# PowCapMobile.net
KiCad netlist of a schematic drawn in Altium Designer
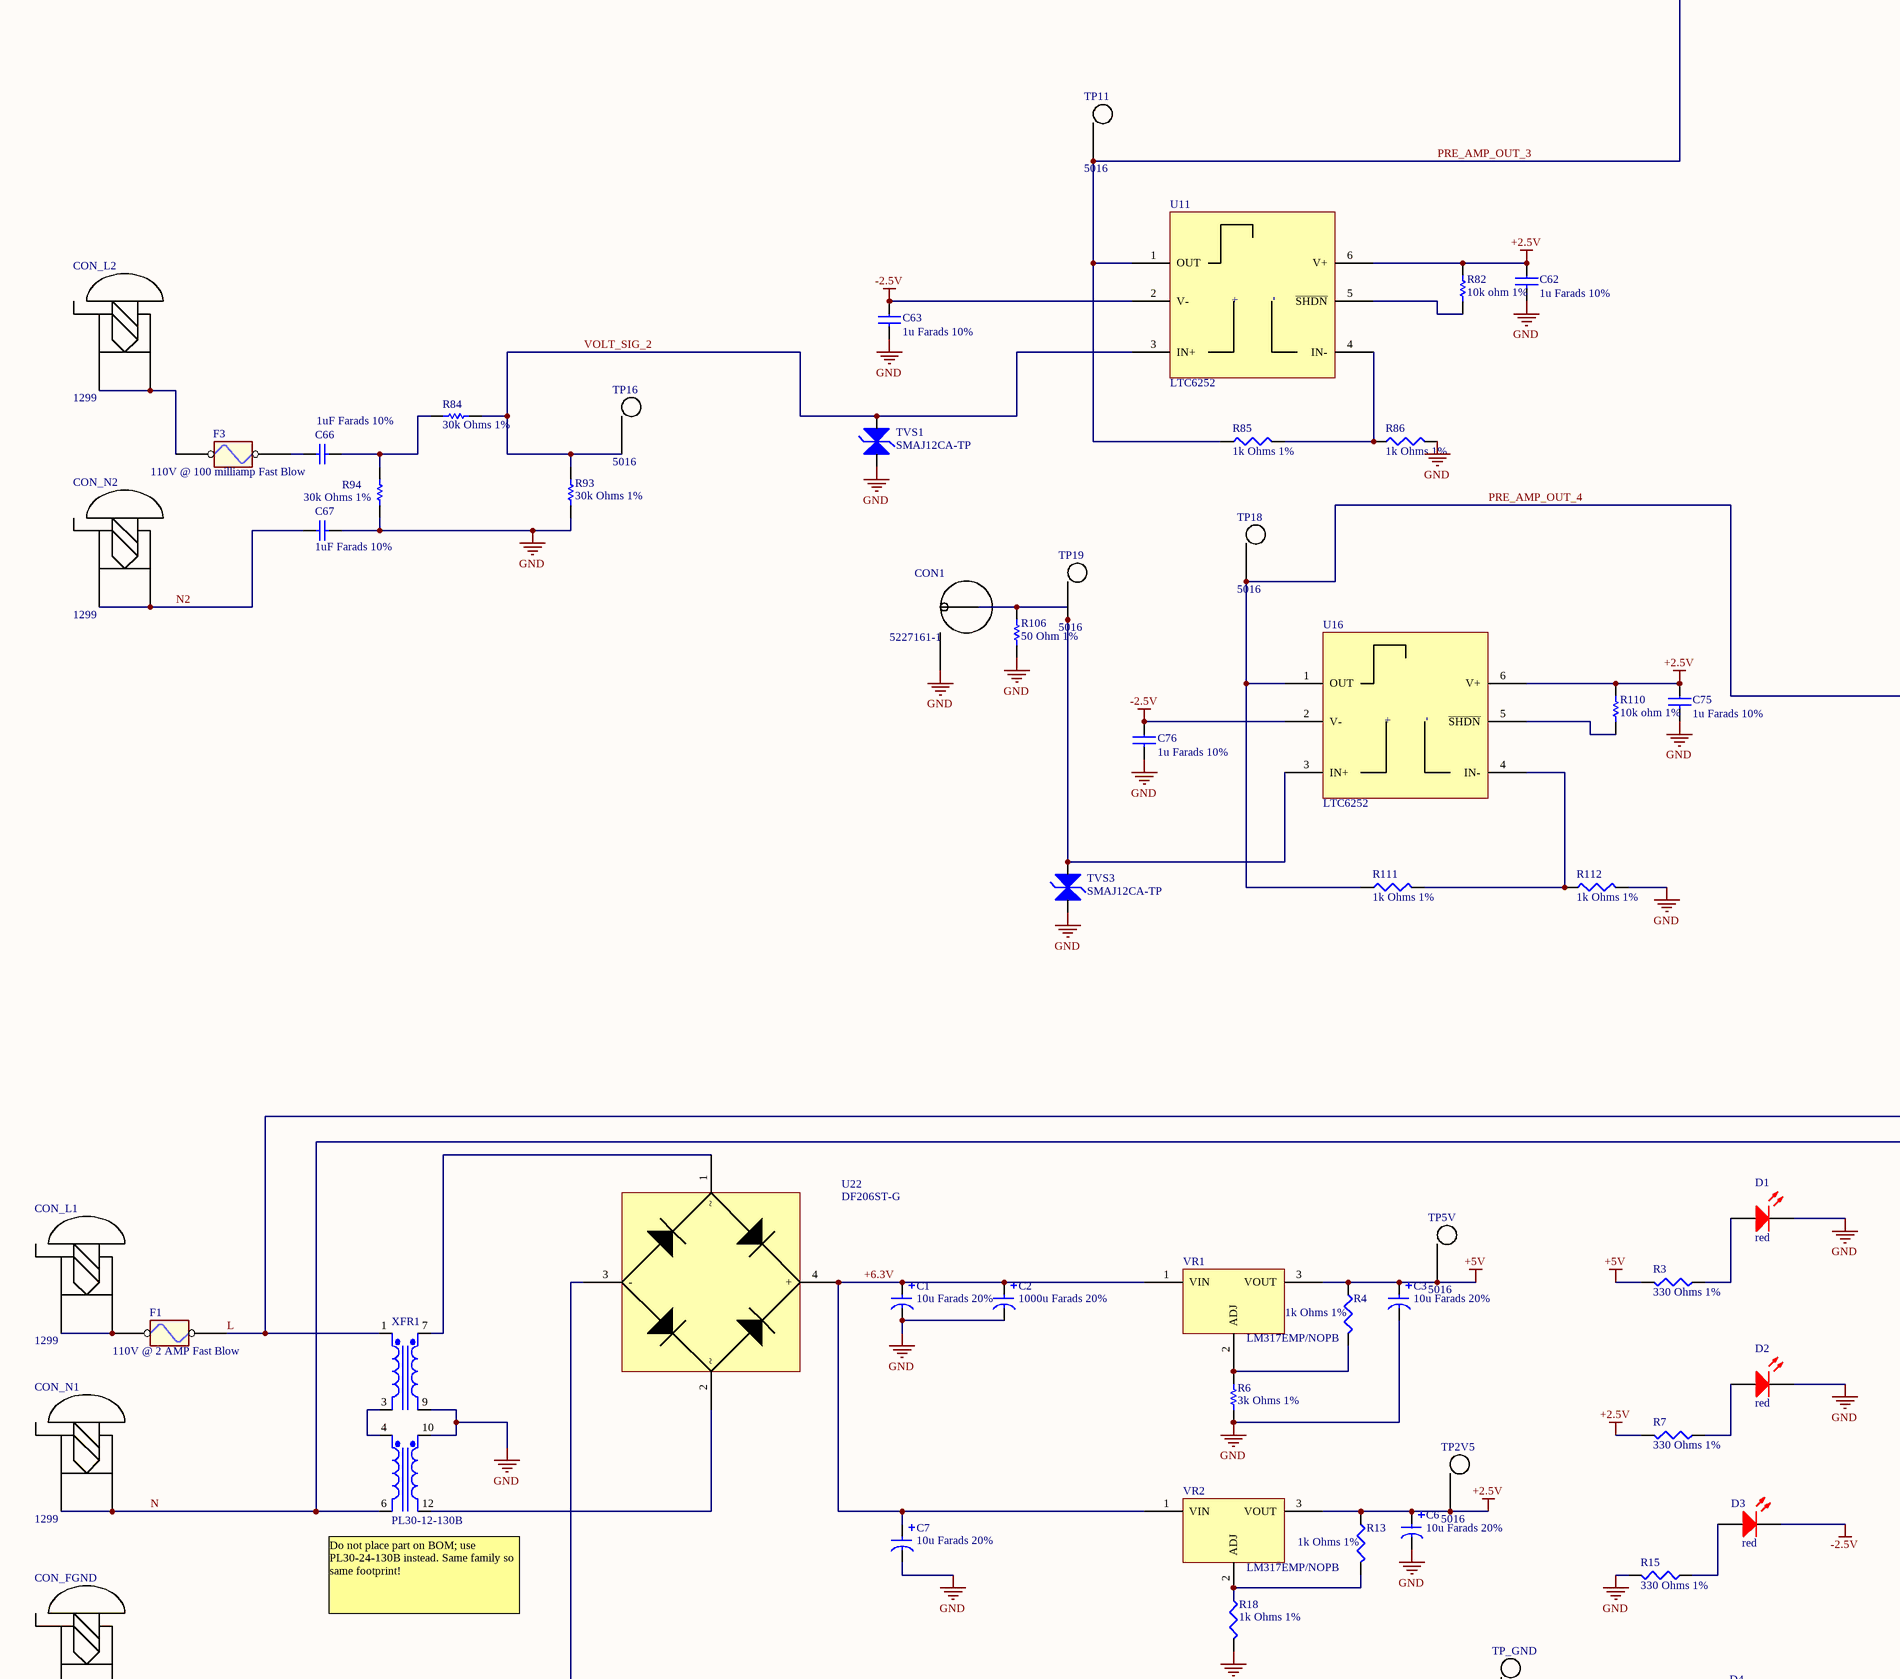
[diagram p0: PowCapMobile.SchDoc, top left]
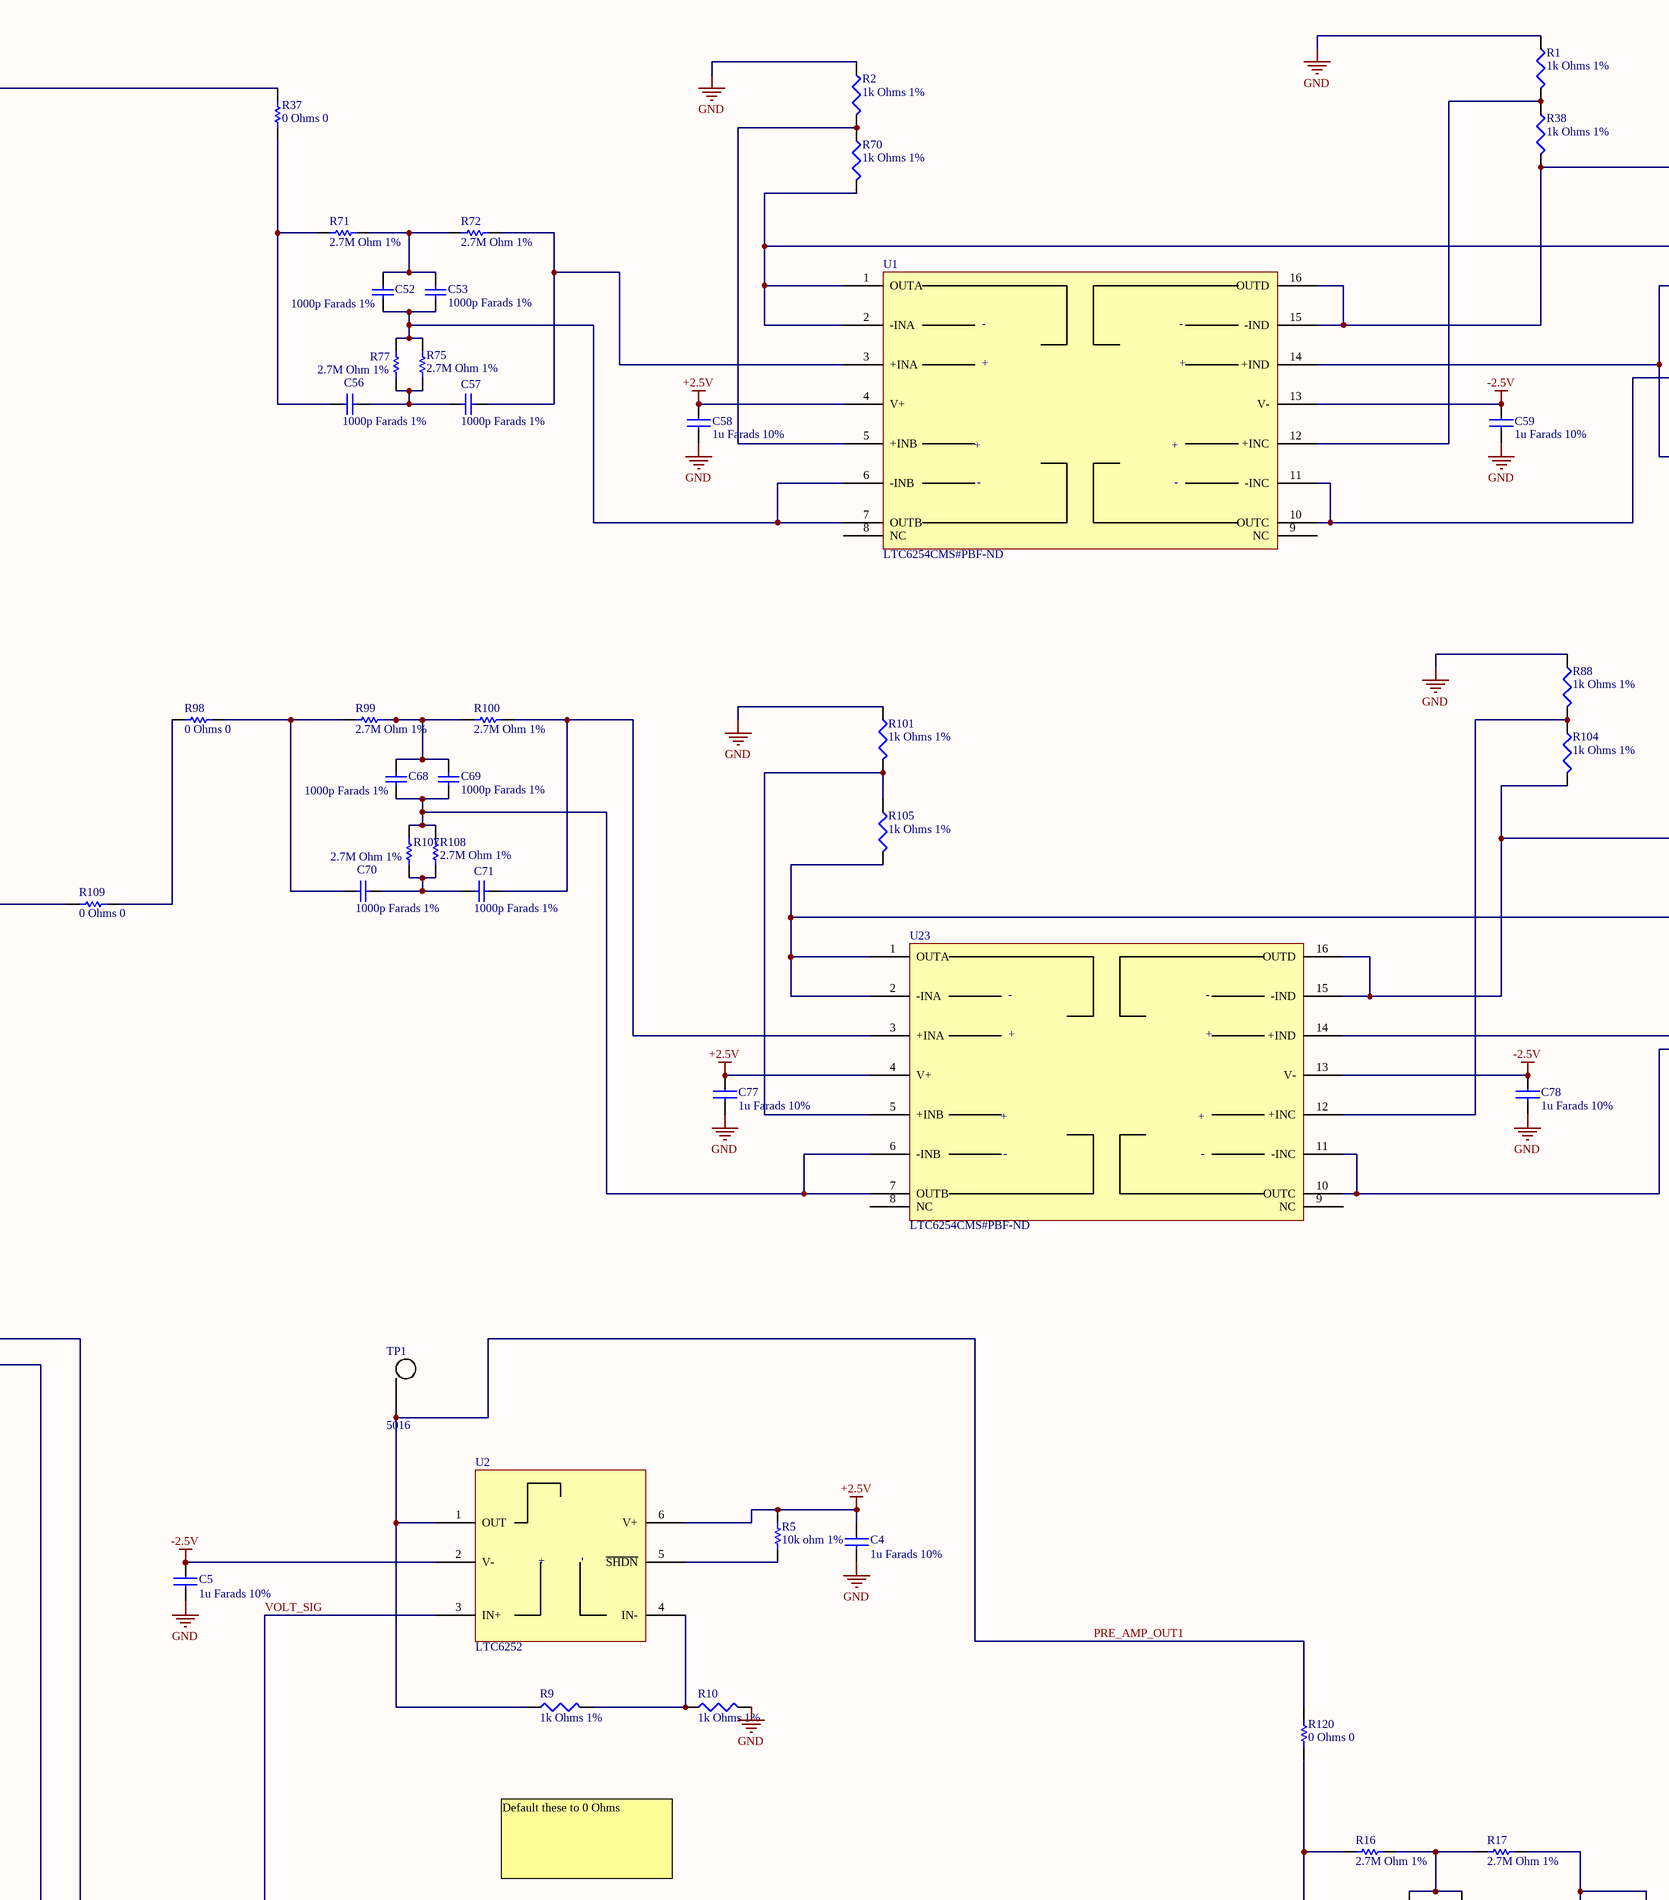
[diagram p1: PowCapMobile.SchDoc, top middle]
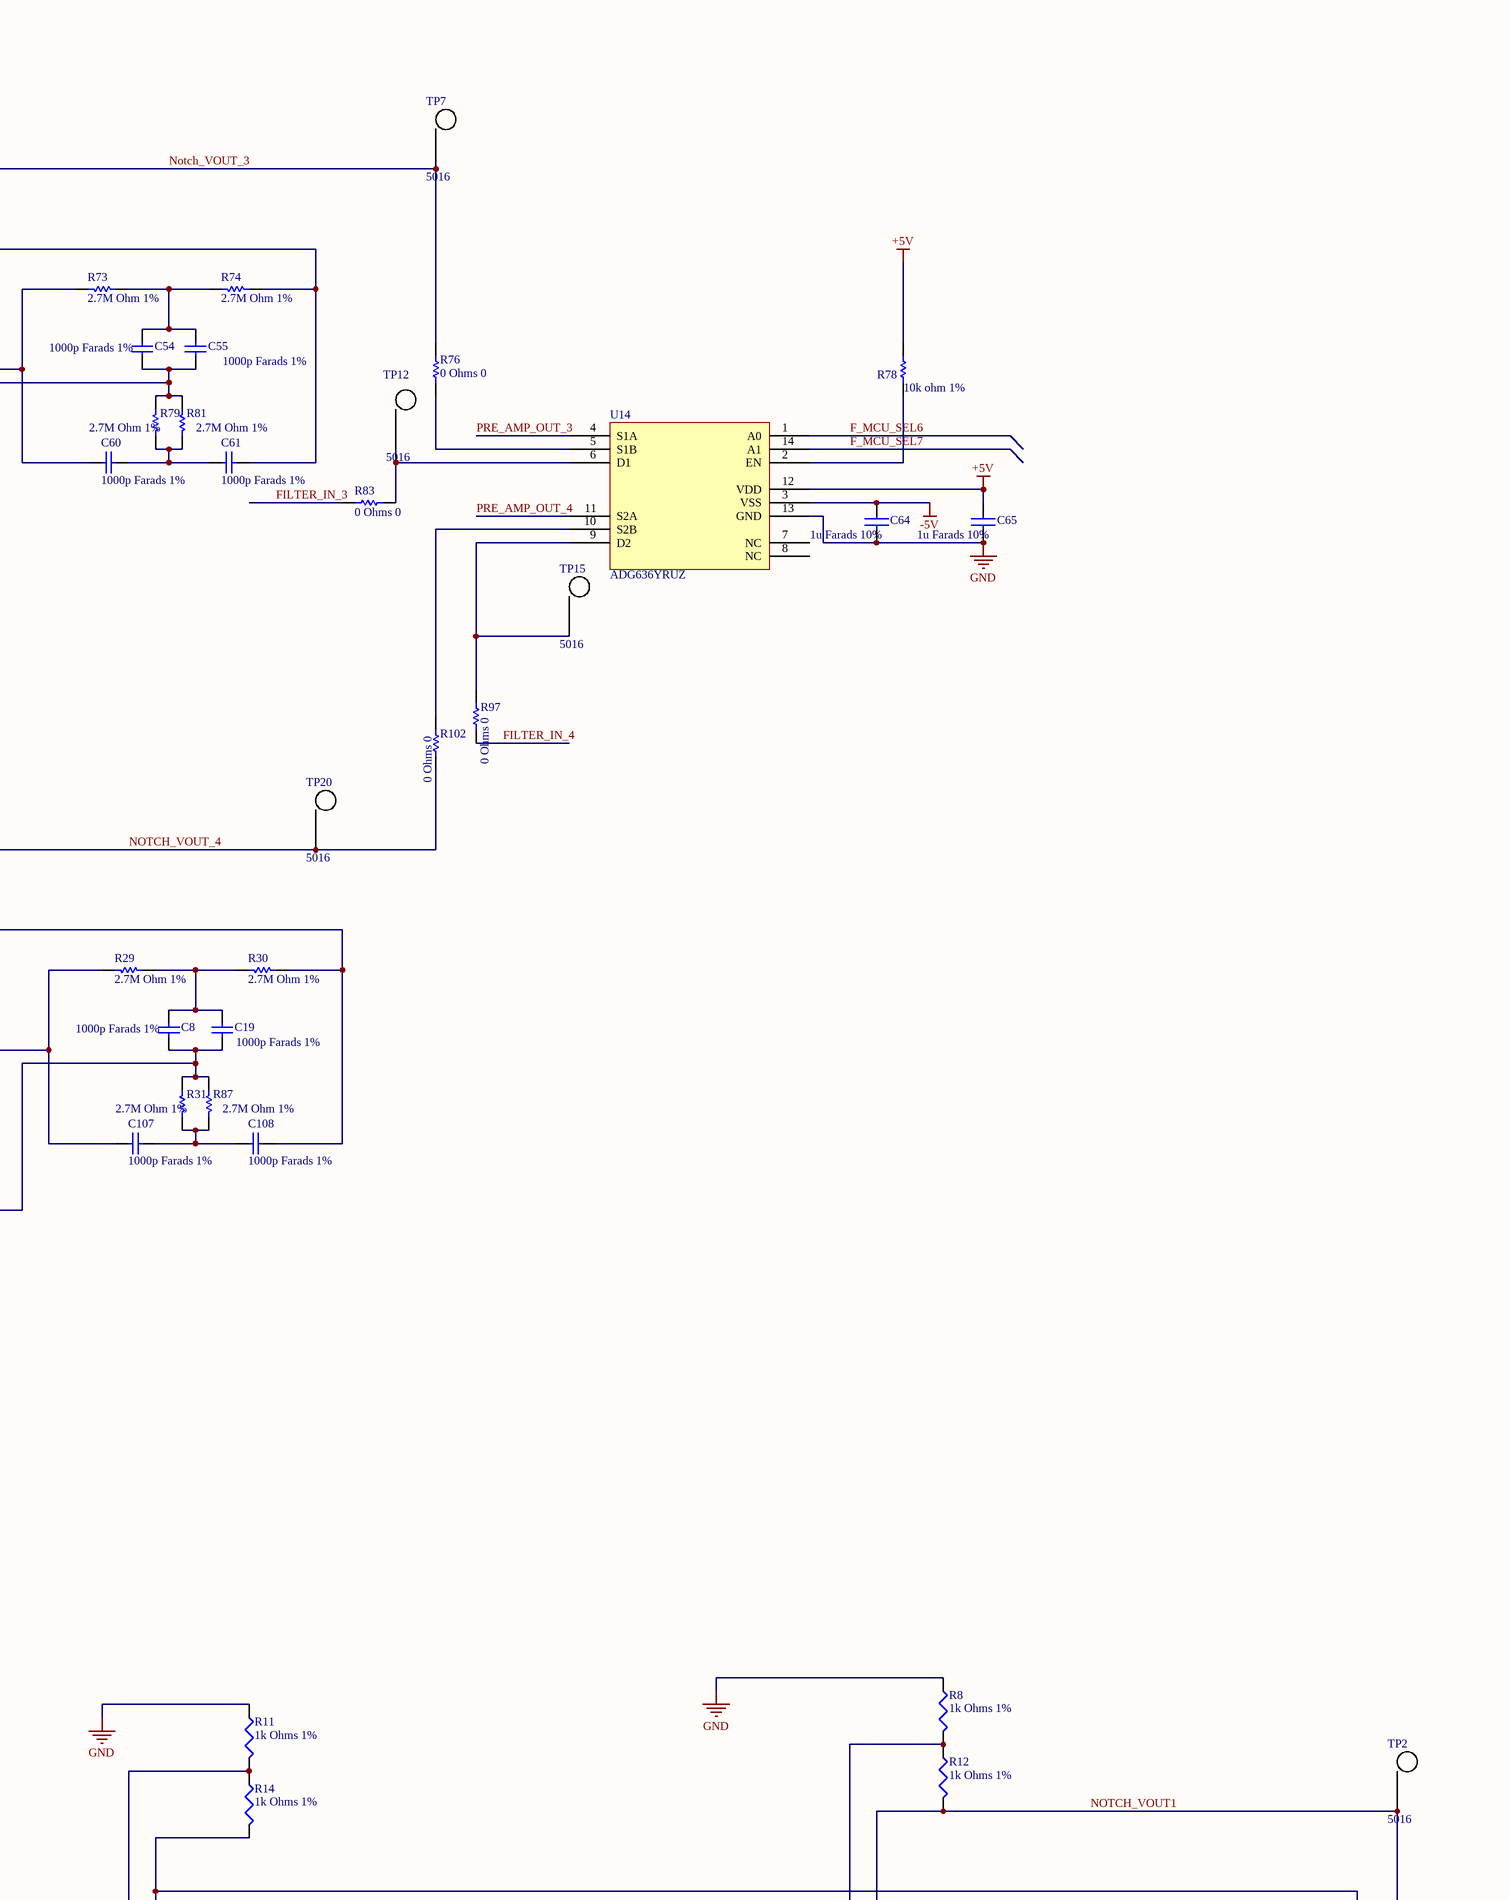
[diagram p2: PowCapMobile.SchDoc, top right]
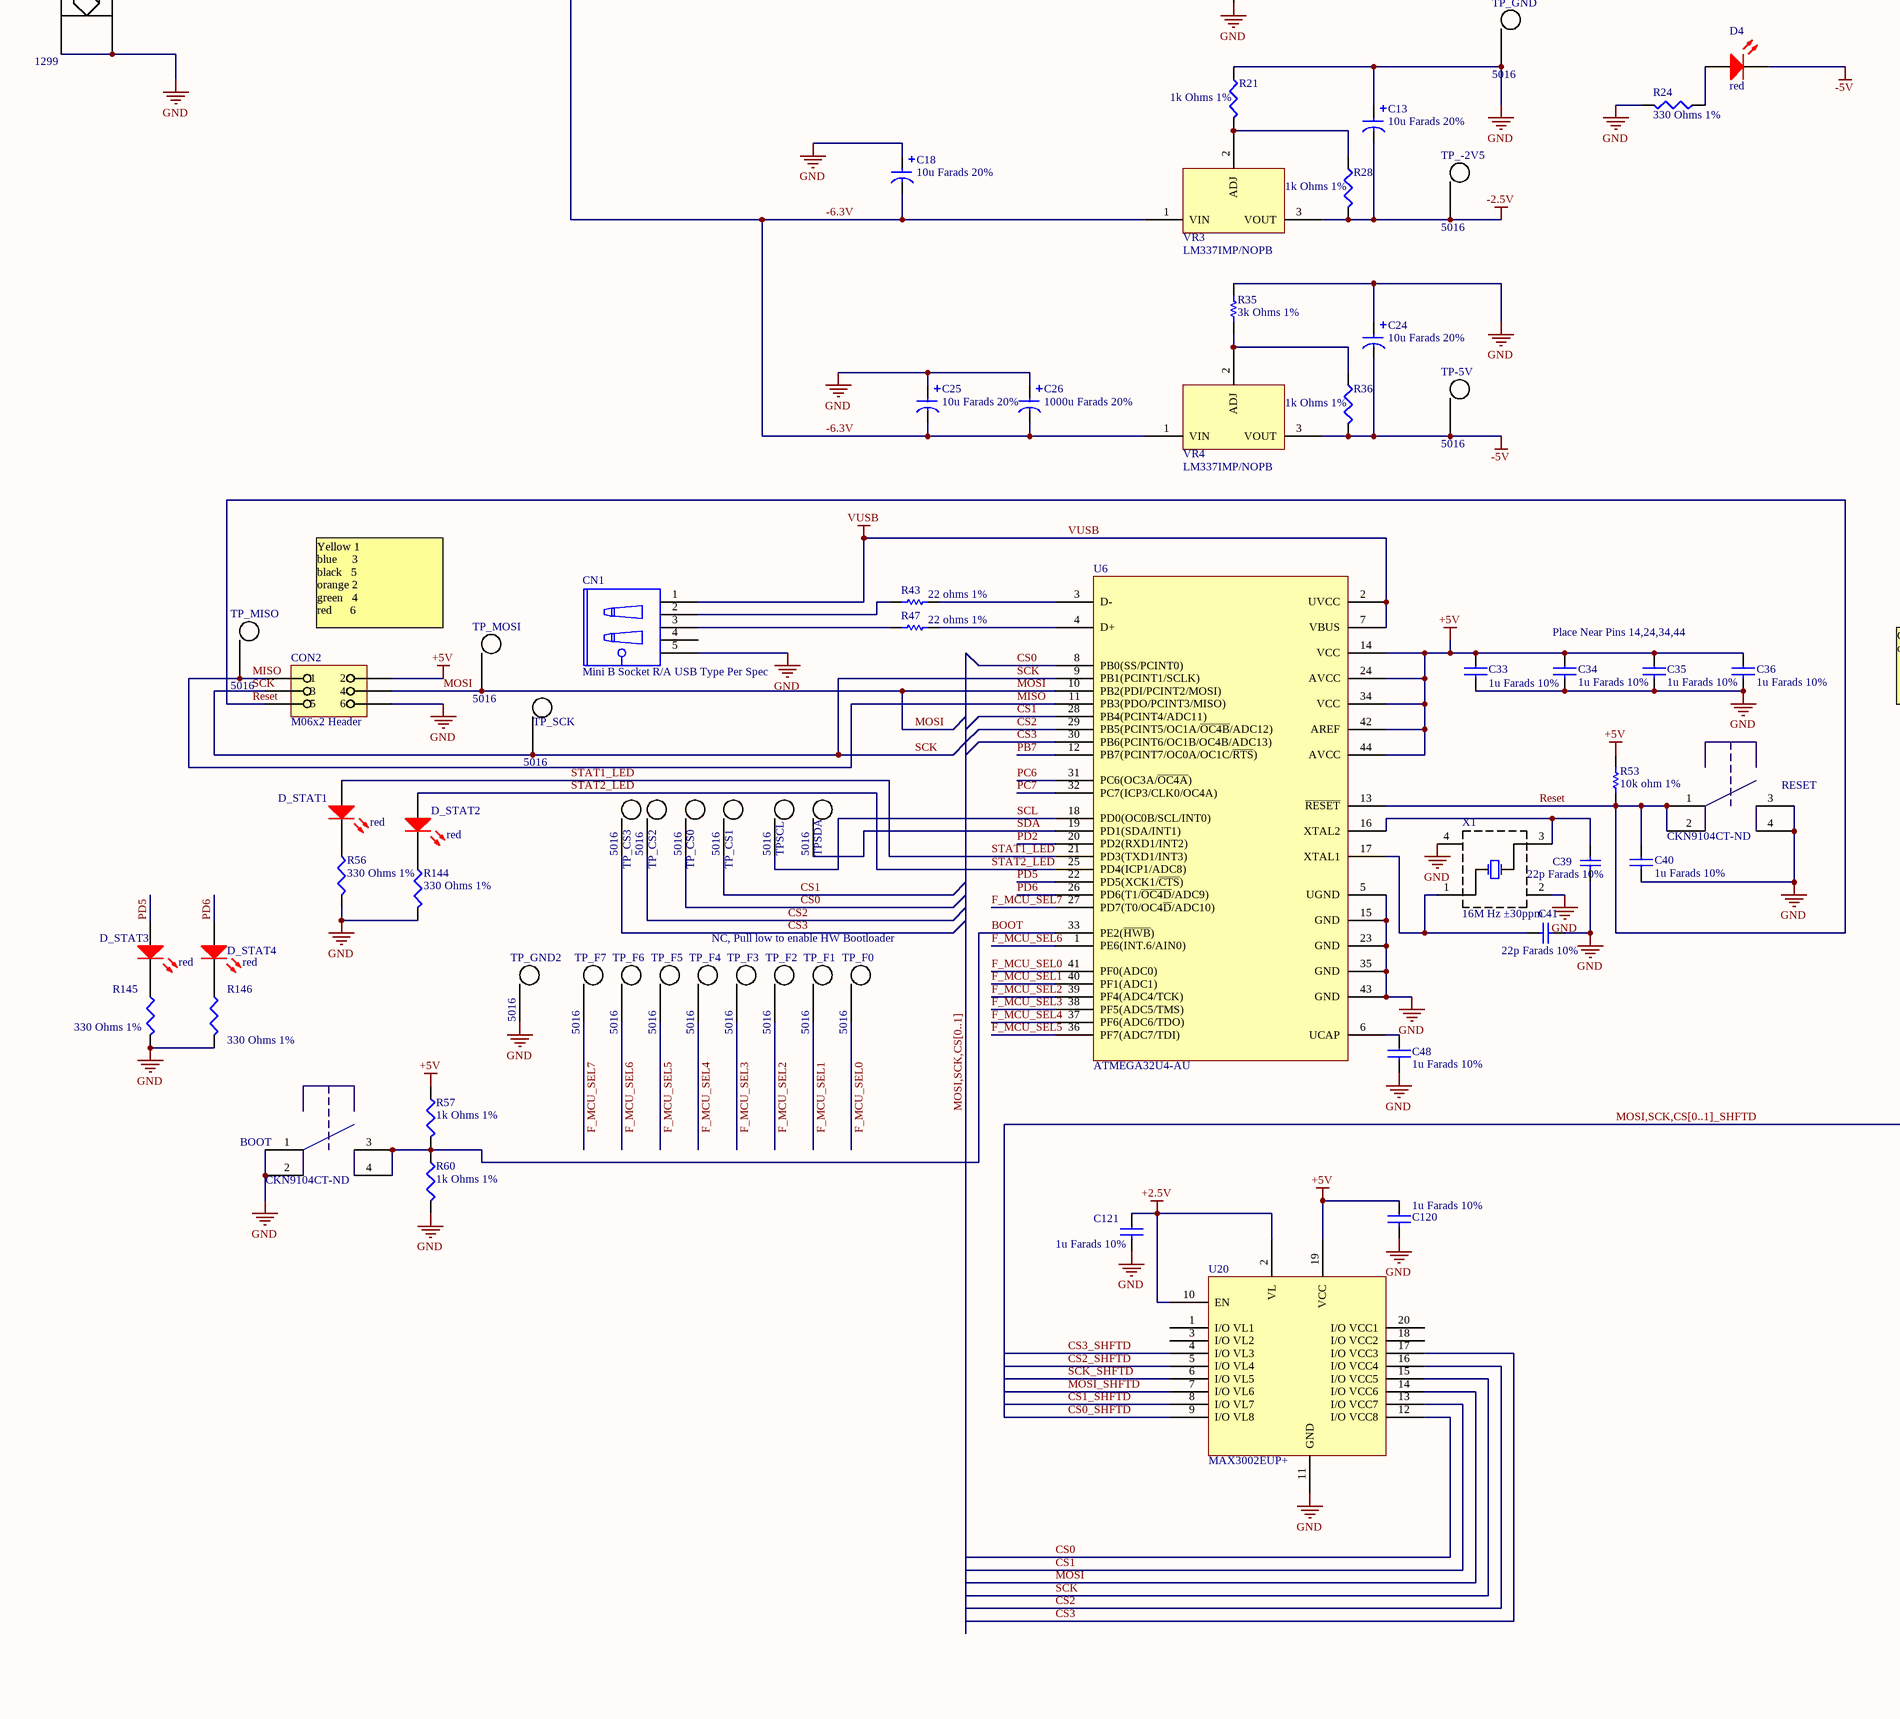
[diagram p3: PowCapMobile.SchDoc, centre left]
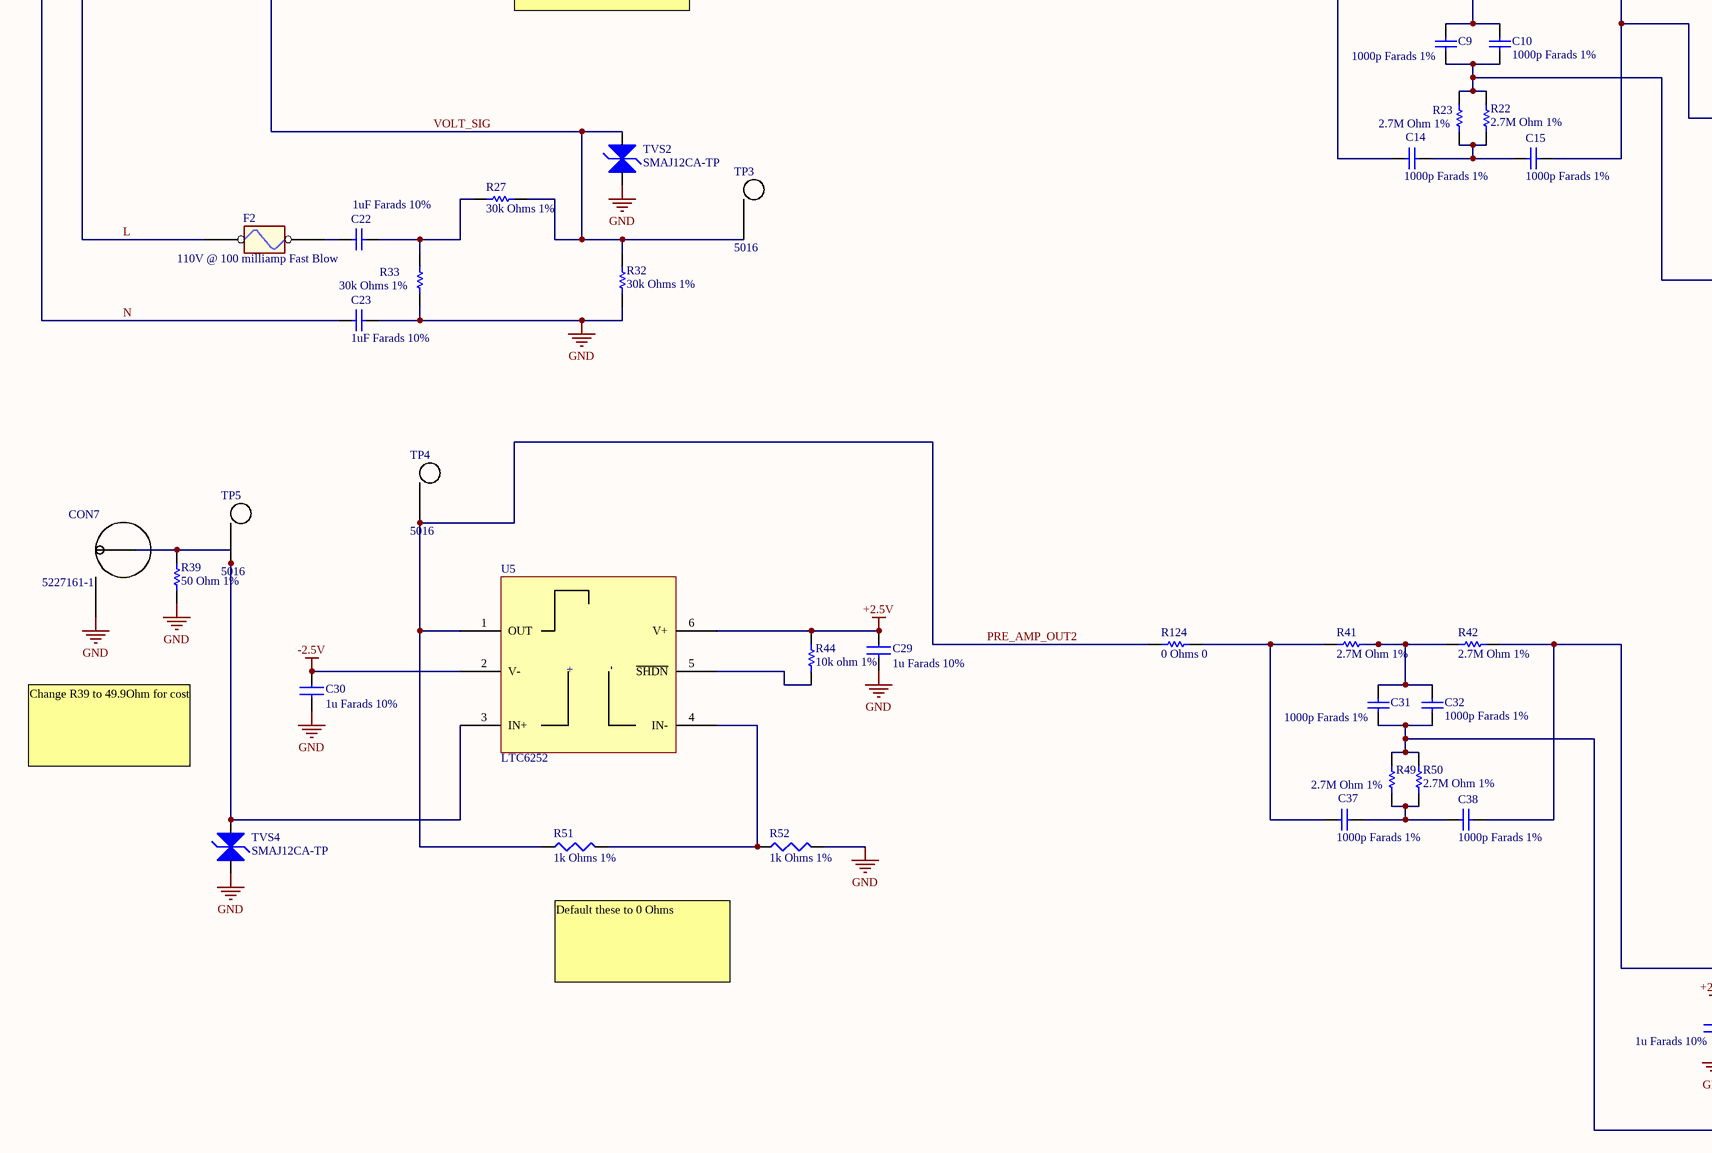
[diagram p4: PowCapMobile.SchDoc, centre middle]
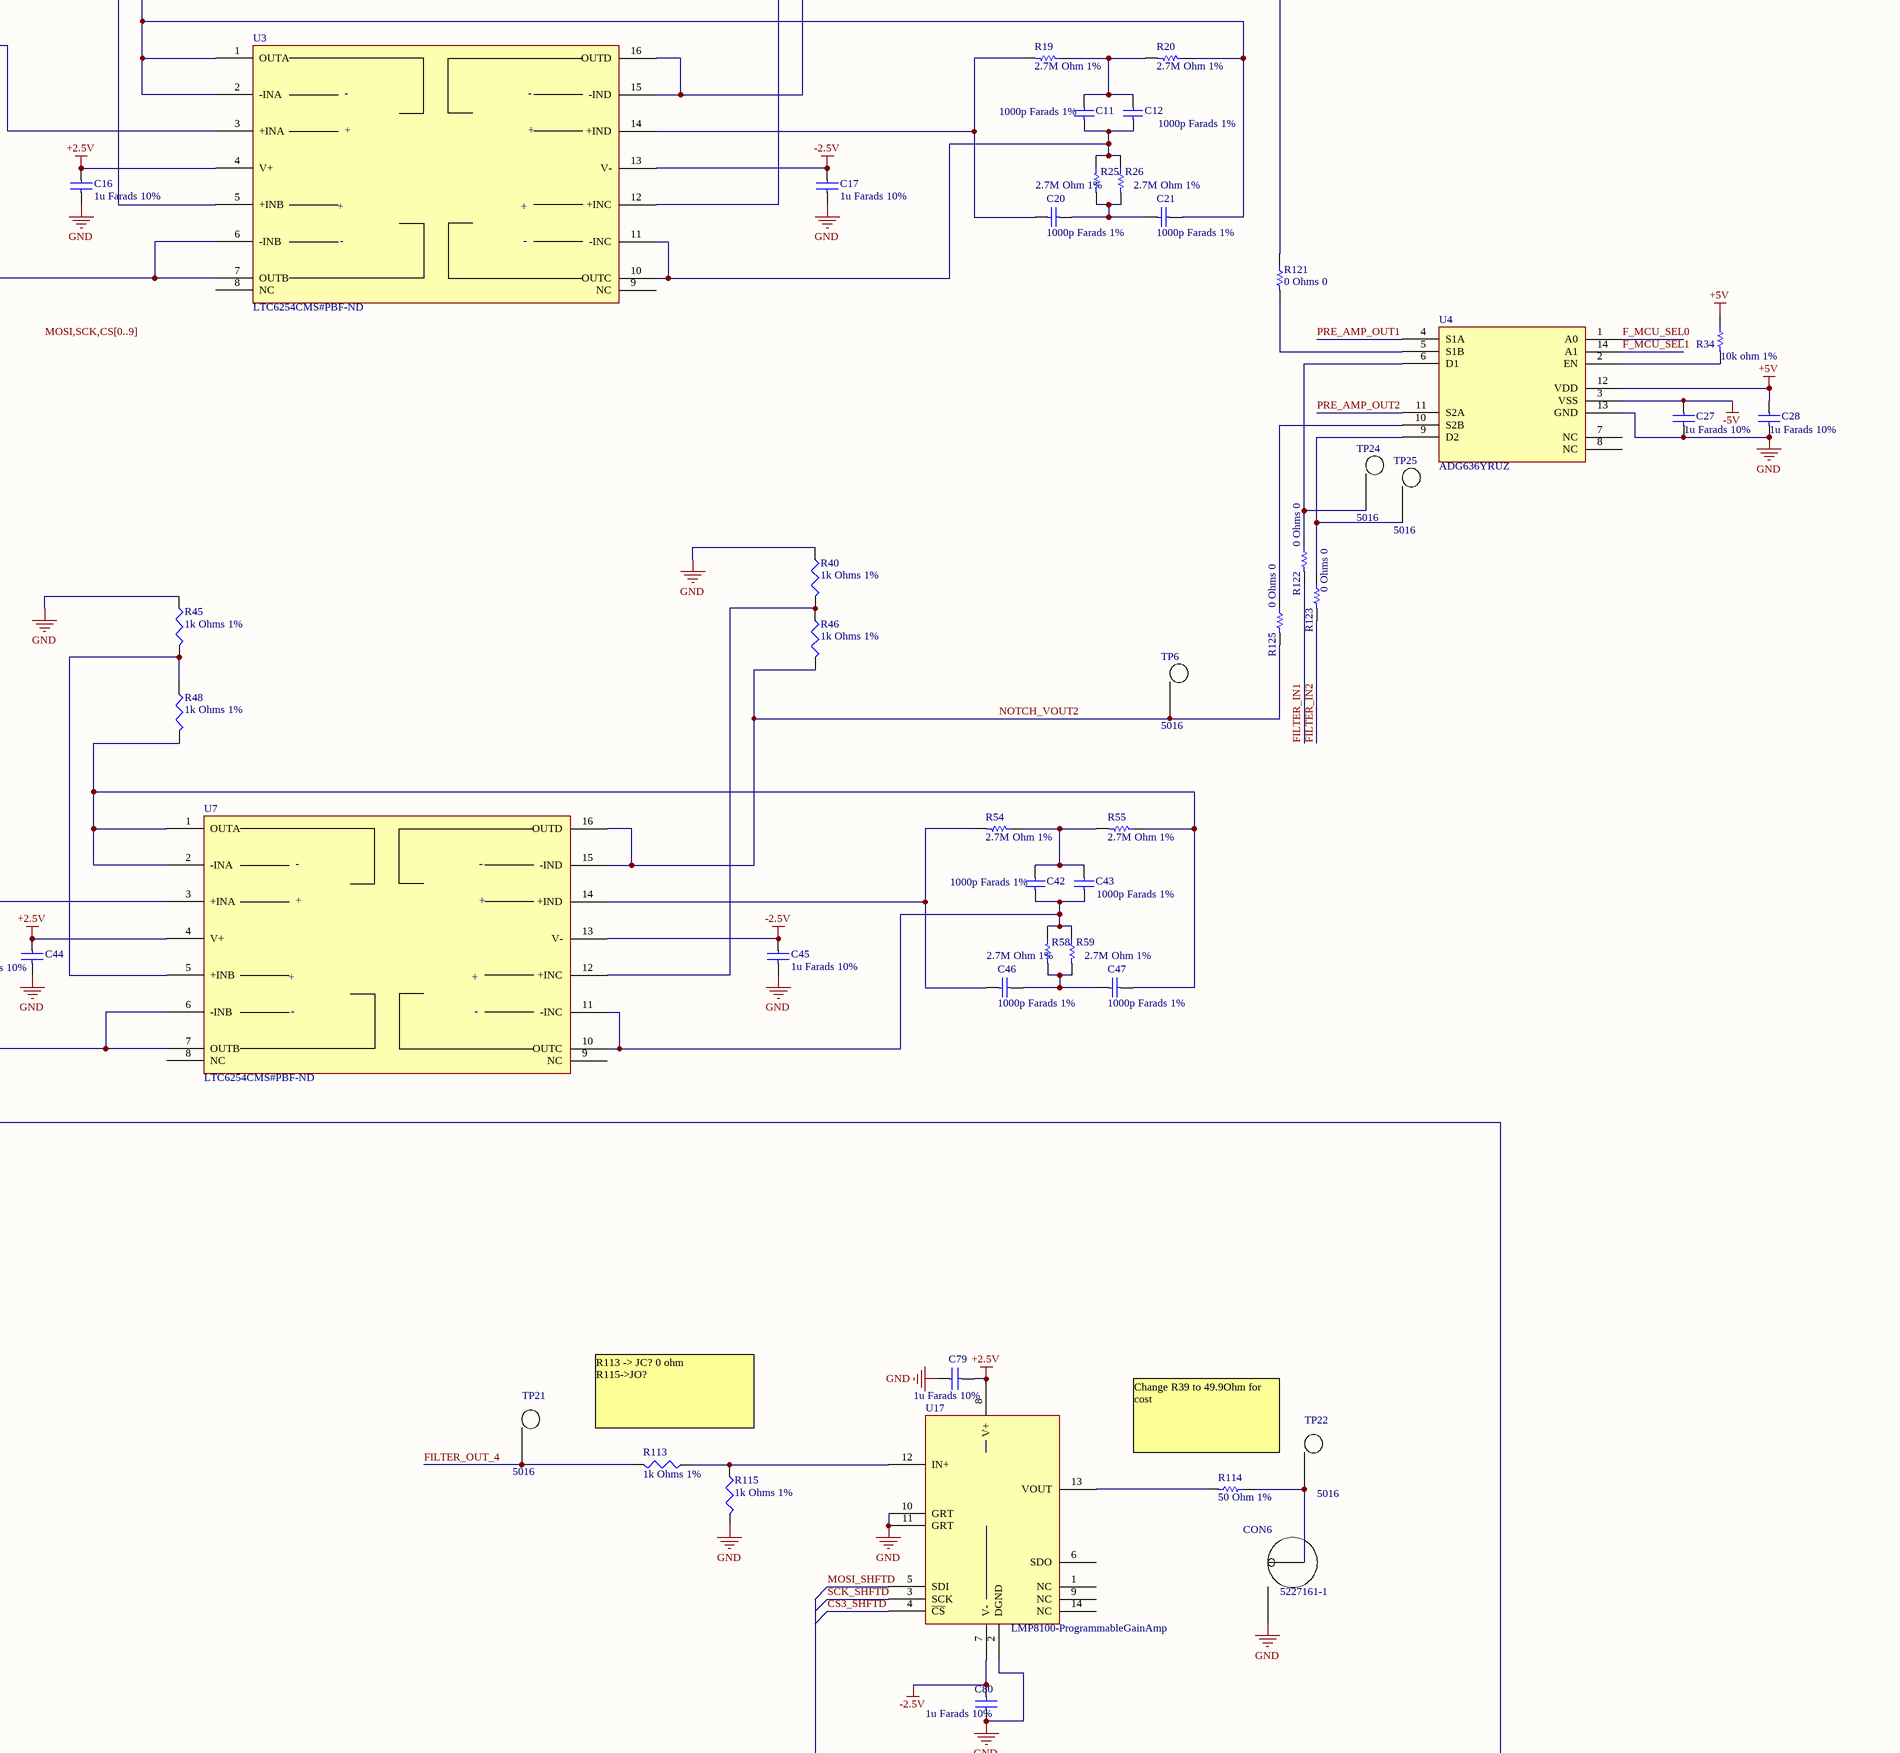
[diagram p5: PowCapMobile.SchDoc, centre right]
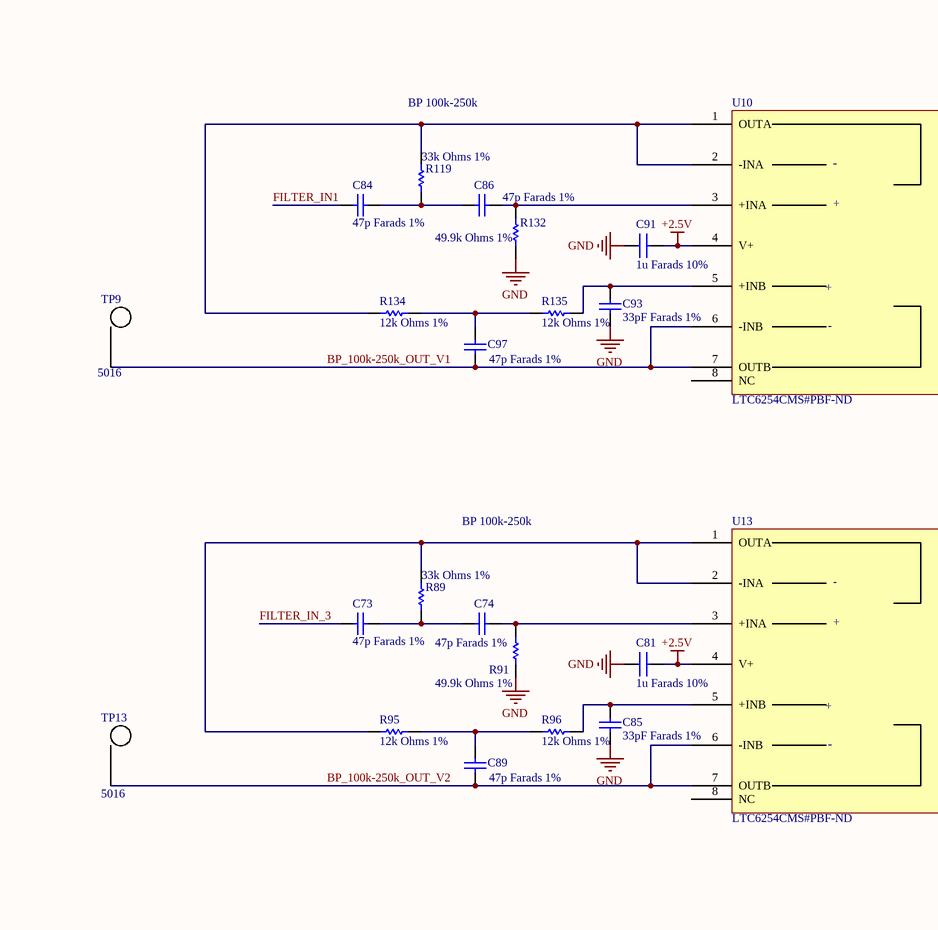
[diagram p6: PowCapMobile.SchDoc, bottom left]
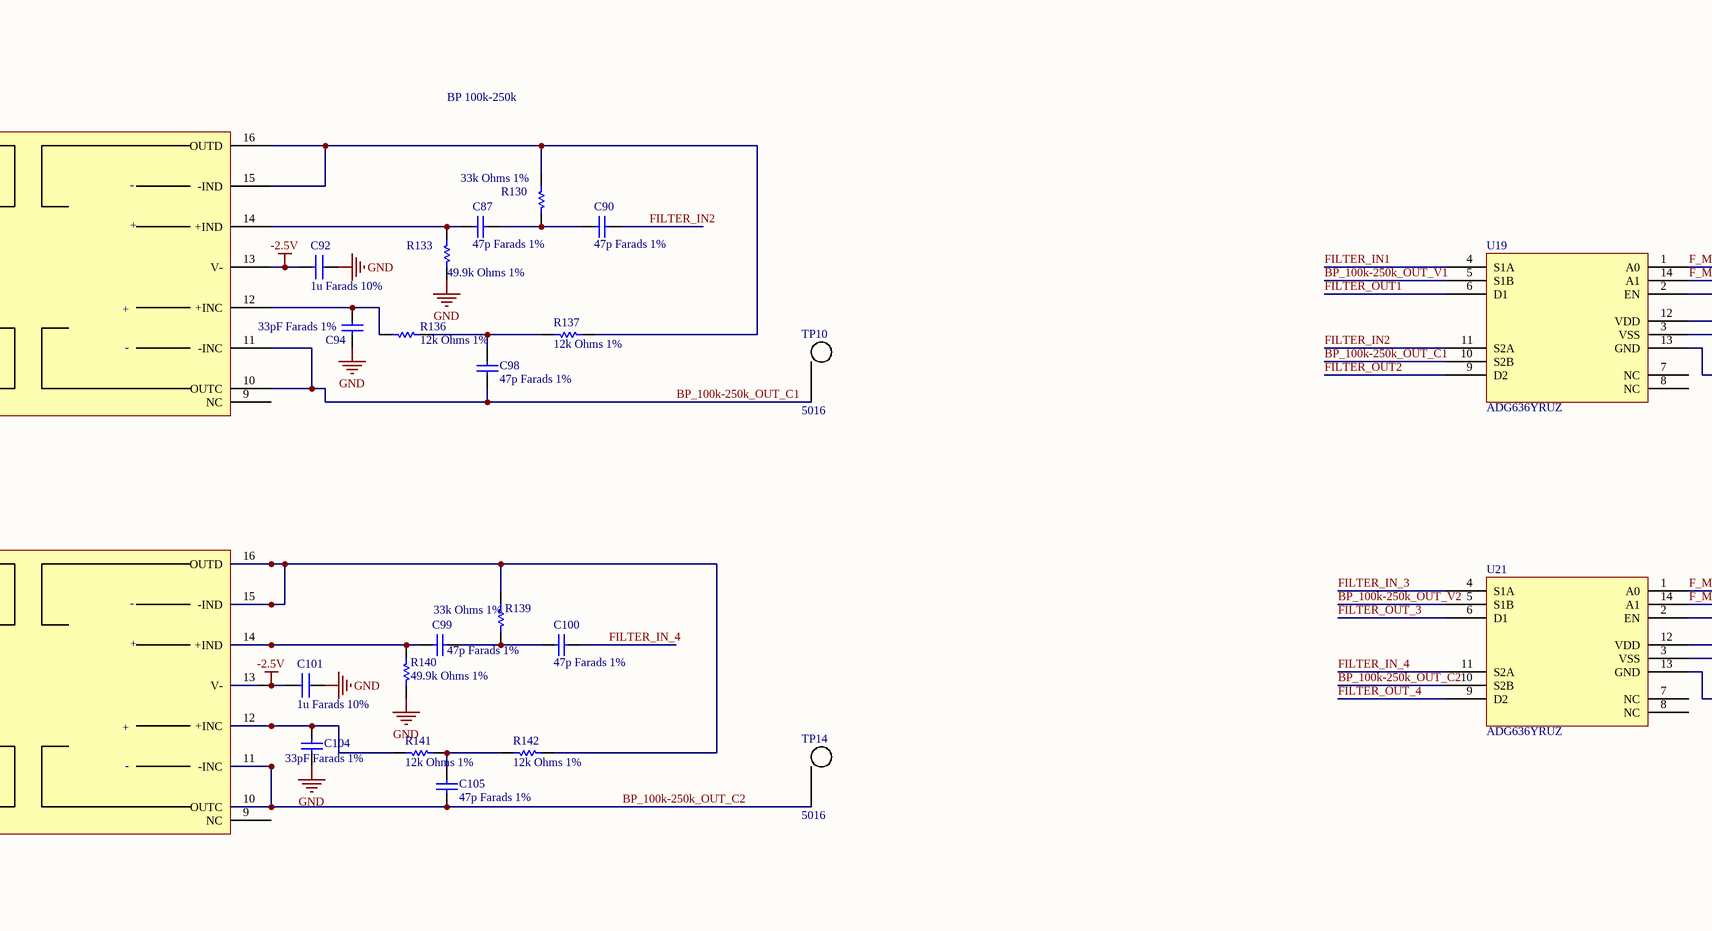
[diagram p7: PowCapMobile.SchDoc, bottom middle]
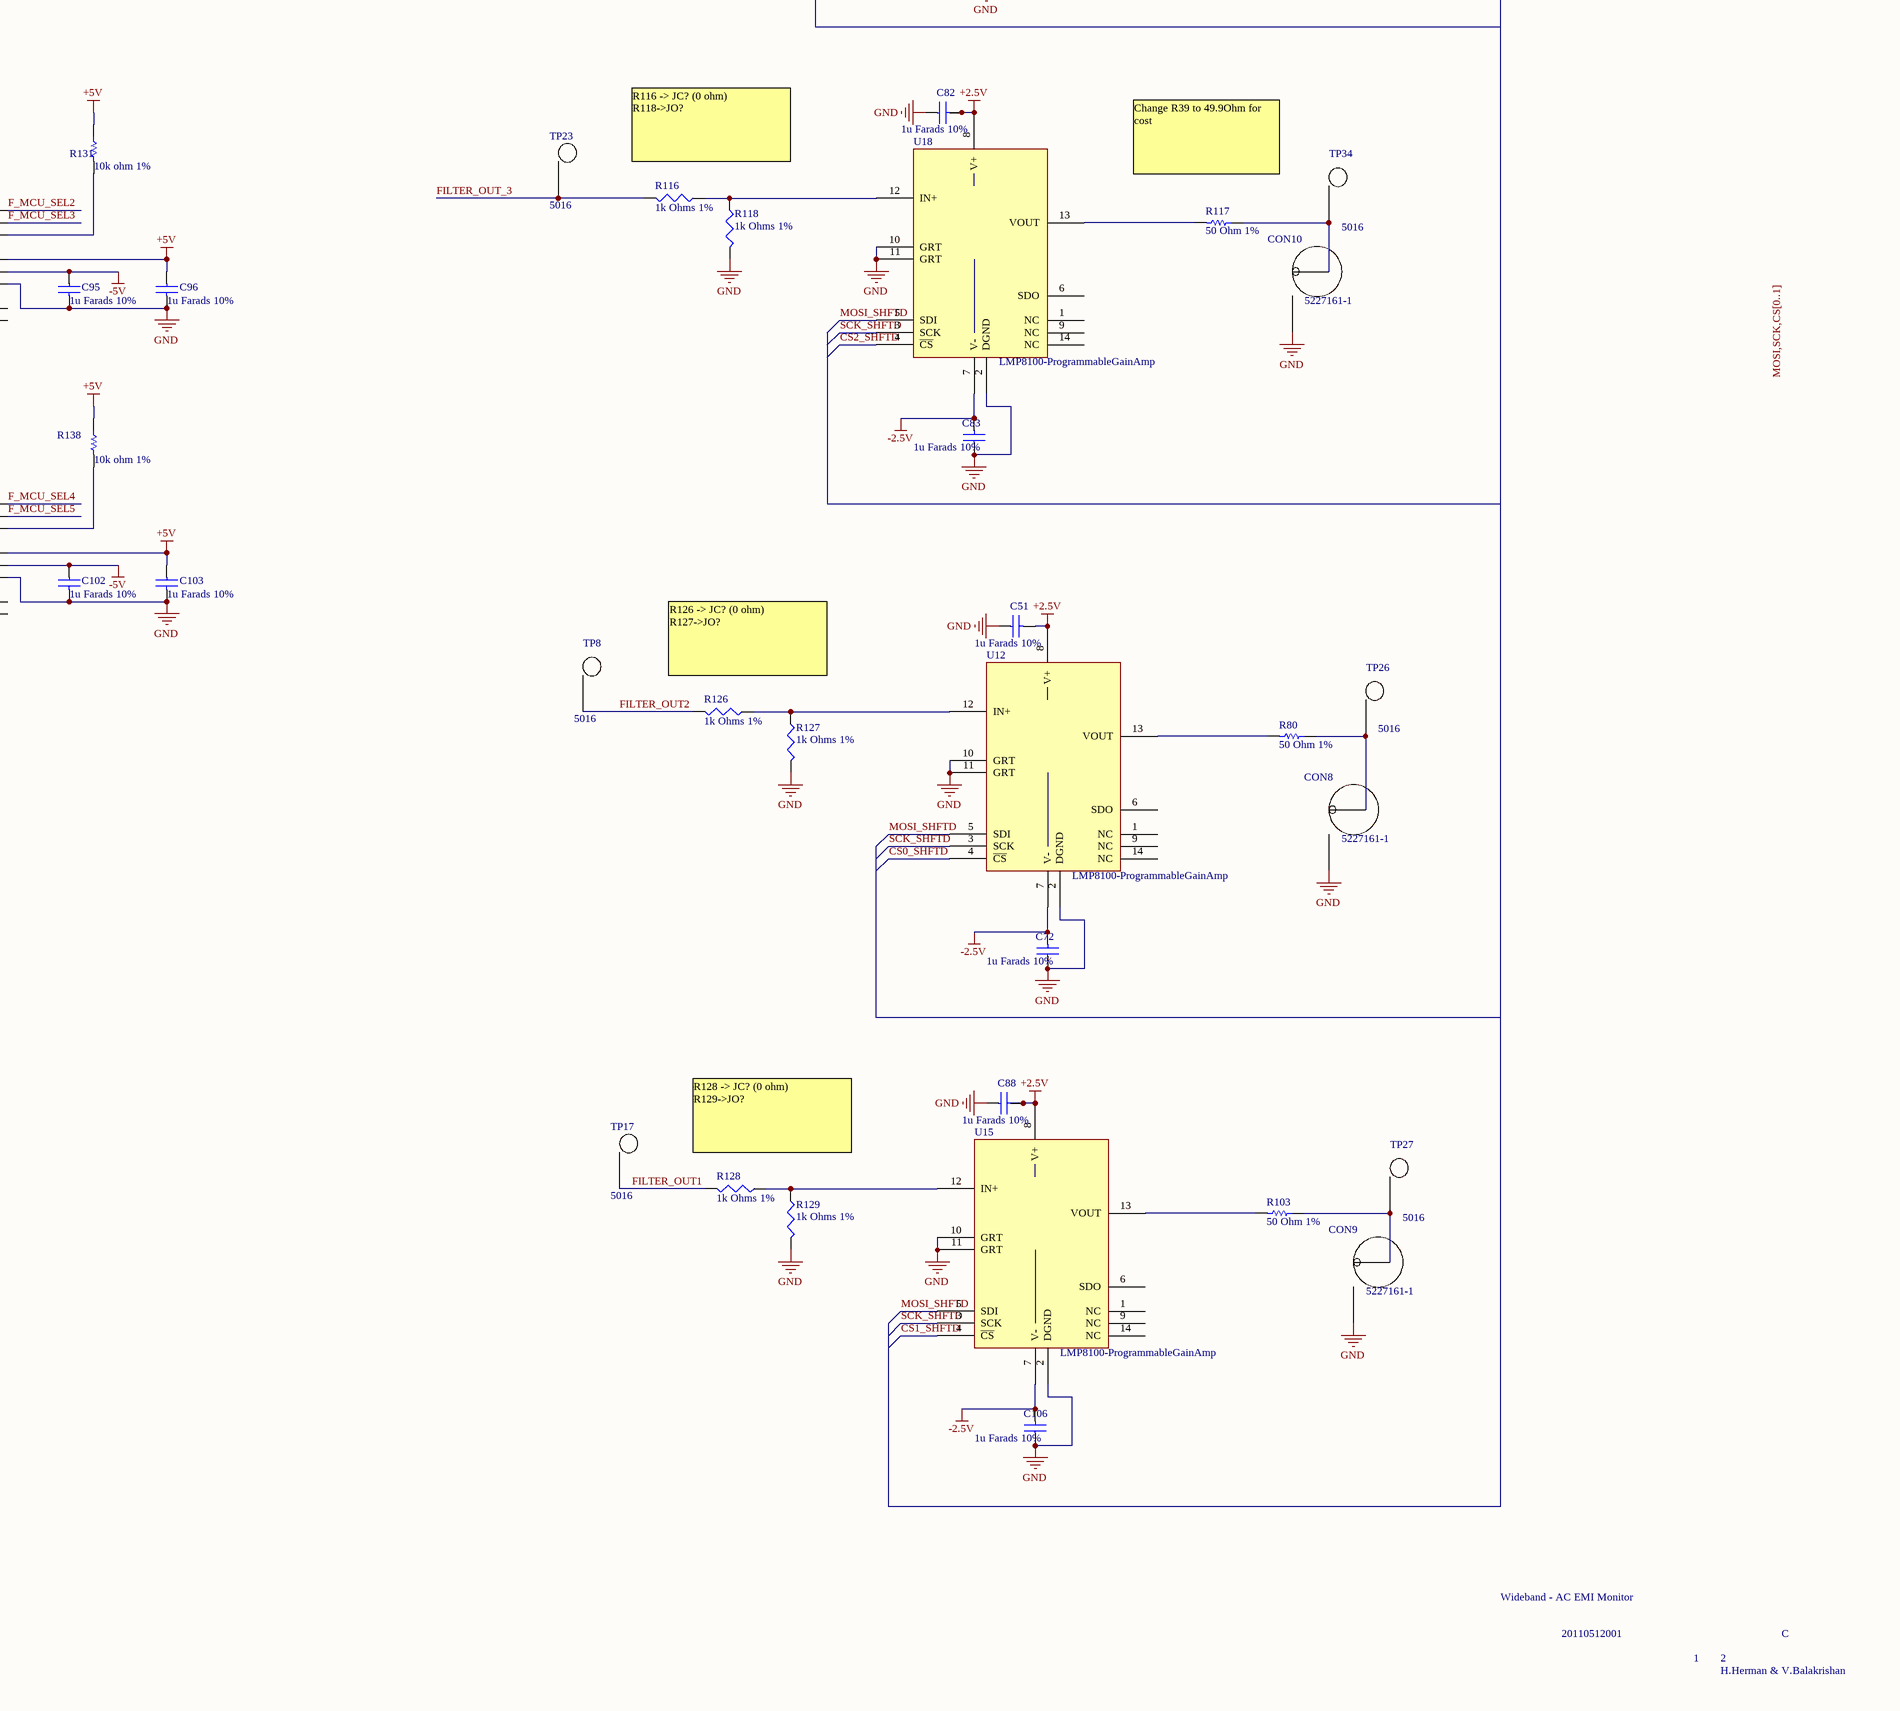
[diagram p8: PowCapMobile.SchDoc, bottom right]

(export (version "E")
  (design (tool "Eeschema 10.0.6"))
  (components
    (comp (ref "BOOT")
      (value "CKN9104CT-ND")
      (footprint "MOM-SW")
      (description "SW - SPST-NO - SM")
      (libsource (lib "FriedParts") (part "MOM-BUT"))
    )
    (comp (ref "C1")
      (value "10u Farads 20%")
      (footprint "CAP-SMD-POL-5mmDia")
      (description "capacitor, case c, 10uf, 25v; application:general purpose;")
      (fields (field (name "MFRPARTNUM") "EEE1EA100SR"))
      (libsource (lib "FriedParts") (part "CAP_POL"))
    )
    (comp (ref "C2")
      (value "1000u Farads 20%")
      (footprint "CAP-CAN-SMD-POL-12.5mmDia")
      (description "cap aluminum 1000uf 25vdc 20% 12.5 x 13.5mm smd 1100ma 5000")
      (fields (field (name "MFRPARTNUM") "EEV-FK1E102Q"))
      (libsource (lib "FriedParts") (part "CAP_POL"))
    )
    (comp (ref "C3")
      (value "10u Farads 20%")
      (footprint "CAP-SMD-POL-5mmDia")
      (description "capacitor, case c, 10uf, 25v; application:general purpose;")
      (fields (field (name "MFRPARTNUM") "EEE1EA100SR"))
      (libsource (lib "FriedParts") (part "CAP_POL"))
    )
    (comp (ref "C4")
      (value "1u Farads 10%")
      (footprint "SM/C_0603")
      (description "CAP CER 1.0UF 10V 10% X5R 0603")
      (fields (field (name "MFRPARTNUM") "GRM188R61A105KA61D"))
      (libsource (lib "FriedParts") (part "CAP NP"))
    )
    (comp (ref "C5")
      (value "1u Farads 10%")
      (footprint "SM/C_0603")
      (description "CAP CER 1.0UF 10V 10% X5R 0603")
      (fields (field (name "MFRPARTNUM") "GRM188R61A105KA61D"))
      (libsource (lib "FriedParts") (part "CAP NP"))
    )
    (comp (ref "C6")
      (value "10u Farads 20%")
      (footprint "CAP-SMD-POL-5mmDia")
      (description "capacitor, case c, 10uf, 25v; application:general purpose;")
      (fields (field (name "MFRPARTNUM") "EEE1EA100SR"))
      (libsource (lib "FriedParts") (part "CAP_POL"))
    )
    (comp (ref "C7")
      (value "10u Farads 20%")
      (footprint "CAP-SMD-POL-5mmDia")
      (description "capacitor, case c, 10uf, 25v; application:general purpose;")
      (fields (field (name "MFRPARTNUM") "EEE1EA100SR"))
      (libsource (lib "FriedParts") (part "CAP_POL"))
    )
    (comp (ref "C8")
      (value "1000p Farads 1%")
      (footprint "SM/C_0603")
      (description "capacitor ceramic 1000pf, 50v, c0g, 0603; dielectric")
      (fields (field (name "MFRPARTNUM") "06035A102FAT2A"))
      (libsource (lib "FriedParts") (part "CAP"))
    )
    (comp (ref "C9")
      (value "1000p Farads 1%")
      (footprint "SM/C_0603")
      (description "capacitor ceramic 1000pf, 50v, c0g, 0603; dielectric")
      (fields (field (name "MFRPARTNUM") "06035A102FAT2A"))
      (libsource (lib "FriedParts") (part "CAP"))
    )
    (comp (ref "C10")
      (value "1000p Farads 1%")
      (footprint "SM/C_0603")
      (description "capacitor ceramic 1000pf, 50v, c0g, 0603; dielectric")
      (fields (field (name "MFRPARTNUM") "06035A102FAT2A"))
      (libsource (lib "FriedParts") (part "CAP"))
    )
    (comp (ref "C11")
      (value "1000p Farads 1%")
      (footprint "SM/C_0603")
      (description "capacitor ceramic 1000pf, 50v, c0g, 0603; dielectric")
      (fields (field (name "MFRPARTNUM") "06035A102FAT2A"))
      (libsource (lib "FriedParts") (part "CAP"))
    )
    (comp (ref "C12")
      (value "1000p Farads 1%")
      (footprint "SM/C_0603")
      (description "capacitor ceramic 1000pf, 50v, c0g, 0603; dielectric")
      (fields (field (name "MFRPARTNUM") "06035A102FAT2A"))
      (libsource (lib "FriedParts") (part "CAP"))
    )
    (comp (ref "C13")
      (value "10u Farads 20%")
      (footprint "CAP-SMD-POL-5mmDia")
      (description "capacitor, case c, 10uf, 25v; application:general purpose;")
      (fields (field (name "MFRPARTNUM") "EEE1EA100SR"))
      (libsource (lib "FriedParts") (part "CAP_POL"))
    )
    (comp (ref "C14")
      (value "1000p Farads 1%")
      (footprint "SM/C_0603")
      (description "capacitor ceramic 1000pf, 50v, c0g, 0603; dielectric")
      (fields (field (name "MFRPARTNUM") "06035A102FAT2A"))
      (libsource (lib "FriedParts") (part "CAP"))
    )
    (comp (ref "C15")
      (value "1000p Farads 1%")
      (footprint "SM/C_0603")
      (description "capacitor ceramic 1000pf, 50v, c0g, 0603; dielectric")
      (fields (field (name "MFRPARTNUM") "06035A102FAT2A"))
      (libsource (lib "FriedParts") (part "CAP"))
    )
    (comp (ref "C16")
      (value "1u Farads 10%")
      (footprint "SM/C_0603")
      (description "CAP CER 1.0UF 10V 10% X5R 0603")
      (fields (field (name "MFRPARTNUM") "GRM188R61A105KA61D"))
      (libsource (lib "FriedParts") (part "CAP NP"))
    )
    (comp (ref "C17")
      (value "1u Farads 10%")
      (footprint "SM/C_0603")
      (description "CAP CER 1.0UF 10V 10% X5R 0603")
      (fields (field (name "MFRPARTNUM") "GRM188R61A105KA61D"))
      (libsource (lib "FriedParts") (part "CAP NP"))
    )
    (comp (ref "C18")
      (value "10u Farads 20%")
      (footprint "CAP-SMD-POL-5mmDia")
      (description "capacitor, case c, 10uf, 25v; application:general purpose;")
      (fields (field (name "MFRPARTNUM") "EEE1EA100SR"))
      (libsource (lib "FriedParts") (part "CAP_POL"))
    )
    (comp (ref "C19")
      (value "1000p Farads 1%")
      (footprint "SM/C_0603")
      (description "capacitor ceramic 1000pf, 50v, c0g, 0603; dielectric")
      (fields (field (name "MFRPARTNUM") "06035A102FAT2A"))
      (libsource (lib "FriedParts") (part "CAP"))
    )
    (comp (ref "C20")
      (value "1000p Farads 1%")
      (footprint "SM/C_0603")
      (description "capacitor ceramic 1000pf, 50v, c0g, 0603; dielectric")
      (fields (field (name "MFRPARTNUM") "06035A102FAT2A"))
      (libsource (lib "FriedParts") (part "CAP"))
    )
    (comp (ref "C21")
      (value "1000p Farads 1%")
      (footprint "SM/C_0603")
      (description "capacitor ceramic 1000pf, 50v, c0g, 0603; dielectric")
      (fields (field (name "MFRPARTNUM") "06035A102FAT2A"))
      (libsource (lib "FriedParts") (part "CAP"))
    )
    (comp (ref "C22")
      (value "1uF Farads 10%")
      (footprint "Y2-Caps-Epocs-1uF-10%")
      (description "Y2 Caps 1uF Epocs")
      (fields (field (name "MFRPARTNUM") "B32026B3105K"))
      (libsource (lib "FriedParts") (part "CAP"))
    )
    (comp (ref "C23")
      (value "1uF Farads 10%")
      (footprint "Y2-Caps-Epocs-1uF-10%")
      (description "Y2 Caps 1uF Epocs")
      (fields (field (name "MFRPARTNUM") "B32026B3105K"))
      (libsource (lib "FriedParts") (part "CAP"))
    )
    (comp (ref "C24")
      (value "10u Farads 20%")
      (footprint "CAP-SMD-POL-5mmDia")
      (description "capacitor, case c, 10uf, 25v; application:general purpose;")
      (fields (field (name "MFRPARTNUM") "EEE1EA100SR"))
      (libsource (lib "FriedParts") (part "CAP_POL"))
    )
    (comp (ref "C25")
      (value "10u Farads 20%")
      (footprint "CAP-SMD-POL-5mmDia")
      (description "capacitor, case c, 10uf, 25v; application:general purpose;")
      (fields (field (name "MFRPARTNUM") "EEE1EA100SR"))
      (libsource (lib "FriedParts") (part "CAP_POL"))
    )
    (comp (ref "C26")
      (value "1000u Farads 20%")
      (footprint "CAP-CAN-SMD-POL-12.5mmDia")
      (description "cap aluminum 1000uf 25vdc 20% 12.5 x 13.5mm smd 1100ma 5000")
      (fields (field (name "MFRPARTNUM") "EEV-FK1E102Q"))
      (libsource (lib "FriedParts") (part "CAP_POL"))
    )
    (comp (ref "C27")
      (value "1u Farads 10%")
      (footprint "SM/C_0603")
      (description "CAP CER 1.0UF 10V 10% X5R 0603")
      (fields (field (name "MFRPARTNUM") "GRM188R61A105KA61D"))
      (libsource (lib "FriedParts") (part "CAP NP"))
    )
    (comp (ref "C28")
      (value "1u Farads 10%")
      (footprint "SM/C_0603")
      (description "CAP CER 1.0UF 10V 10% X5R 0603")
      (fields (field (name "MFRPARTNUM") "GRM188R61A105KA61D"))
      (libsource (lib "FriedParts") (part "CAP NP"))
    )
    (comp (ref "C29")
      (value "1u Farads 10%")
      (footprint "SM/C_0603")
      (description "CAP CER 1.0UF 10V 10% X5R 0603")
      (fields (field (name "MFRPARTNUM") "GRM188R61A105KA61D"))
      (libsource (lib "FriedParts") (part "CAP NP"))
    )
    (comp (ref "C30")
      (value "1u Farads 10%")
      (footprint "SM/C_0603")
      (description "CAP CER 1.0UF 10V 10% X5R 0603")
      (fields (field (name "MFRPARTNUM") "GRM188R61A105KA61D"))
      (libsource (lib "FriedParts") (part "CAP NP"))
    )
    (comp (ref "C31")
      (value "1000p Farads 1%")
      (footprint "SM/C_0603")
      (description "capacitor ceramic 1000pf, 50v, c0g, 0603; dielectric")
      (fields (field (name "MFRPARTNUM") "06035A102FAT2A"))
      (libsource (lib "FriedParts") (part "CAP"))
    )
    (comp (ref "C32")
      (value "1000p Farads 1%")
      (footprint "SM/C_0603")
      (description "capacitor ceramic 1000pf, 50v, c0g, 0603; dielectric")
      (fields (field (name "MFRPARTNUM") "06035A102FAT2A"))
      (libsource (lib "FriedParts") (part "CAP"))
    )
    (comp (ref "C33")
      (value "1u Farads 10%")
      (footprint "SM/C_0603")
      (description "CAP CER 1.0UF 10V 10% X5R 0603")
      (fields (field (name "MFRPARTNUM") "GRM188R61A105KA61D"))
      (libsource (lib "FriedParts") (part "CAP NP"))
    )
    (comp (ref "C34")
      (value "1u Farads 10%")
      (footprint "SM/C_0603")
      (description "CAP CER 1.0UF 10V 10% X5R 0603")
      (fields (field (name "MFRPARTNUM") "GRM188R61A105KA61D"))
      (libsource (lib "FriedParts") (part "CAP NP"))
    )
    (comp (ref "C35")
      (value "1u Farads 10%")
      (footprint "SM/C_0603")
      (description "CAP CER 1.0UF 10V 10% X5R 0603")
      (fields (field (name "MFRPARTNUM") "GRM188R61A105KA61D"))
      (libsource (lib "FriedParts") (part "CAP NP"))
    )
    (comp (ref "C36")
      (value "1u Farads 10%")
      (footprint "SM/C_0603")
      (description "CAP CER 1.0UF 10V 10% X5R 0603")
      (fields (field (name "MFRPARTNUM") "GRM188R61A105KA61D"))
      (libsource (lib "FriedParts") (part "CAP NP"))
    )
    (comp (ref "C37")
      (value "1000p Farads 1%")
      (footprint "SM/C_0603")
      (description "capacitor ceramic 1000pf, 50v, c0g, 0603; dielectric")
      (fields (field (name "MFRPARTNUM") "06035A102FAT2A"))
      (libsource (lib "FriedParts") (part "CAP"))
    )
    (comp (ref "C38")
      (value "1000p Farads 1%")
      (footprint "SM/C_0603")
      (description "capacitor ceramic 1000pf, 50v, c0g, 0603; dielectric")
      (fields (field (name "MFRPARTNUM") "06035A102FAT2A"))
      (libsource (lib "FriedParts") (part "CAP"))
    )
    (comp (ref "C39")
      (value "22p Farads 10%")
      (footprint "SM/C_0603")
      (description "ceramic multilayer capacitor; capacitor type:general")
      (fields (field (name "MFRPARTNUM") "06031A220KAT2A"))
      (libsource (lib "FriedParts") (part "CAP"))
    )
    (comp (ref "C40")
      (value "1u Farads 10%")
      (footprint "SM/C_0603")
      (description "CAP CER 1.0UF 10V 10% X5R 0603")
      (fields (field (name "MFRPARTNUM") "GRM188R61A105KA61D"))
      (libsource (lib "FriedParts") (part "CAP NP"))
    )
    (comp (ref "C41")
      (value "22p Farads 10%")
      (footprint "SM/C_0603")
      (description "ceramic multilayer capacitor; capacitor type:general")
      (fields (field (name "MFRPARTNUM") "06031A220KAT2A"))
      (libsource (lib "FriedParts") (part "CAP"))
    )
    (comp (ref "C42")
      (value "1000p Farads 1%")
      (footprint "SM/C_0603")
      (description "capacitor ceramic 1000pf, 50v, c0g, 0603; dielectric")
      (fields (field (name "MFRPARTNUM") "06035A102FAT2A"))
      (libsource (lib "FriedParts") (part "CAP"))
    )
    (comp (ref "C43")
      (value "1000p Farads 1%")
      (footprint "SM/C_0603")
      (description "capacitor ceramic 1000pf, 50v, c0g, 0603; dielectric")
      (fields (field (name "MFRPARTNUM") "06035A102FAT2A"))
      (libsource (lib "FriedParts") (part "CAP"))
    )
    (comp (ref "C44")
      (value "1u Farads 10%")
      (footprint "SM/C_0603")
      (description "CAP CER 1.0UF 10V 10% X5R 0603")
      (fields (field (name "MFRPARTNUM") "GRM188R61A105KA61D"))
      (libsource (lib "FriedParts") (part "CAP NP"))
    )
    (comp (ref "C45")
      (value "1u Farads 10%")
      (footprint "SM/C_0603")
      (description "CAP CER 1.0UF 10V 10% X5R 0603")
      (fields (field (name "MFRPARTNUM") "GRM188R61A105KA61D"))
      (libsource (lib "FriedParts") (part "CAP NP"))
    )
    (comp (ref "C46")
      (value "1000p Farads 1%")
      (footprint "SM/C_0603")
      (description "capacitor ceramic 1000pf, 50v, c0g, 0603; dielectric")
      (fields (field (name "MFRPARTNUM") "06035A102FAT2A"))
      (libsource (lib "FriedParts") (part "CAP"))
    )
    (comp (ref "C47")
      (value "1000p Farads 1%")
      (footprint "SM/C_0603")
      (description "capacitor ceramic 1000pf, 50v, c0g, 0603; dielectric")
      (fields (field (name "MFRPARTNUM") "06035A102FAT2A"))
      (libsource (lib "FriedParts") (part "CAP"))
    )
    (comp (ref "C48")
      (value "1u Farads 10%")
      (footprint "SM/C_0603")
      (description "CAP CER 1.0UF 10V 10% X5R 0603")
      (fields (field (name "MFRPARTNUM") "GRM188R61A105KA61D"))
      (libsource (lib "FriedParts") (part "CAP NP"))
    )
    (comp (ref "C51")
      (value "1u Farads 10%")
      (footprint "SM/C_0603")
      (description "CAP CER 1.0UF 10V 10% X5R 0603")
      (fields (field (name "MFRPARTNUM") "GRM188R61A105KA61D"))
      (libsource (lib "FriedParts") (part "CAP NP"))
    )
    (comp (ref "C52")
      (value "1000p Farads 1%")
      (footprint "SM/C_0603")
      (description "capacitor ceramic 1000pf, 50v, c0g, 0603; dielectric")
      (fields (field (name "MFRPARTNUM") "06035A102FAT2A"))
      (libsource (lib "FriedParts") (part "CAP"))
    )
    (comp (ref "C53")
      (value "1000p Farads 1%")
      (footprint "SM/C_0603")
      (description "capacitor ceramic 1000pf, 50v, c0g, 0603; dielectric")
      (fields (field (name "MFRPARTNUM") "06035A102FAT2A"))
      (libsource (lib "FriedParts") (part "CAP"))
    )
    (comp (ref "C54")
      (value "1000p Farads 1%")
      (footprint "SM/C_0603")
      (description "capacitor ceramic 1000pf, 50v, c0g, 0603; dielectric")
      (fields (field (name "MFRPARTNUM") "06035A102FAT2A"))
      (libsource (lib "FriedParts") (part "CAP"))
    )
    (comp (ref "C55")
      (value "1000p Farads 1%")
      (footprint "SM/C_0603")
      (description "capacitor ceramic 1000pf, 50v, c0g, 0603; dielectric")
      (fields (field (name "MFRPARTNUM") "06035A102FAT2A"))
      (libsource (lib "FriedParts") (part "CAP"))
    )
    (comp (ref "C56")
      (value "1000p Farads 1%")
      (footprint "SM/C_0603")
      (description "capacitor ceramic 1000pf, 50v, c0g, 0603; dielectric")
      (fields (field (name "MFRPARTNUM") "06035A102FAT2A"))
      (libsource (lib "FriedParts") (part "CAP"))
    )
    (comp (ref "C57")
      (value "1000p Farads 1%")
      (footprint "SM/C_0603")
      (description "capacitor ceramic 1000pf, 50v, c0g, 0603; dielectric")
      (fields (field (name "MFRPARTNUM") "06035A102FAT2A"))
      (libsource (lib "FriedParts") (part "CAP"))
    )
    (comp (ref "C58")
      (value "1u Farads 10%")
      (footprint "SM/C_0603")
      (description "CAP CER 1.0UF 10V 10% X5R 0603")
      (fields (field (name "MFRPARTNUM") "GRM188R61A105KA61D"))
      (libsource (lib "FriedParts") (part "CAP NP"))
    )
    (comp (ref "C59")
      (value "1u Farads 10%")
      (footprint "SM/C_0603")
      (description "CAP CER 1.0UF 10V 10% X5R 0603")
      (fields (field (name "MFRPARTNUM") "GRM188R61A105KA61D"))
      (libsource (lib "FriedParts") (part "CAP NP"))
    )
    (comp (ref "C60")
      (value "1000p Farads 1%")
      (footprint "SM/C_0603")
      (description "capacitor ceramic 1000pf, 50v, c0g, 0603; dielectric")
      (fields (field (name "MFRPARTNUM") "06035A102FAT2A"))
      (libsource (lib "FriedParts") (part "CAP"))
    )
    (comp (ref "C61")
      (value "1000p Farads 1%")
      (footprint "SM/C_0603")
      (description "capacitor ceramic 1000pf, 50v, c0g, 0603; dielectric")
      (fields (field (name "MFRPARTNUM") "06035A102FAT2A"))
      (libsource (lib "FriedParts") (part "CAP"))
    )
    (comp (ref "C62")
      (value "1u Farads 10%")
      (footprint "SM/C_0603")
      (description "CAP CER 1.0UF 10V 10% X5R 0603")
      (fields (field (name "MFRPARTNUM") "GRM188R61A105KA61D"))
      (libsource (lib "FriedParts") (part "CAP NP"))
    )
    (comp (ref "C63")
      (value "1u Farads 10%")
      (footprint "SM/C_0603")
      (description "CAP CER 1.0UF 10V 10% X5R 0603")
      (fields (field (name "MFRPARTNUM") "GRM188R61A105KA61D"))
      (libsource (lib "FriedParts") (part "CAP NP"))
    )
    (comp (ref "C64")
      (value "1u Farads 10%")
      (footprint "SM/C_0603")
      (description "CAP CER 1.0UF 10V 10% X5R 0603")
      (fields (field (name "MFRPARTNUM") "GRM188R61A105KA61D"))
      (libsource (lib "FriedParts") (part "CAP NP"))
    )
    (comp (ref "C65")
      (value "1u Farads 10%")
      (footprint "SM/C_0603")
      (description "CAP CER 1.0UF 10V 10% X5R 0603")
      (fields (field (name "MFRPARTNUM") "GRM188R61A105KA61D"))
      (libsource (lib "FriedParts") (part "CAP NP"))
    )
    (comp (ref "C66")
      (value "1uF Farads 10%")
      (footprint "Y2-Caps-Epocs-1uF-10%")
      (description "Y2 Caps 1uF Epocs")
      (fields (field (name "MFRPARTNUM") "B32026B3105K"))
      (libsource (lib "FriedParts") (part "CAP"))
    )
    (comp (ref "C67")
      (value "1uF Farads 10%")
      (footprint "Y2-Caps-Epocs-1uF-10%")
      (description "Y2 Caps 1uF Epocs")
      (fields (field (name "MFRPARTNUM") "B32026B3105K"))
      (libsource (lib "FriedParts") (part "CAP"))
    )
    (comp (ref "C68")
      (value "1000p Farads 1%")
      (footprint "SM/C_0603")
      (description "capacitor ceramic 1000pf, 50v, c0g, 0603; dielectric")
      (fields (field (name "MFRPARTNUM") "06035A102FAT2A"))
      (libsource (lib "FriedParts") (part "CAP"))
    )
    (comp (ref "C69")
      (value "1000p Farads 1%")
      (footprint "SM/C_0603")
      (description "capacitor ceramic 1000pf, 50v, c0g, 0603; dielectric")
      (fields (field (name "MFRPARTNUM") "06035A102FAT2A"))
      (libsource (lib "FriedParts") (part "CAP"))
    )
    (comp (ref "C70")
      (value "1000p Farads 1%")
      (footprint "SM/C_0603")
      (description "capacitor ceramic 1000pf, 50v, c0g, 0603; dielectric")
      (fields (field (name "MFRPARTNUM") "06035A102FAT2A"))
      (libsource (lib "FriedParts") (part "CAP"))
    )
    (comp (ref "C71")
      (value "1000p Farads 1%")
      (footprint "SM/C_0603")
      (description "capacitor ceramic 1000pf, 50v, c0g, 0603; dielectric")
      (fields (field (name "MFRPARTNUM") "06035A102FAT2A"))
      (libsource (lib "FriedParts") (part "CAP"))
    )
    (comp (ref "C72")
      (value "1u Farads 10%")
      (footprint "SM/C_0603")
      (description "CAP CER 1.0UF 10V 10% X5R 0603")
      (fields (field (name "MFRPARTNUM") "GRM188R61A105KA61D"))
      (libsource (lib "") (part "CAP NP_1"))
    )
    (comp (ref "C73")
      (value "47p Farads 1%")
      (footprint "SM/C_0603")
      (description "ceramic multilayer capacitor; capacitor type:general")
      (fields (field (name "MFRPARTNUM") "06031A470FAT2A"))
      (libsource (lib "FriedParts") (part "CAP"))
    )
    (comp (ref "C74")
      (value "47p Farads 1%")
      (footprint "SM/C_0603")
      (description "ceramic multilayer capacitor; capacitor type:general")
      (fields (field (name "MFRPARTNUM") "06031A470FAT2A"))
      (libsource (lib "FriedParts") (part "CAP"))
    )
    (comp (ref "C75")
      (value "1u Farads 10%")
      (footprint "SM/C_0603")
      (description "CAP CER 1.0UF 10V 10% X5R 0603")
      (fields (field (name "MFRPARTNUM") "GRM188R61A105KA61D"))
      (libsource (lib "FriedParts") (part "CAP NP"))
    )
    (comp (ref "C76")
      (value "1u Farads 10%")
      (footprint "SM/C_0603")
      (description "CAP CER 1.0UF 10V 10% X5R 0603")
      (fields (field (name "MFRPARTNUM") "GRM188R61A105KA61D"))
      (libsource (lib "FriedParts") (part "CAP NP"))
    )
    (comp (ref "C77")
      (value "1u Farads 10%")
      (footprint "SM/C_0603")
      (description "CAP CER 1.0UF 10V 10% X5R 0603")
      (fields (field (name "MFRPARTNUM") "GRM188R61A105KA61D"))
      (libsource (lib "FriedParts") (part "CAP NP"))
    )
    (comp (ref "C78")
      (value "1u Farads 10%")
      (footprint "SM/C_0603")
      (description "CAP CER 1.0UF 10V 10% X5R 0603")
      (fields (field (name "MFRPARTNUM") "GRM188R61A105KA61D"))
      (libsource (lib "FriedParts") (part "CAP NP"))
    )
    (comp (ref "C79")
      (value "1u Farads 10%")
      (footprint "SM/C_0603")
      (description "CAP CER 1.0UF 10V 10% X5R 0603")
      (fields (field (name "MFRPARTNUM") "GRM188R61A105KA61D"))
      (libsource (lib "FriedParts") (part "CAP NP"))
    )
    (comp (ref "C80")
      (value "1u Farads 10%")
      (footprint "SM/C_0603")
      (description "CAP CER 1.0UF 10V 10% X5R 0603")
      (fields (field (name "MFRPARTNUM") "GRM188R61A105KA61D"))
      (libsource (lib "") (part "CAP NP_1"))
    )
    (comp (ref "C81")
      (value "1u Farads 10%")
      (footprint "SM/C_0603")
      (description "CAP CER 1.0UF 10V 10% X5R 0603")
      (fields (field (name "MFRPARTNUM") "GRM188R61A105KA61D"))
      (libsource (lib "FriedParts") (part "CAP NP"))
    )
    (comp (ref "C82")
      (value "1u Farads 10%")
      (footprint "SM/C_0603")
      (description "CAP CER 1.0UF 10V 10% X5R 0603")
      (fields (field (name "MFRPARTNUM") "GRM188R61A105KA61D"))
      (libsource (lib "FriedParts") (part "CAP NP"))
    )
    (comp (ref "C83")
      (value "1u Farads 10%")
      (footprint "SM/C_0603")
      (description "CAP CER 1.0UF 10V 10% X5R 0603")
      (fields (field (name "MFRPARTNUM") "GRM188R61A105KA61D"))
      (libsource (lib "") (part "CAP NP_1"))
    )
    (comp (ref "C84")
      (value "47p Farads 1%")
      (footprint "SM/C_0603")
      (description "ceramic multilayer capacitor; capacitor type:general")
      (fields (field (name "MFRPARTNUM") "06031A470FAT2A"))
      (libsource (lib "FriedParts") (part "CAP"))
    )
    (comp (ref "C85")
      (value "33pF Farads 1%")
      (footprint "SM/C_0603")
      (description "ceramic multilayer capacitor; capacitor type:general")
      (fields (field (name "MFRPARTNUM") "06031A330FAT2A"))
      (libsource (lib "FriedParts") (part "CAP"))
    )
    (comp (ref "C86")
      (value "47p Farads 1%")
      (footprint "SM/C_0603")
      (description "ceramic multilayer capacitor; capacitor type:general")
      (fields (field (name "MFRPARTNUM") "06031A470FAT2A"))
      (libsource (lib "FriedParts") (part "CAP"))
    )
    (comp (ref "C87")
      (value "47p Farads 1%")
      (footprint "SM/C_0603")
      (description "ceramic multilayer capacitor; capacitor type:general")
      (fields (field (name "MFRPARTNUM") "06031A470FAT2A"))
      (libsource (lib "FriedParts") (part "CAP"))
    )
    (comp (ref "C88")
      (value "1u Farads 10%")
      (footprint "SM/C_0603")
      (description "CAP CER 1.0UF 10V 10% X5R 0603")
      (fields (field (name "MFRPARTNUM") "GRM188R61A105KA61D"))
      (libsource (lib "FriedParts") (part "CAP NP"))
    )
    (comp (ref "C89")
      (value "47p Farads 1%")
      (footprint "SM/C_0603")
      (description "ceramic multilayer capacitor; capacitor type:general")
      (fields (field (name "MFRPARTNUM") "06031A470FAT2A"))
      (libsource (lib "FriedParts") (part "CAP"))
    )
    (comp (ref "C90")
      (value "47p Farads 1%")
      (footprint "SM/C_0603")
      (description "ceramic multilayer capacitor; capacitor type:general")
      (fields (field (name "MFRPARTNUM") "06031A470FAT2A"))
      (libsource (lib "FriedParts") (part "CAP"))
    )
    (comp (ref "C91")
      (value "1u Farads 10%")
      (footprint "SM/C_0603")
      (description "CAP CER 1.0UF 10V 10% X5R 0603")
      (fields (field (name "MFRPARTNUM") "GRM188R61A105KA61D"))
      (libsource (lib "FriedParts") (part "CAP NP"))
    )
    (comp (ref "C92")
      (value "1u Farads 10%")
      (footprint "SM/C_0603")
      (description "CAP CER 1.0UF 10V 10% X5R 0603")
      (fields (field (name "MFRPARTNUM") "GRM188R61A105KA61D"))
      (libsource (lib "FriedParts") (part "CAP NP"))
    )
    (comp (ref "C93")
      (value "33pF Farads 1%")
      (footprint "SM/C_0603")
      (description "ceramic multilayer capacitor; capacitor type:general")
      (fields (field (name "MFRPARTNUM") "06031A330FAT2A"))
      (libsource (lib "FriedParts") (part "CAP"))
    )
    (comp (ref "C94")
      (value "33pF Farads 1%")
      (footprint "SM/C_0603")
      (description "ceramic multilayer capacitor; capacitor type:general")
      (fields (field (name "MFRPARTNUM") "06031A330FAT2A"))
      (libsource (lib "FriedParts") (part "CAP"))
    )
    (comp (ref "C95")
      (value "1u Farads 10%")
      (footprint "SM/C_0603")
      (description "CAP CER 1.0UF 10V 10% X5R 0603")
      (fields (field (name "MFRPARTNUM") "GRM188R61A105KA61D"))
      (libsource (lib "FriedParts") (part "CAP NP"))
    )
    (comp (ref "C96")
      (value "1u Farads 10%")
      (footprint "SM/C_0603")
      (description "CAP CER 1.0UF 10V 10% X5R 0603")
      (fields (field (name "MFRPARTNUM") "GRM188R61A105KA61D"))
      (libsource (lib "FriedParts") (part "CAP NP"))
    )
    (comp (ref "C97")
      (value "47p Farads 1%")
      (footprint "SM/C_0603")
      (description "ceramic multilayer capacitor; capacitor type:general")
      (fields (field (name "MFRPARTNUM") "06031A470FAT2A"))
      (libsource (lib "FriedParts") (part "CAP"))
    )
    (comp (ref "C98")
      (value "47p Farads 1%")
      (footprint "SM/C_0603")
      (description "ceramic multilayer capacitor; capacitor type:general")
      (fields (field (name "MFRPARTNUM") "06031A470FAT2A"))
      (libsource (lib "FriedParts") (part "CAP"))
    )
    (comp (ref "C99")
      (value "47p Farads 1%")
      (footprint "SM/C_0603")
      (description "ceramic multilayer capacitor; capacitor type:general")
      (fields (field (name "MFRPARTNUM") "06031A470FAT2A"))
      (libsource (lib "FriedParts") (part "CAP"))
    )
    (comp (ref "C100")
      (value "47p Farads 1%")
      (footprint "SM/C_0603")
      (description "ceramic multilayer capacitor; capacitor type:general")
      (fields (field (name "MFRPARTNUM") "06031A470FAT2A"))
      (libsource (lib "FriedParts") (part "CAP"))
    )
    (comp (ref "C101")
      (value "1u Farads 10%")
      (footprint "SM/C_0603")
      (description "CAP CER 1.0UF 10V 10% X5R 0603")
      (fields (field (name "MFRPARTNUM") "GRM188R61A105KA61D"))
      (libsource (lib "FriedParts") (part "CAP NP"))
    )
    (comp (ref "C102")
      (value "1u Farads 10%")
      (footprint "SM/C_0603")
      (description "CAP CER 1.0UF 10V 10% X5R 0603")
      (fields (field (name "MFRPARTNUM") "GRM188R61A105KA61D"))
      (libsource (lib "FriedParts") (part "CAP NP"))
    )
    (comp (ref "C103")
      (value "1u Farads 10%")
      (footprint "SM/C_0603")
      (description "CAP CER 1.0UF 10V 10% X5R 0603")
      (fields (field (name "MFRPARTNUM") "GRM188R61A105KA61D"))
      (libsource (lib "FriedParts") (part "CAP NP"))
    )
    (comp (ref "C104")
      (value "33pF Farads 1%")
      (footprint "SM/C_0603")
      (description "ceramic multilayer capacitor; capacitor type:general")
      (fields (field (name "MFRPARTNUM") "06031A330FAT2A"))
      (libsource (lib "FriedParts") (part "CAP"))
    )
    (comp (ref "C105")
      (value "47p Farads 1%")
      (footprint "SM/C_0603")
      (description "ceramic multilayer capacitor; capacitor type:general")
      (fields (field (name "MFRPARTNUM") "06031A470FAT2A"))
      (libsource (lib "FriedParts") (part "CAP"))
    )
    (comp (ref "C106")
      (value "1u Farads 10%")
      (footprint "SM/C_0603")
      (description "CAP CER 1.0UF 10V 10% X5R 0603")
      (fields (field (name "MFRPARTNUM") "GRM188R61A105KA61D"))
      (libsource (lib "") (part "CAP NP_1"))
    )
    (comp (ref "C107")
      (value "1000p Farads 1%")
      (footprint "SM/C_0603")
      (description "capacitor ceramic 1000pf, 50v, c0g, 0603; dielectric")
      (fields (field (name "MFRPARTNUM") "06035A102FAT2A"))
      (libsource (lib "FriedParts") (part "CAP"))
    )
    (comp (ref "C108")
      (value "1000p Farads 1%")
      (footprint "SM/C_0603")
      (description "capacitor ceramic 1000pf, 50v, c0g, 0603; dielectric")
      (fields (field (name "MFRPARTNUM") "06035A102FAT2A"))
      (libsource (lib "FriedParts") (part "CAP"))
    )
    (comp (ref "C120")
      (value "1u Farads 10%")
      (footprint "SM/C_0603")
      (description "CAP CER 1.0UF 10V 10% X5R 0603")
      (fields (field (name "MFRPARTNUM") "GRM188R61A105KA61D"))
      (libsource (lib "FriedParts") (part "CAP NP"))
    )
    (comp (ref "C121")
      (value "1u Farads 10%")
      (footprint "SM/C_0603")
      (description "CAP CER 1.0UF 10V 10% X5R 0603")
      (fields (field (name "MFRPARTNUM") "GRM188R61A105KA61D"))
      (libsource (lib "FriedParts") (part "CAP NP"))
    )
    (comp (ref "CN1")
      (value "Mini B Socket R/A USB Type Per Spec")
      (footprint "MOLEX/54819-0579")
      (description "CONN RECEPT USB MINI-B R/A 5POS SMD")
      (fields (field (name "MFRPARTNUM") "54819-0572"))
      (libsource (lib "FriedParts") (part "USB_MINI_B/5"))
    )
    (comp (ref "CON1")
      (value "5227161-1")
      (footprint "BNC-RightAngle-PCB-50Ohm-Termination")
      (description "jack bnc, right angle, pcb; connector type:bnc, coaxial;")
      (libsource (lib "FriedParts") (part "BNC"))
    )
    (comp (ref "CON2")
      (value "M06x2 Header")
      (footprint "2010_Thomas:6-pin 2mm")
      (libsource (lib "FriedParts") (part "M06x2 Header"))
    )
    (comp (ref "CON6")
      (value "5227161-1")
      (footprint "BNC-RightAngle-PCB-50Ohm-Termination")
      (description "jack bnc, right angle, pcb; connector type:bnc, coaxial;")
      (libsource (lib "FriedParts") (part "BNC"))
    )
    (comp (ref "CON7")
      (value "5227161-1")
      (footprint "BNC-RightAngle-PCB-50Ohm-Termination")
      (description "jack bnc, right angle, pcb; connector type:bnc, coaxial;")
      (libsource (lib "FriedParts") (part "BNC"))
    )
    (comp (ref "CON8")
      (value "5227161-1")
      (footprint "BNC-RightAngle-PCB-50Ohm-Termination")
      (description "jack bnc, right angle, pcb; connector type:bnc, coaxial;")
      (libsource (lib "FriedParts") (part "BNC"))
    )
    (comp (ref "CON9")
      (value "5227161-1")
      (footprint "BNC-RightAngle-PCB-50Ohm-Termination")
      (description "jack bnc, right angle, pcb; connector type:bnc, coaxial;")
      (libsource (lib "FriedParts") (part "BNC"))
    )
    (comp (ref "CON10")
      (value "5227161-1")
      (footprint "BNC-RightAngle-PCB-50Ohm-Termination")
      (description "jack bnc, right angle, pcb; connector type:bnc, coaxial;")
      (libsource (lib "FriedParts") (part "BNC"))
    )
    (comp (ref "CON_FGND")
      (value "1299")
      (footprint "LOW-PROFILE-SCREWTERMINAL")
      (description "brass tin plate low profile 10 - 32 thread with anti")
      (libsource (lib "FriedParts") (part "ScrewTerminal-PCB-ThruHole"))
    )
    (comp (ref "CON_L1")
      (value "1299")
      (footprint "LOW-PROFILE-SCREWTERMINAL")
      (description "brass tin plate low profile 10 - 32 thread with anti")
      (libsource (lib "FriedParts") (part "ScrewTerminal-PCB-ThruHole"))
    )
    (comp (ref "CON_L2")
      (value "1299")
      (footprint "LOW-PROFILE-SCREWTERMINAL")
      (description "brass tin plate low profile 10 - 32 thread with anti")
      (libsource (lib "FriedParts") (part "ScrewTerminal-PCB-ThruHole"))
    )
    (comp (ref "CON_N1")
      (value "1299")
      (footprint "LOW-PROFILE-SCREWTERMINAL")
      (description "brass tin plate low profile 10 - 32 thread with anti")
      (libsource (lib "FriedParts") (part "ScrewTerminal-PCB-ThruHole"))
    )
    (comp (ref "CON_N2")
      (value "1299")
      (footprint "LOW-PROFILE-SCREWTERMINAL")
      (description "brass tin plate low profile 10 - 32 thread with anti")
      (libsource (lib "FriedParts") (part "ScrewTerminal-PCB-ThruHole"))
    )
    (comp (ref "D1")
      (value "red")
      (footprint "LITEON/LED/0603")
      (description "LED SUPER RED CLEAR 0603 SMD")
      (fields (field (name "MFRPARTNUM") "LTST-C190KRKT") (field (name "PUBLISHER") "Altium Limited"))
      (libsource (lib "FriedParts") (part "LITEON/LED RED"))
    )
    (comp (ref "D2")
      (value "red")
      (footprint "LITEON/LED/0603")
      (description "LED SUPER RED CLEAR 0603 SMD")
      (fields (field (name "MFRPARTNUM") "LTST-C190KRKT") (field (name "PUBLISHER") "Altium Limited"))
      (libsource (lib "FriedParts") (part "LITEON/LED RED"))
    )
    (comp (ref "D3")
      (value "red")
      (footprint "LITEON/LED/0603")
      (description "LED SUPER RED CLEAR 0603 SMD")
      (fields (field (name "MFRPARTNUM") "LTST-C190KRKT") (field (name "PUBLISHER") "Altium Limited"))
      (libsource (lib "FriedParts") (part "LITEON/LED RED"))
    )
    (comp (ref "D4")
      (value "red")
      (footprint "LITEON/LED/0603")
      (description "LED SUPER RED CLEAR 0603 SMD")
      (fields (field (name "MFRPARTNUM") "LTST-C190KRKT") (field (name "PUBLISHER") "Altium Limited"))
      (libsource (lib "FriedParts") (part "LITEON/LED RED"))
    )
    (comp (ref "D_STAT1")
      (value "red")
      (footprint "LITEON/LED/0603")
      (description "LED SUPER RED CLEAR 0603 SMD")
      (fields (field (name "MFRPARTNUM") "LTST-C190KRKT") (field (name "PUBLISHER") "Altium Limited"))
      (libsource (lib "FriedParts") (part "LITEON/LED RED"))
    )
    (comp (ref "D_STAT2")
      (value "red")
      (footprint "LITEON/LED/0603")
      (description "LED SUPER RED CLEAR 0603 SMD")
      (fields (field (name "MFRPARTNUM") "LTST-C190KRKT") (field (name "PUBLISHER") "Altium Limited"))
      (libsource (lib "FriedParts") (part "LITEON/LED RED"))
    )
    (comp (ref "D_STAT3")
      (value "red")
      (footprint "LITEON/LED/0603")
      (description "LED SUPER RED CLEAR 0603 SMD")
      (fields (field (name "MFRPARTNUM") "LTST-C190KRKT") (field (name "PUBLISHER") "Altium Limited"))
      (libsource (lib "FriedParts") (part "LITEON/LED RED"))
    )
    (comp (ref "D_STAT4")
      (value "red")
      (footprint "LITEON/LED/0603")
      (description "LED SUPER RED CLEAR 0603 SMD")
      (fields (field (name "MFRPARTNUM") "LTST-C190KRKT") (field (name "PUBLISHER") "Altium Limited"))
      (libsource (lib "FriedParts") (part "LITEON/LED RED"))
    )
    (comp (ref "F1")
      (value "110V @ 2 AMP Fast Blow")
      (footprint "WICKMANN/WK0011-ND")
      (description "FUSEHOLDER OPEN 5X20MM PC MNT")
      (fields (field (name "MFRPARTNUM") "6490000100"))
      (libsource (lib "FriedParts") (part "FUSEHOLDER"))
    )
    (comp (ref "F2")
      (value "110V @ 100 milliamp Fast Blow")
      (footprint "WICKMANN/WK0011-ND")
      (description "FUSEHOLDER OPEN 5X20MM PC MNT")
      (fields (field (name "MFRPARTNUM") "6490000100"))
      (libsource (lib "FriedParts") (part "FUSEHOLDER"))
    )
    (comp (ref "F3")
      (value "110V @ 100 milliamp Fast Blow")
      (footprint "WICKMANN/WK0011-ND")
      (description "FUSEHOLDER OPEN 5X20MM PC MNT")
      (fields (field (name "MFRPARTNUM") "6490000100"))
      (libsource (lib "FriedParts") (part "FUSEHOLDER"))
    )
    (comp (ref "R1")
      (value "1k Ohms 1%")
      (footprint "SM/C_0603")
      (description "RES 1.00K OHM 1/10W 1% 0603 SMD")
      (fields (field (name "MFRPARTNUM") "ERJ-3EKF1001V"))
      (libsource (lib "FriedParts") (part "R"))
    )
    (comp (ref "R2")
      (value "1k Ohms 1%")
      (footprint "SM/C_0603")
      (description "RES 1.00K OHM 1/10W 1% 0603 SMD")
      (fields (field (name "MFRPARTNUM") "ERJ-3EKF1001V"))
      (libsource (lib "FriedParts") (part "R"))
    )
    (comp (ref "R3")
      (value "330 Ohms 1%")
      (footprint "SM/C_0603")
      (description "RES 330 OHM 1/10W 1% 0603 SMD")
      (fields (field (name "MFRPARTNUM") "ERJ-3EKF3300V"))
      (libsource (lib "FriedParts") (part "R"))
    )
    (comp (ref "R4")
      (value "1k Ohms 1%")
      (footprint "SM/C_0603")
      (description "RES 1.00K OHM 1/10W 1% 0603 SMD")
      (fields (field (name "MFRPARTNUM") "ERJ-3EKF1001V"))
      (libsource (lib "FriedParts") (part "R"))
    )
    (comp (ref "R5")
      (value "10k ohm 1%")
      (footprint "SM/C_0603")
      (description "resistor, 0603, 0.1w, 1%, 10k; resistance:10kohm; resistance")
      (fields (field (name "MFRPARTNUM") "ERJ-3EKF1002V") (field (name "PUBLISHER") "Altium Limited"))
      (libsource (lib "FriedParts") (part "Res1"))
    )
    (comp (ref "R6")
      (value "3k Ohms 1%")
      (footprint "SM/C_0603")
      (description "resistor, thick film, 30kohm, 100mw, 1%; resistance:30kohm;")
      (fields (field (name "MFRPARTNUM") "RC0603FR-0730KL") (field (name "PUBLISHER") "Altium Limited"))
      (libsource (lib "FriedParts") (part "Res1"))
    )
    (comp (ref "R7")
      (value "330 Ohms 1%")
      (footprint "SM/C_0603")
      (description "RES 330 OHM 1/10W 1% 0603 SMD")
      (fields (field (name "MFRPARTNUM") "ERJ-3EKF3300V"))
      (libsource (lib "FriedParts") (part "R"))
    )
    (comp (ref "R8")
      (value "1k Ohms 1%")
      (footprint "SM/C_0603")
      (description "RES 1.00K OHM 1/10W 1% 0603 SMD")
      (fields (field (name "MFRPARTNUM") "ERJ-3EKF1001V"))
      (libsource (lib "FriedParts") (part "R"))
    )
    (comp (ref "R9")
      (value "1k Ohms 1%")
      (footprint "SM/C_0603")
      (description "RES 1.00K OHM 1/10W 1% 0603 SMD")
      (fields (field (name "MFRPARTNUM") "ERJ-3EKF1001V"))
      (libsource (lib "FriedParts") (part "R"))
    )
    (comp (ref "R10")
      (value "1k Ohms 1%")
      (footprint "SM/C_0603")
      (description "RES 1.00K OHM 1/10W 1% 0603 SMD")
      (fields (field (name "MFRPARTNUM") "ERJ-3EKF1001V"))
      (libsource (lib "FriedParts") (part "R"))
    )
    (comp (ref "R11")
      (value "1k Ohms 1%")
      (footprint "SM/C_0603")
      (description "RES 1.00K OHM 1/10W 1% 0603 SMD")
      (fields (field (name "MFRPARTNUM") "ERJ-3EKF1001V"))
      (libsource (lib "FriedParts") (part "R"))
    )
    (comp (ref "R12")
      (value "1k Ohms 1%")
      (footprint "SM/C_0603")
      (description "RES 1.00K OHM 1/10W 1% 0603 SMD")
      (fields (field (name "MFRPARTNUM") "ERJ-3EKF1001V"))
      (libsource (lib "FriedParts") (part "R"))
    )
    (comp (ref "R13")
      (value "1k Ohms 1%")
      (footprint "SM/C_0603")
      (description "RES 1.00K OHM 1/10W 1% 0603 SMD")
      (fields (field (name "MFRPARTNUM") "ERJ-3EKF1001V"))
      (libsource (lib "FriedParts") (part "R"))
    )
    (comp (ref "R14")
      (value "1k Ohms 1%")
      (footprint "SM/C_0603")
      (description "RES 1.00K OHM 1/10W 1% 0603 SMD")
      (fields (field (name "MFRPARTNUM") "ERJ-3EKF1001V"))
      (libsource (lib "FriedParts") (part "R"))
    )
    (comp (ref "R15")
      (value "330 Ohms 1%")
      (footprint "SM/C_0603")
      (description "RES 330 OHM 1/10W 1% 0603 SMD")
      (fields (field (name "MFRPARTNUM") "ERJ-3EKF3300V"))
      (libsource (lib "FriedParts") (part "R"))
    )
    (comp (ref "R16")
      (value "2.7M Ohm 1%")
      (footprint "SM/R_0603")
      (description "res, thick film, 2.7mohm, 100mw, 1%; resistance:2.7mohm;")
      (fields (field (name "MFRPARTNUM") "CRCW06032M70FKEA") (field (name "PUBLISHER") "Altium Limited"))
      (libsource (lib "FriedParts") (part "Res1"))
    )
    (comp (ref "R17")
      (value "2.7M Ohm 1%")
      (footprint "SM/R_0603")
      (description "res, thick film, 2.7mohm, 100mw, 1%; resistance:2.7mohm;")
      (fields (field (name "MFRPARTNUM") "CRCW06032M70FKEA") (field (name "PUBLISHER") "Altium Limited"))
      (libsource (lib "FriedParts") (part "Res1"))
    )
    (comp (ref "R18")
      (value "1k Ohms 1%")
      (footprint "SM/C_0603")
      (description "RES 1.00K OHM 1/10W 1% 0603 SMD")
      (fields (field (name "MFRPARTNUM") "ERJ-3EKF1001V"))
      (libsource (lib "FriedParts") (part "R"))
    )
    (comp (ref "R19")
      (value "2.7M Ohm 1%")
      (footprint "SM/R_0603")
      (description "res, thick film, 2.7mohm, 100mw, 1%; resistance:2.7mohm;")
      (fields (field (name "MFRPARTNUM") "CRCW06032M70FKEA") (field (name "PUBLISHER") "Altium Limited"))
      (libsource (lib "FriedParts") (part "Res1"))
    )
    (comp (ref "R20")
      (value "2.7M Ohm 1%")
      (footprint "SM/R_0603")
      (description "res, thick film, 2.7mohm, 100mw, 1%; resistance:2.7mohm;")
      (fields (field (name "MFRPARTNUM") "CRCW06032M70FKEA") (field (name "PUBLISHER") "Altium Limited"))
      (libsource (lib "FriedParts") (part "Res1"))
    )
    (comp (ref "R21")
      (value "1k Ohms 1%")
      (footprint "SM/C_0603")
      (description "RES 1.00K OHM 1/10W 1% 0603 SMD")
      (fields (field (name "MFRPARTNUM") "ERJ-3EKF1001V"))
      (libsource (lib "FriedParts") (part "R"))
    )
    (comp (ref "R22")
      (value "2.7M Ohm 1%")
      (footprint "SM/R_0603")
      (description "res, thick film, 2.7mohm, 100mw, 1%; resistance:2.7mohm;")
      (fields (field (name "MFRPARTNUM") "CRCW06032M70FKEA") (field (name "PUBLISHER") "Altium Limited"))
      (libsource (lib "FriedParts") (part "Res1"))
    )
    (comp (ref "R23")
      (value "2.7M Ohm 1%")
      (footprint "SM/R_0603")
      (description "res, thick film, 2.7mohm, 100mw, 1%; resistance:2.7mohm;")
      (fields (field (name "MFRPARTNUM") "CRCW06032M70FKEA") (field (name "PUBLISHER") "Altium Limited"))
      (libsource (lib "FriedParts") (part "Res1"))
    )
    (comp (ref "R24")
      (value "330 Ohms 1%")
      (footprint "SM/C_0603")
      (description "RES 330 OHM 1/10W 1% 0603 SMD")
      (fields (field (name "MFRPARTNUM") "ERJ-3EKF3300V"))
      (libsource (lib "FriedParts") (part "R"))
    )
    (comp (ref "R25")
      (value "2.7M Ohm 1%")
      (footprint "SM/R_0603")
      (description "res, thick film, 2.7mohm, 100mw, 1%; resistance:2.7mohm;")
      (fields (field (name "MFRPARTNUM") "CRCW06032M70FKEA") (field (name "PUBLISHER") "Altium Limited"))
      (libsource (lib "FriedParts") (part "Res1"))
    )
    (comp (ref "R26")
      (value "2.7M Ohm 1%")
      (footprint "SM/R_0603")
      (description "res, thick film, 2.7mohm, 100mw, 1%; resistance:2.7mohm;")
      (fields (field (name "MFRPARTNUM") "CRCW06032M70FKEA") (field (name "PUBLISHER") "Altium Limited"))
      (libsource (lib "FriedParts") (part "Res1"))
    )
    (comp (ref "R27")
      (value "30k Ohms 1%")
      (footprint "Resistor-3.2mm x 1.70mm")
      (description "Resistor")
      (fields (field (name "MFRPARTNUM") "ERO-S2PHF3002-2") (field (name "PUBLISHER") "Altium Limited"))
      (libsource (lib "FriedParts") (part "Res1"))
    )
    (comp (ref "R28")
      (value "1k Ohms 1%")
      (footprint "SM/C_0603")
      (description "RES 1.00K OHM 1/10W 1% 0603 SMD")
      (fields (field (name "MFRPARTNUM") "ERJ-3EKF1001V"))
      (libsource (lib "FriedParts") (part "R"))
    )
    (comp (ref "R29")
      (value "2.7M Ohm 1%")
      (footprint "SM/R_0603")
      (description "res, thick film, 2.7mohm, 100mw, 1%; resistance:2.7mohm;")
      (fields (field (name "MFRPARTNUM") "CRCW06032M70FKEA") (field (name "PUBLISHER") "Altium Limited"))
      (libsource (lib "FriedParts") (part "Res1"))
    )
    (comp (ref "R30")
      (value "2.7M Ohm 1%")
      (footprint "SM/R_0603")
      (description "res, thick film, 2.7mohm, 100mw, 1%; resistance:2.7mohm;")
      (fields (field (name "MFRPARTNUM") "CRCW06032M70FKEA") (field (name "PUBLISHER") "Altium Limited"))
      (libsource (lib "FriedParts") (part "Res1"))
    )
    (comp (ref "R31")
      (value "2.7M Ohm 1%")
      (footprint "SM/R_0603")
      (description "res, thick film, 2.7mohm, 100mw, 1%; resistance:2.7mohm;")
      (fields (field (name "MFRPARTNUM") "CRCW06032M70FKEA") (field (name "PUBLISHER") "Altium Limited"))
      (libsource (lib "FriedParts") (part "Res1"))
    )
    (comp (ref "R32")
      (value "30k Ohms 1%")
      (footprint "Resistor-3.2mm x 1.70mm")
      (description "Resistor")
      (fields (field (name "MFRPARTNUM") "ERO-S2PHF3002-2") (field (name "PUBLISHER") "Altium Limited"))
      (libsource (lib "FriedParts") (part "Res1"))
    )
    (comp (ref "R33")
      (value "30k Ohms 1%")
      (footprint "Resistor-3.2mm x 1.70mm")
      (description "Resistor")
      (fields (field (name "MFRPARTNUM") "ERO-S2PHF3002-2") (field (name "PUBLISHER") "Altium Limited"))
      (libsource (lib "FriedParts") (part "Res1"))
    )
    (comp (ref "R34")
      (value "10k ohm 1%")
      (footprint "SM/C_0603")
      (description "resistor, 0603, 0.1w, 1%, 10k; resistance:10kohm; resistance")
      (fields (field (name "MFRPARTNUM") "ERJ-3EKF1002V") (field (name "PUBLISHER") "Altium Limited"))
      (libsource (lib "FriedParts") (part "Res1"))
    )
    (comp (ref "R35")
      (value "3k Ohms 1%")
      (footprint "SM/C_0603")
      (description "resistor, thick film, 30kohm, 100mw, 1%; resistance:30kohm;")
      (fields (field (name "MFRPARTNUM") "RC0603FR-0730KL") (field (name "PUBLISHER") "Altium Limited"))
      (libsource (lib "FriedParts") (part "Res1"))
    )
    (comp (ref "R36")
      (value "1k Ohms 1%")
      (footprint "SM/C_0603")
      (description "RES 1.00K OHM 1/10W 1% 0603 SMD")
      (fields (field (name "MFRPARTNUM") "ERJ-3EKF1001V"))
      (libsource (lib "FriedParts") (part "R"))
    )
    (comp (ref "R37")
      (value "0 Ohms 0")
      (footprint "SM/R_0603")
      (description "res thick film 0603 0 ohm 1/10w molded smd punched carrier")
      (fields (field (name "MFRPARTNUM") "ERJ-3GEY0R00V") (field (name "PUBLISHER") "Altium Limited"))
      (libsource (lib "FriedParts") (part "Res1"))
    )
    (comp (ref "R38")
      (value "1k Ohms 1%")
      (footprint "SM/C_0603")
      (description "RES 1.00K OHM 1/10W 1% 0603 SMD")
      (fields (field (name "MFRPARTNUM") "ERJ-3EKF1001V"))
      (libsource (lib "FriedParts") (part "R"))
    )
    (comp (ref "R39")
      (value "50 Ohm 1%")
      (footprint "SM/R_0603")
      (description "; resistance:50ohm; resistance tolerance:± 0.1%; power")
      (fields (field (name "MFRPARTNUM") "FC0603E50R0BTBST1") (field (name "PUBLISHER") "Altium Limited"))
      (libsource (lib "FriedParts") (part "Res1"))
    )
    (comp (ref "R40")
      (value "1k Ohms 1%")
      (footprint "SM/C_0603")
      (description "RES 1.00K OHM 1/10W 1% 0603 SMD")
      (fields (field (name "MFRPARTNUM") "ERJ-3EKF1001V"))
      (libsource (lib "FriedParts") (part "R"))
    )
    (comp (ref "R41")
      (value "2.7M Ohm 1%")
      (footprint "SM/R_0603")
      (description "res, thick film, 2.7mohm, 100mw, 1%; resistance:2.7mohm;")
      (fields (field (name "MFRPARTNUM") "CRCW06032M70FKEA") (field (name "PUBLISHER") "Altium Limited"))
      (libsource (lib "FriedParts") (part "Res1"))
    )
    (comp (ref "R42")
      (value "2.7M Ohm 1%")
      (footprint "SM/R_0603")
      (description "res, thick film, 2.7mohm, 100mw, 1%; resistance:2.7mohm;")
      (fields (field (name "MFRPARTNUM") "CRCW06032M70FKEA") (field (name "PUBLISHER") "Altium Limited"))
      (libsource (lib "FriedParts") (part "Res1"))
    )
    (comp (ref "R43")
      (value "22 ohms 1%")
      (footprint "SM/C_0603")
      (description "rating:75v; temperature coefficient")
      (fields (field (name "MFRPARTNUM") "ERJ3EKF22R0V") (field (name "PUBLISHER") "Altium Limited"))
      (libsource (lib "FriedParts") (part "Res1"))
    )
    (comp (ref "R44")
      (value "10k ohm 1%")
      (footprint "SM/C_0603")
      (description "resistor, 0603, 0.1w, 1%, 10k; resistance:10kohm; resistance")
      (fields (field (name "MFRPARTNUM") "ERJ-3EKF1002V") (field (name "PUBLISHER") "Altium Limited"))
      (libsource (lib "FriedParts") (part "Res1"))
    )
    (comp (ref "R45")
      (value "1k Ohms 1%")
      (footprint "SM/C_0603")
      (description "RES 1.00K OHM 1/10W 1% 0603 SMD")
      (fields (field (name "MFRPARTNUM") "ERJ-3EKF1001V"))
      (libsource (lib "FriedParts") (part "R"))
    )
    (comp (ref "R46")
      (value "1k Ohms 1%")
      (footprint "SM/C_0603")
      (description "RES 1.00K OHM 1/10W 1% 0603 SMD")
      (fields (field (name "MFRPARTNUM") "ERJ-3EKF1001V"))
      (libsource (lib "FriedParts") (part "R"))
    )
    (comp (ref "R47")
      (value "22 ohms 1%")
      (footprint "SM/C_0603")
      (description "rating:75v; temperature coefficient")
      (fields (field (name "MFRPARTNUM") "ERJ3EKF22R0V") (field (name "PUBLISHER") "Altium Limited"))
      (libsource (lib "FriedParts") (part "Res1"))
    )
    (comp (ref "R48")
      (value "1k Ohms 1%")
      (footprint "SM/C_0603")
      (description "RES 1.00K OHM 1/10W 1% 0603 SMD")
      (fields (field (name "MFRPARTNUM") "ERJ-3EKF1001V"))
      (libsource (lib "FriedParts") (part "R"))
    )
    (comp (ref "R49")
      (value "2.7M Ohm 1%")
      (footprint "SM/R_0603")
      (description "res, thick film, 2.7mohm, 100mw, 1%; resistance:2.7mohm;")
      (fields (field (name "MFRPARTNUM") "CRCW06032M70FKEA") (field (name "PUBLISHER") "Altium Limited"))
      (libsource (lib "FriedParts") (part "Res1"))
    )
    (comp (ref "R50")
      (value "2.7M Ohm 1%")
      (footprint "SM/R_0603")
      (description "res, thick film, 2.7mohm, 100mw, 1%; resistance:2.7mohm;")
      (fields (field (name "MFRPARTNUM") "CRCW06032M70FKEA") (field (name "PUBLISHER") "Altium Limited"))
      (libsource (lib "FriedParts") (part "Res1"))
    )
    (comp (ref "R51")
      (value "1k Ohms 1%")
      (footprint "SM/C_0603")
      (description "RES 1.00K OHM 1/10W 1% 0603 SMD")
      (fields (field (name "MFRPARTNUM") "ERJ-3EKF1001V"))
      (libsource (lib "FriedParts") (part "R"))
    )
    (comp (ref "R52")
      (value "1k Ohms 1%")
      (footprint "SM/C_0603")
      (description "RES 1.00K OHM 1/10W 1% 0603 SMD")
      (fields (field (name "MFRPARTNUM") "ERJ-3EKF1001V"))
      (libsource (lib "FriedParts") (part "R"))
    )
    (comp (ref "R53")
      (value "10k ohm 1%")
      (footprint "SM/C_0603")
      (description "resistor, 0603, 0.1w, 1%, 10k; resistance:10kohm; resistance")
      (fields (field (name "MFRPARTNUM") "ERJ-3EKF1002V") (field (name "PUBLISHER") "Altium Limited"))
      (libsource (lib "FriedParts") (part "Res1"))
    )
    (comp (ref "R54")
      (value "2.7M Ohm 1%")
      (footprint "SM/R_0603")
      (description "res, thick film, 2.7mohm, 100mw, 1%; resistance:2.7mohm;")
      (fields (field (name "MFRPARTNUM") "CRCW06032M70FKEA") (field (name "PUBLISHER") "Altium Limited"))
      (libsource (lib "FriedParts") (part "Res1"))
    )
    (comp (ref "R55")
      (value "2.7M Ohm 1%")
      (footprint "SM/R_0603")
      (description "res, thick film, 2.7mohm, 100mw, 1%; resistance:2.7mohm;")
      (fields (field (name "MFRPARTNUM") "CRCW06032M70FKEA") (field (name "PUBLISHER") "Altium Limited"))
      (libsource (lib "FriedParts") (part "Res1"))
    )
    (comp (ref "R56")
      (value "330 Ohms 1%")
      (footprint "SM/C_0603")
      (description "RES 330 OHM 1/10W 1% 0603 SMD")
      (fields (field (name "MFRPARTNUM") "ERJ-3EKF3300V"))
      (libsource (lib "FriedParts") (part "R"))
    )
    (comp (ref "R57")
      (value "1k Ohms 1%")
      (footprint "SM/C_0603")
      (description "RES 1.00K OHM 1/10W 1% 0603 SMD")
      (fields (field (name "MFRPARTNUM") "ERJ-3EKF1001V"))
      (libsource (lib "FriedParts") (part "R"))
    )
    (comp (ref "R58")
      (value "2.7M Ohm 1%")
      (footprint "SM/R_0603")
      (description "res, thick film, 2.7mohm, 100mw, 1%; resistance:2.7mohm;")
      (fields (field (name "MFRPARTNUM") "CRCW06032M70FKEA") (field (name "PUBLISHER") "Altium Limited"))
      (libsource (lib "FriedParts") (part "Res1"))
    )
    (comp (ref "R59")
      (value "2.7M Ohm 1%")
      (footprint "SM/R_0603")
      (description "res, thick film, 2.7mohm, 100mw, 1%; resistance:2.7mohm;")
      (fields (field (name "MFRPARTNUM") "CRCW06032M70FKEA") (field (name "PUBLISHER") "Altium Limited"))
      (libsource (lib "FriedParts") (part "Res1"))
    )
    (comp (ref "R60")
      (value "1k Ohms 1%")
      (footprint "SM/C_0603")
      (description "RES 1.00K OHM 1/10W 1% 0603 SMD")
      (fields (field (name "MFRPARTNUM") "ERJ-3EKF1001V"))
      (libsource (lib "FriedParts") (part "R"))
    )
    (comp (ref "R70")
      (value "1k Ohms 1%")
      (footprint "SM/C_0603")
      (description "RES 1.00K OHM 1/10W 1% 0603 SMD")
      (fields (field (name "MFRPARTNUM") "ERJ-3EKF1001V"))
      (libsource (lib "FriedParts") (part "R"))
    )
    (comp (ref "R71")
      (value "2.7M Ohm 1%")
      (footprint "SM/R_0603")
      (description "res, thick film, 2.7mohm, 100mw, 1%; resistance:2.7mohm;")
      (fields (field (name "MFRPARTNUM") "CRCW06032M70FKEA") (field (name "PUBLISHER") "Altium Limited"))
      (libsource (lib "FriedParts") (part "Res1"))
    )
    (comp (ref "R72")
      (value "2.7M Ohm 1%")
      (footprint "SM/R_0603")
      (description "res, thick film, 2.7mohm, 100mw, 1%; resistance:2.7mohm;")
      (fields (field (name "MFRPARTNUM") "CRCW06032M70FKEA") (field (name "PUBLISHER") "Altium Limited"))
      (libsource (lib "FriedParts") (part "Res1"))
    )
    (comp (ref "R73")
      (value "2.7M Ohm 1%")
      (footprint "SM/R_0603")
      (description "res, thick film, 2.7mohm, 100mw, 1%; resistance:2.7mohm;")
      (fields (field (name "MFRPARTNUM") "CRCW06032M70FKEA") (field (name "PUBLISHER") "Altium Limited"))
      (libsource (lib "FriedParts") (part "Res1"))
    )
    (comp (ref "R74")
      (value "2.7M Ohm 1%")
      (footprint "SM/R_0603")
      (description "res, thick film, 2.7mohm, 100mw, 1%; resistance:2.7mohm;")
      (fields (field (name "MFRPARTNUM") "CRCW06032M70FKEA") (field (name "PUBLISHER") "Altium Limited"))
      (libsource (lib "FriedParts") (part "Res1"))
    )
    (comp (ref "R75")
      (value "2.7M Ohm 1%")
      (footprint "SM/R_0603")
      (description "res, thick film, 2.7mohm, 100mw, 1%; resistance:2.7mohm;")
      (fields (field (name "MFRPARTNUM") "CRCW06032M70FKEA") (field (name "PUBLISHER") "Altium Limited"))
      (libsource (lib "FriedParts") (part "Res1"))
    )
    (comp (ref "R76")
      (value "0 Ohms 0")
      (footprint "SM/R_0603")
      (description "res thick film 0603 0 ohm 1/10w molded smd punched carrier")
      (fields (field (name "MFRPARTNUM") "ERJ-3GEY0R00V") (field (name "PUBLISHER") "Altium Limited"))
      (libsource (lib "FriedParts") (part "Res1"))
    )
    (comp (ref "R77")
      (value "2.7M Ohm 1%")
      (footprint "SM/R_0603")
      (description "res, thick film, 2.7mohm, 100mw, 1%; resistance:2.7mohm;")
      (fields (field (name "MFRPARTNUM") "CRCW06032M70FKEA") (field (name "PUBLISHER") "Altium Limited"))
      (libsource (lib "FriedParts") (part "Res1"))
    )
    (comp (ref "R78")
      (value "10k ohm 1%")
      (footprint "SM/C_0603")
      (description "resistor, 0603, 0.1w, 1%, 10k; resistance:10kohm; resistance")
      (fields (field (name "MFRPARTNUM") "ERJ-3EKF1002V") (field (name "PUBLISHER") "Altium Limited"))
      (libsource (lib "FriedParts") (part "Res1"))
    )
    (comp (ref "R79")
      (value "2.7M Ohm 1%")
      (footprint "SM/R_0603")
      (description "res, thick film, 2.7mohm, 100mw, 1%; resistance:2.7mohm;")
      (fields (field (name "MFRPARTNUM") "CRCW06032M70FKEA") (field (name "PUBLISHER") "Altium Limited"))
      (libsource (lib "FriedParts") (part "Res1"))
    )
    (comp (ref "R80")
      (value "50 Ohm 1%")
      (footprint "SM/R_0603")
      (description "; resistance:50ohm; resistance tolerance:± 0.1%; power")
      (fields (field (name "MFRPARTNUM") "FC0603E50R0BTBST1") (field (name "PUBLISHER") "Altium Limited"))
      (libsource (lib "FriedParts") (part "Res1"))
    )
    (comp (ref "R81")
      (value "2.7M Ohm 1%")
      (footprint "SM/R_0603")
      (description "res, thick film, 2.7mohm, 100mw, 1%; resistance:2.7mohm;")
      (fields (field (name "MFRPARTNUM") "CRCW06032M70FKEA") (field (name "PUBLISHER") "Altium Limited"))
      (libsource (lib "FriedParts") (part "Res1"))
    )
    (comp (ref "R82")
      (value "10k ohm 1%")
      (footprint "SM/C_0603")
      (description "resistor, 0603, 0.1w, 1%, 10k; resistance:10kohm; resistance")
      (fields (field (name "MFRPARTNUM") "ERJ-3EKF1002V") (field (name "PUBLISHER") "Altium Limited"))
      (libsource (lib "FriedParts") (part "Res1"))
    )
    (comp (ref "R83")
      (value "0 Ohms 0")
      (footprint "SM/R_0603")
      (description "res thick film 0603 0 ohm 1/10w molded smd punched carrier")
      (fields (field (name "MFRPARTNUM") "ERJ-3GEY0R00V") (field (name "PUBLISHER") "Altium Limited"))
      (libsource (lib "FriedParts") (part "Res1"))
    )
    (comp (ref "R84")
      (value "30k Ohms 1%")
      (footprint "Resistor-3.2mm x 1.70mm")
      (description "Resistor")
      (fields (field (name "MFRPARTNUM") "ERO-S2PHF3002-2") (field (name "PUBLISHER") "Altium Limited"))
      (libsource (lib "FriedParts") (part "Res1"))
    )
    (comp (ref "R85")
      (value "1k Ohms 1%")
      (footprint "SM/C_0603")
      (description "RES 1.00K OHM 1/10W 1% 0603 SMD")
      (fields (field (name "MFRPARTNUM") "ERJ-3EKF1001V"))
      (libsource (lib "FriedParts") (part "R"))
    )
    (comp (ref "R86")
      (value "1k Ohms 1%")
      (footprint "SM/C_0603")
      (description "RES 1.00K OHM 1/10W 1% 0603 SMD")
      (fields (field (name "MFRPARTNUM") "ERJ-3EKF1001V"))
      (libsource (lib "FriedParts") (part "R"))
    )
    (comp (ref "R87")
      (value "2.7M Ohm 1%")
      (footprint "SM/R_0603")
      (description "res, thick film, 2.7mohm, 100mw, 1%; resistance:2.7mohm;")
      (fields (field (name "MFRPARTNUM") "CRCW06032M70FKEA") (field (name "PUBLISHER") "Altium Limited"))
      (libsource (lib "FriedParts") (part "Res1"))
    )
    (comp (ref "R88")
      (value "1k Ohms 1%")
      (footprint "SM/C_0603")
      (description "RES 1.00K OHM 1/10W 1% 0603 SMD")
      (fields (field (name "MFRPARTNUM") "ERJ-3EKF1001V"))
      (libsource (lib "FriedParts") (part "R"))
    )
    (comp (ref "R89")
      (value "33k Ohms 1%")
      (footprint "SM/R_0603")
      (description "resistor, rc22h 0603 33k; power rating:0.1w;")
      (fields (field (name "MFRPARTNUM") "RC0603FR-0733KL") (field (name "PUBLISHER") "Altium Limited"))
      (libsource (lib "FriedParts") (part "Res1"))
    )
    (comp (ref "R91")
      (value "49.9k Ohms 1%")
      (footprint "SM/R_0603")
      (description "res thick film 0603 49.9k ohm 1% 1/10w ±100ppm/°c molded smd")
      (fields (field (name "MFRPARTNUM") "ERJ-3EKF4992V") (field (name "PUBLISHER") "Altium Limited"))
      (libsource (lib "FriedParts") (part "Res1"))
    )
    (comp (ref "R93")
      (value "30k Ohms 1%")
      (footprint "Resistor-3.2mm x 1.70mm")
      (description "Resistor")
      (fields (field (name "MFRPARTNUM") "ERO-S2PHF3002-2") (field (name "PUBLISHER") "Altium Limited"))
      (libsource (lib "FriedParts") (part "Res1"))
    )
    (comp (ref "R94")
      (value "30k Ohms 1%")
      (footprint "Resistor-3.2mm x 1.70mm")
      (description "Resistor")
      (fields (field (name "MFRPARTNUM") "ERO-S2PHF3002-2") (field (name "PUBLISHER") "Altium Limited"))
      (libsource (lib "FriedParts") (part "Res1"))
    )
    (comp (ref "R95")
      (value "12k Ohms 1%")
      (footprint "SM/R_0603")
      (description "resistor, rc22h 0603 12k; resistance:12kohm; resistance")
      (fields (field (name "MFRPARTNUM") "RC0603FR-0712KL") (field (name "PUBLISHER") "Altium Limited"))
      (libsource (lib "FriedParts") (part "Res1"))
    )
    (comp (ref "R96")
      (value "12k Ohms 1%")
      (footprint "SM/R_0603")
      (description "resistor, rc22h 0603 12k; resistance:12kohm; resistance")
      (fields (field (name "MFRPARTNUM") "RC0603FR-0712KL") (field (name "PUBLISHER") "Altium Limited"))
      (libsource (lib "FriedParts") (part "Res1"))
    )
    (comp (ref "R97")
      (value "0 Ohms 0")
      (footprint "SM/R_0603")
      (description "res thick film 0603 0 ohm 1/10w molded smd punched carrier")
      (fields (field (name "MFRPARTNUM") "ERJ-3GEY0R00V") (field (name "PUBLISHER") "Altium Limited"))
      (libsource (lib "FriedParts") (part "Res1"))
    )
    (comp (ref "R98")
      (value "0 Ohms 0")
      (footprint "SM/R_0603")
      (description "res thick film 0603 0 ohm 1/10w molded smd punched carrier")
      (fields (field (name "MFRPARTNUM") "ERJ-3GEY0R00V") (field (name "PUBLISHER") "Altium Limited"))
      (libsource (lib "FriedParts") (part "Res1"))
    )
    (comp (ref "R99")
      (value "2.7M Ohm 1%")
      (footprint "SM/R_0603")
      (description "res, thick film, 2.7mohm, 100mw, 1%; resistance:2.7mohm;")
      (fields (field (name "MFRPARTNUM") "CRCW06032M70FKEA") (field (name "PUBLISHER") "Altium Limited"))
      (libsource (lib "FriedParts") (part "Res1"))
    )
    (comp (ref "R100")
      (value "2.7M Ohm 1%")
      (footprint "SM/R_0603")
      (description "res, thick film, 2.7mohm, 100mw, 1%; resistance:2.7mohm;")
      (fields (field (name "MFRPARTNUM") "CRCW06032M70FKEA") (field (name "PUBLISHER") "Altium Limited"))
      (libsource (lib "FriedParts") (part "Res1"))
    )
    (comp (ref "R101")
      (value "1k Ohms 1%")
      (footprint "SM/C_0603")
      (description "RES 1.00K OHM 1/10W 1% 0603 SMD")
      (fields (field (name "MFRPARTNUM") "ERJ-3EKF1001V"))
      (libsource (lib "FriedParts") (part "R"))
    )
    (comp (ref "R102")
      (value "0 Ohms 0")
      (footprint "SM/R_0603")
      (description "res thick film 0603 0 ohm 1/10w molded smd punched carrier")
      (fields (field (name "MFRPARTNUM") "ERJ-3GEY0R00V") (field (name "PUBLISHER") "Altium Limited"))
      (libsource (lib "FriedParts") (part "Res1"))
    )
    (comp (ref "R103")
      (value "50 Ohm 1%")
      (footprint "SM/R_0603")
      (description "; resistance:50ohm; resistance tolerance:± 0.1%; power")
      (fields (field (name "MFRPARTNUM") "FC0603E50R0BTBST1") (field (name "PUBLISHER") "Altium Limited"))
      (libsource (lib "FriedParts") (part "Res1"))
    )
    (comp (ref "R104")
      (value "1k Ohms 1%")
      (footprint "SM/C_0603")
      (description "RES 1.00K OHM 1/10W 1% 0603 SMD")
      (fields (field (name "MFRPARTNUM") "ERJ-3EKF1001V"))
      (libsource (lib "FriedParts") (part "R"))
    )
    (comp (ref "R105")
      (value "1k Ohms 1%")
      (footprint "SM/C_0603")
      (description "RES 1.00K OHM 1/10W 1% 0603 SMD")
      (fields (field (name "MFRPARTNUM") "ERJ-3EKF1001V"))
      (libsource (lib "FriedParts") (part "R"))
    )
    (comp (ref "R106")
      (value "50 Ohm 1%")
      (footprint "SM/R_0603")
      (description "; resistance:50ohm; resistance tolerance:± 0.1%; power")
      (fields (field (name "MFRPARTNUM") "FC0603E50R0BTBST1") (field (name "PUBLISHER") "Altium Limited"))
      (libsource (lib "FriedParts") (part "Res1"))
    )
    (comp (ref "R107")
      (value "2.7M Ohm 1%")
      (footprint "SM/R_0603")
      (description "res, thick film, 2.7mohm, 100mw, 1%; resistance:2.7mohm;")
      (fields (field (name "MFRPARTNUM") "CRCW06032M70FKEA") (field (name "PUBLISHER") "Altium Limited"))
      (libsource (lib "FriedParts") (part "Res1"))
    )
    (comp (ref "R108")
      (value "2.7M Ohm 1%")
      (footprint "SM/R_0603")
      (description "res, thick film, 2.7mohm, 100mw, 1%; resistance:2.7mohm;")
      (fields (field (name "MFRPARTNUM") "CRCW06032M70FKEA") (field (name "PUBLISHER") "Altium Limited"))
      (libsource (lib "FriedParts") (part "Res1"))
    )
    (comp (ref "R109")
      (value "0 Ohms 0")
      (footprint "SM/R_0603")
      (description "res thick film 0603 0 ohm 1/10w molded smd punched carrier")
      (fields (field (name "MFRPARTNUM") "ERJ-3GEY0R00V") (field (name "PUBLISHER") "Altium Limited"))
      (libsource (lib "FriedParts") (part "Res1"))
    )
    (comp (ref "R110")
      (value "10k ohm 1%")
      (footprint "SM/C_0603")
      (description "resistor, 0603, 0.1w, 1%, 10k; resistance:10kohm; resistance")
      (fields (field (name "MFRPARTNUM") "ERJ-3EKF1002V") (field (name "PUBLISHER") "Altium Limited"))
      (libsource (lib "FriedParts") (part "Res1"))
    )
    (comp (ref "R111")
      (value "1k Ohms 1%")
      (footprint "SM/C_0603")
      (description "RES 1.00K OHM 1/10W 1% 0603 SMD")
      (fields (field (name "MFRPARTNUM") "ERJ-3EKF1001V"))
      (libsource (lib "FriedParts") (part "R"))
    )
    (comp (ref "R112")
      (value "1k Ohms 1%")
      (footprint "SM/C_0603")
      (description "RES 1.00K OHM 1/10W 1% 0603 SMD")
      (fields (field (name "MFRPARTNUM") "ERJ-3EKF1001V"))
      (libsource (lib "FriedParts") (part "R"))
    )
    (comp (ref "R113")
      (value "1k Ohms 1%")
      (footprint "SM/C_0603")
      (description "RES 1.00K OHM 1/10W 1% 0603 SMD")
      (fields (field (name "MFRPARTNUM") "ERJ-3EKF1001V"))
      (libsource (lib "FriedParts") (part "R"))
    )
    (comp (ref "R114")
      (value "50 Ohm 1%")
      (footprint "SM/R_0603")
      (description "; resistance:50ohm; resistance tolerance:± 0.1%; power")
      (fields (field (name "MFRPARTNUM") "FC0603E50R0BTBST1") (field (name "PUBLISHER") "Altium Limited"))
      (libsource (lib "FriedParts") (part "Res1"))
    )
    (comp (ref "R115")
      (value "1k Ohms 1%")
      (footprint "SM/C_0603")
      (description "RES 1.00K OHM 1/10W 1% 0603 SMD")
      (fields (field (name "MFRPARTNUM") "ERJ-3EKF1001V"))
      (libsource (lib "FriedParts") (part "R"))
    )
    (comp (ref "R116")
      (value "1k Ohms 1%")
      (footprint "SM/C_0603")
      (description "RES 1.00K OHM 1/10W 1% 0603 SMD")
      (fields (field (name "MFRPARTNUM") "ERJ-3EKF1001V"))
      (libsource (lib "FriedParts") (part "R"))
    )
    (comp (ref "R117")
      (value "50 Ohm 1%")
      (footprint "SM/R_0603")
      (description "; resistance:50ohm; resistance tolerance:± 0.1%; power")
      (fields (field (name "MFRPARTNUM") "FC0603E50R0BTBST1") (field (name "PUBLISHER") "Altium Limited"))
      (libsource (lib "FriedParts") (part "Res1"))
    )
    (comp (ref "R118")
      (value "1k Ohms 1%")
      (footprint "SM/C_0603")
      (description "RES 1.00K OHM 1/10W 1% 0603 SMD")
      (fields (field (name "MFRPARTNUM") "ERJ-3EKF1001V"))
      (libsource (lib "FriedParts") (part "R"))
    )
    (comp (ref "R119")
      (value "33k Ohms 1%")
      (footprint "SM/R_0603")
      (description "resistor, rc22h 0603 33k; power rating:0.1w;")
      (fields (field (name "MFRPARTNUM") "RC0603FR-0733KL") (field (name "PUBLISHER") "Altium Limited"))
      (libsource (lib "FriedParts") (part "Res1"))
    )
    (comp (ref "R120")
      (value "0 Ohms 0")
      (footprint "SM/R_0603")
      (description "res thick film 0603 0 ohm 1/10w molded smd punched carrier")
      (fields (field (name "MFRPARTNUM") "ERJ-3GEY0R00V") (field (name "PUBLISHER") "Altium Limited"))
      (libsource (lib "FriedParts") (part "Res1"))
    )
    (comp (ref "R121")
      (value "0 Ohms 0")
      (footprint "SM/R_0603")
      (description "res thick film 0603 0 ohm 1/10w molded smd punched carrier")
      (fields (field (name "MFRPARTNUM") "ERJ-3GEY0R00V") (field (name "PUBLISHER") "Altium Limited"))
      (libsource (lib "FriedParts") (part "Res1"))
    )
    (comp (ref "R122")
      (value "0 Ohms 0")
      (footprint "SM/R_0603")
      (description "res thick film 0603 0 ohm 1/10w molded smd punched carrier")
      (fields (field (name "MFRPARTNUM") "ERJ-3GEY0R00V") (field (name "PUBLISHER") "Altium Limited"))
      (libsource (lib "FriedParts") (part "Res1"))
    )
    (comp (ref "R123")
      (value "0 Ohms 0")
      (footprint "SM/R_0603")
      (description "res thick film 0603 0 ohm 1/10w molded smd punched carrier")
      (fields (field (name "MFRPARTNUM") "ERJ-3GEY0R00V") (field (name "PUBLISHER") "Altium Limited"))
      (libsource (lib "FriedParts") (part "Res1"))
    )
    (comp (ref "R124")
      (value "0 Ohms 0")
      (footprint "SM/R_0603")
      (description "res thick film 0603 0 ohm 1/10w molded smd punched carrier")
      (fields (field (name "MFRPARTNUM") "ERJ-3GEY0R00V") (field (name "PUBLISHER") "Altium Limited"))
      (libsource (lib "FriedParts") (part "Res1"))
    )
    (comp (ref "R125")
      (value "0 Ohms 0")
      (footprint "SM/R_0603")
      (description "res thick film 0603 0 ohm 1/10w molded smd punched carrier")
      (fields (field (name "MFRPARTNUM") "ERJ-3GEY0R00V") (field (name "PUBLISHER") "Altium Limited"))
      (libsource (lib "FriedParts") (part "Res1"))
    )
    (comp (ref "R126")
      (value "1k Ohms 1%")
      (footprint "SM/C_0603")
      (description "RES 1.00K OHM 1/10W 1% 0603 SMD")
      (fields (field (name "MFRPARTNUM") "ERJ-3EKF1001V"))
      (libsource (lib "FriedParts") (part "R"))
    )
    (comp (ref "R127")
      (value "1k Ohms 1%")
      (footprint "SM/C_0603")
      (description "RES 1.00K OHM 1/10W 1% 0603 SMD")
      (fields (field (name "MFRPARTNUM") "ERJ-3EKF1001V"))
      (libsource (lib "FriedParts") (part "R"))
    )
    (comp (ref "R128")
      (value "1k Ohms 1%")
      (footprint "SM/C_0603")
      (description "RES 1.00K OHM 1/10W 1% 0603 SMD")
      (fields (field (name "MFRPARTNUM") "ERJ-3EKF1001V"))
      (libsource (lib "FriedParts") (part "R"))
    )
    (comp (ref "R129")
      (value "1k Ohms 1%")
      (footprint "SM/C_0603")
      (description "RES 1.00K OHM 1/10W 1% 0603 SMD")
      (fields (field (name "MFRPARTNUM") "ERJ-3EKF1001V"))
      (libsource (lib "FriedParts") (part "R"))
    )
    (comp (ref "R130")
      (value "33k Ohms 1%")
      (footprint "SM/R_0603")
      (description "resistor, rc22h 0603 33k; power rating:0.1w;")
      (fields (field (name "MFRPARTNUM") "RC0603FR-0733KL") (field (name "PUBLISHER") "Altium Limited"))
      (libsource (lib "FriedParts") (part "Res1"))
    )
    (comp (ref "R131")
      (value "10k ohm 1%")
      (footprint "SM/C_0603")
      (description "resistor, 0603, 0.1w, 1%, 10k; resistance:10kohm; resistance")
      (fields (field (name "MFRPARTNUM") "ERJ-3EKF1002V") (field (name "PUBLISHER") "Altium Limited"))
      (libsource (lib "FriedParts") (part "Res1"))
    )
    (comp (ref "R132")
      (value "49.9k Ohms 1%")
      (footprint "SM/R_0603")
      (description "res thick film 0603 49.9k ohm 1% 1/10w ±100ppm/°c molded smd")
      (fields (field (name "MFRPARTNUM") "ERJ-3EKF4992V") (field (name "PUBLISHER") "Altium Limited"))
      (libsource (lib "FriedParts") (part "Res1"))
    )
    (comp (ref "R133")
      (value "49.9k Ohms 1%")
      (footprint "SM/R_0603")
      (description "res thick film 0603 49.9k ohm 1% 1/10w ±100ppm/°c molded smd")
      (fields (field (name "MFRPARTNUM") "ERJ-3EKF4992V") (field (name "PUBLISHER") "Altium Limited"))
      (libsource (lib "FriedParts") (part "Res1"))
    )
    (comp (ref "R134")
      (value "12k Ohms 1%")
      (footprint "SM/R_0603")
      (description "resistor, rc22h 0603 12k; resistance:12kohm; resistance")
      (fields (field (name "MFRPARTNUM") "RC0603FR-0712KL") (field (name "PUBLISHER") "Altium Limited"))
      (libsource (lib "FriedParts") (part "Res1"))
    )
    (comp (ref "R135")
      (value "12k Ohms 1%")
      (footprint "SM/R_0603")
      (description "resistor, rc22h 0603 12k; resistance:12kohm; resistance")
      (fields (field (name "MFRPARTNUM") "RC0603FR-0712KL") (field (name "PUBLISHER") "Altium Limited"))
      (libsource (lib "FriedParts") (part "Res1"))
    )
    (comp (ref "R136")
      (value "12k Ohms 1%")
      (footprint "SM/R_0603")
      (description "resistor, rc22h 0603 12k; resistance:12kohm; resistance")
      (fields (field (name "MFRPARTNUM") "RC0603FR-0712KL") (field (name "PUBLISHER") "Altium Limited"))
      (libsource (lib "FriedParts") (part "Res1"))
    )
    (comp (ref "R137")
      (value "12k Ohms 1%")
      (footprint "SM/R_0603")
      (description "resistor, rc22h 0603 12k; resistance:12kohm; resistance")
      (fields (field (name "MFRPARTNUM") "RC0603FR-0712KL") (field (name "PUBLISHER") "Altium Limited"))
      (libsource (lib "FriedParts") (part "Res1"))
    )
    (comp (ref "R138")
      (value "10k ohm 1%")
      (footprint "SM/C_0603")
      (description "resistor, 0603, 0.1w, 1%, 10k; resistance:10kohm; resistance")
      (fields (field (name "MFRPARTNUM") "ERJ-3EKF1002V") (field (name "PUBLISHER") "Altium Limited"))
      (libsource (lib "FriedParts") (part "Res1"))
    )
    (comp (ref "R139")
      (value "33k Ohms 1%")
      (footprint "SM/R_0603")
      (description "resistor, rc22h 0603 33k; power rating:0.1w;")
      (fields (field (name "MFRPARTNUM") "RC0603FR-0733KL") (field (name "PUBLISHER") "Altium Limited"))
      (libsource (lib "FriedParts") (part "Res1"))
    )
    (comp (ref "R140")
      (value "49.9k Ohms 1%")
      (footprint "SM/R_0603")
      (description "res thick film 0603 49.9k ohm 1% 1/10w ±100ppm/°c molded smd")
      (fields (field (name "MFRPARTNUM") "ERJ-3EKF4992V") (field (name "PUBLISHER") "Altium Limited"))
      (libsource (lib "FriedParts") (part "Res1"))
    )
    (comp (ref "R141")
      (value "12k Ohms 1%")
      (footprint "SM/R_0603")
      (description "resistor, rc22h 0603 12k; resistance:12kohm; resistance")
      (fields (field (name "MFRPARTNUM") "RC0603FR-0712KL") (field (name "PUBLISHER") "Altium Limited"))
      (libsource (lib "FriedParts") (part "Res1"))
    )
    (comp (ref "R142")
      (value "12k Ohms 1%")
      (footprint "SM/R_0603")
      (description "resistor, rc22h 0603 12k; resistance:12kohm; resistance")
      (fields (field (name "MFRPARTNUM") "RC0603FR-0712KL") (field (name "PUBLISHER") "Altium Limited"))
      (libsource (lib "FriedParts") (part "Res1"))
    )
    (comp (ref "R144")
      (value "330 Ohms 1%")
      (footprint "SM/C_0603")
      (description "RES 330 OHM 1/10W 1% 0603 SMD")
      (fields (field (name "MFRPARTNUM") "ERJ-3EKF3300V"))
      (libsource (lib "FriedParts") (part "R"))
    )
    (comp (ref "R145")
      (value "330 Ohms 1%")
      (footprint "SM/C_0603")
      (description "RES 330 OHM 1/10W 1% 0603 SMD")
      (fields (field (name "MFRPARTNUM") "ERJ-3EKF3300V"))
      (libsource (lib "FriedParts") (part "R"))
    )
    (comp (ref "R146")
      (value "330 Ohms 1%")
      (footprint "SM/C_0603")
      (description "RES 330 OHM 1/10W 1% 0603 SMD")
      (fields (field (name "MFRPARTNUM") "ERJ-3EKF3300V"))
      (libsource (lib "FriedParts") (part "R"))
    )
    (comp (ref "RESET")
      (value "CKN9104CT-ND")
      (footprint "MOM-SW")
      (description "SW - SPST-NO - SM")
      (libsource (lib "FriedParts") (part "MOM-BUT"))
    )
    (comp (ref "TP-5V")
      (value "5016")
      (footprint "TEST_PT_SMD")
      (description "test point, connector; connector type:test; mounting type:pc")
      (libsource (lib "FriedParts") (part "TEST_PT"))
    )
    (comp (ref "TP1")
      (value "5016")
      (footprint "TEST_PT_SMD")
      (description "test point, connector; connector type:test; mounting type:pc")
      (libsource (lib "FriedParts") (part "TEST_PT"))
    )
    (comp (ref "TP2")
      (value "5016")
      (footprint "TEST_PT_SMD")
      (description "test point, connector; connector type:test; mounting type:pc")
      (libsource (lib "FriedParts") (part "TEST_PT"))
    )
    (comp (ref "TP2V5")
      (value "5016")
      (footprint "TEST_PT_SMD")
      (description "test point, connector; connector type:test; mounting type:pc")
      (libsource (lib "FriedParts") (part "TEST_PT"))
    )
    (comp (ref "TP3")
      (value "5016")
      (footprint "TEST_PT_SMD")
      (description "test point, connector; connector type:test; mounting type:pc")
      (libsource (lib "FriedParts") (part "TEST_PT"))
    )
    (comp (ref "TP4")
      (value "5016")
      (footprint "TEST_PT_SMD")
      (description "test point, connector; connector type:test; mounting type:pc")
      (libsource (lib "FriedParts") (part "TEST_PT"))
    )
    (comp (ref "TP5")
      (value "5016")
      (footprint "TEST_PT_SMD")
      (description "test point, connector; connector type:test; mounting type:pc")
      (libsource (lib "FriedParts") (part "TEST_PT"))
    )
    (comp (ref "TP5V")
      (value "5016")
      (footprint "TEST_PT_SMD")
      (description "test point, connector; connector type:test; mounting type:pc")
      (libsource (lib "FriedParts") (part "TEST_PT"))
    )
    (comp (ref "TP6")
      (value "5016")
      (footprint "TEST_PT_SMD")
      (description "test point, connector; connector type:test; mounting type:pc")
      (libsource (lib "FriedParts") (part "TEST_PT"))
    )
    (comp (ref "TP7")
      (value "5016")
      (footprint "TEST_PT_SMD")
      (description "test point, connector; connector type:test; mounting type:pc")
      (libsource (lib "FriedParts") (part "TEST_PT"))
    )
    (comp (ref "TP8")
      (value "5016")
      (footprint "TEST_PT_SMD")
      (description "test point, connector; connector type:test; mounting type:pc")
      (libsource (lib "FriedParts") (part "TEST_PT"))
    )
    (comp (ref "TP9")
      (value "5016")
      (footprint "TEST_PT_SMD")
      (description "test point, connector; connector type:test; mounting type:pc")
      (libsource (lib "FriedParts") (part "TEST_PT"))
    )
    (comp (ref "TP10")
      (value "5016")
      (footprint "TEST_PT_SMD")
      (description "test point, connector; connector type:test; mounting type:pc")
      (libsource (lib "FriedParts") (part "TEST_PT"))
    )
    (comp (ref "TP11")
      (value "5016")
      (footprint "TEST_PT_SMD")
      (description "test point, connector; connector type:test; mounting type:pc")
      (libsource (lib "FriedParts") (part "TEST_PT"))
    )
    (comp (ref "TP12")
      (value "5016")
      (footprint "TEST_PT_SMD")
      (description "test point, connector; connector type:test; mounting type:pc")
      (libsource (lib "FriedParts") (part "TEST_PT"))
    )
    (comp (ref "TP13")
      (value "5016")
      (footprint "TEST_PT_SMD")
      (description "test point, connector; connector type:test; mounting type:pc")
      (libsource (lib "FriedParts") (part "TEST_PT"))
    )
    (comp (ref "TP14")
      (value "5016")
      (footprint "TEST_PT_SMD")
      (description "test point, connector; connector type:test; mounting type:pc")
      (libsource (lib "FriedParts") (part "TEST_PT"))
    )
    (comp (ref "TP15")
      (value "5016")
      (footprint "TEST_PT_SMD")
      (description "test point, connector; connector type:test; mounting type:pc")
      (libsource (lib "FriedParts") (part "TEST_PT"))
    )
    (comp (ref "TP16")
      (value "5016")
      (footprint "TEST_PT_SMD")
      (description "test point, connector; connector type:test; mounting type:pc")
      (libsource (lib "FriedParts") (part "TEST_PT"))
    )
    (comp (ref "TP17")
      (value "5016")
      (footprint "TEST_PT_SMD")
      (description "test point, connector; connector type:test; mounting type:pc")
      (libsource (lib "FriedParts") (part "TEST_PT"))
    )
    (comp (ref "TP18")
      (value "5016")
      (footprint "TEST_PT_SMD")
      (description "test point, connector; connector type:test; mounting type:pc")
      (libsource (lib "FriedParts") (part "TEST_PT"))
    )
    (comp (ref "TP19")
      (value "5016")
      (footprint "TEST_PT_SMD")
      (description "test point, connector; connector type:test; mounting type:pc")
      (libsource (lib "FriedParts") (part "TEST_PT"))
    )
    (comp (ref "TP20")
      (value "5016")
      (footprint "TEST_PT_SMD")
      (description "test point, connector; connector type:test; mounting type:pc")
      (libsource (lib "FriedParts") (part "TEST_PT"))
    )
    (comp (ref "TP21")
      (value "5016")
      (footprint "TEST_PT_SMD")
      (description "test point, connector; connector type:test; mounting type:pc")
      (libsource (lib "FriedParts") (part "TEST_PT"))
    )
    (comp (ref "TP22")
      (value "5016")
      (footprint "TEST_PT_SMD")
      (description "test point, connector; connector type:test; mounting type:pc")
      (libsource (lib "FriedParts") (part "TEST_PT"))
    )
    (comp (ref "TP23")
      (value "5016")
      (footprint "TEST_PT_SMD")
      (description "test point, connector; connector type:test; mounting type:pc")
      (libsource (lib "FriedParts") (part "TEST_PT"))
    )
    (comp (ref "TP24")
      (value "5016")
      (footprint "TEST_PT_SMD")
      (description "test point, connector; connector type:test; mounting type:pc")
      (libsource (lib "FriedParts") (part "TEST_PT"))
    )
    (comp (ref "TP25")
      (value "5016")
      (footprint "TEST_PT_SMD")
      (description "test point, connector; connector type:test; mounting type:pc")
      (libsource (lib "FriedParts") (part "TEST_PT"))
    )
    (comp (ref "TP26")
      (value "5016")
      (footprint "TEST_PT_SMD")
      (description "test point, connector; connector type:test; mounting type:pc")
      (libsource (lib "FriedParts") (part "TEST_PT"))
    )
    (comp (ref "TP27")
      (value "5016")
      (footprint "TEST_PT_SMD")
      (description "test point, connector; connector type:test; mounting type:pc")
      (libsource (lib "FriedParts") (part "TEST_PT"))
    )
    (comp (ref "TP34")
      (value "5016")
      (footprint "TEST_PT_SMD")
      (description "test point, connector; connector type:test; mounting type:pc")
      (libsource (lib "FriedParts") (part "TEST_PT"))
    )
    (comp (ref "TPSCL")
      (value "5016")
      (footprint "TEST_PT_SMD")
      (description "test point, connector; connector type:test; mounting type:pc")
      (libsource (lib "FriedParts") (part "TEST_PT"))
    )
    (comp (ref "TPSDA")
      (value "5016")
      (footprint "TEST_PT_SMD")
      (description "test point, connector; connector type:test; mounting type:pc")
      (libsource (lib "FriedParts") (part "TEST_PT"))
    )
    (comp (ref "TP_-2V5")
      (value "5016")
      (footprint "TEST_PT_SMD")
      (description "test point, connector; connector type:test; mounting type:pc")
      (libsource (lib "FriedParts") (part "TEST_PT"))
    )
    (comp (ref "TP_CS0")
      (value "5016")
      (footprint "TEST_PT_SMD")
      (description "test point, connector; connector type:test; mounting type:pc")
      (libsource (lib "FriedParts") (part "TEST_PT"))
    )
    (comp (ref "TP_CS1")
      (value "5016")
      (footprint "TEST_PT_SMD")
      (description "test point, connector; connector type:test; mounting type:pc")
      (libsource (lib "FriedParts") (part "TEST_PT"))
    )
    (comp (ref "TP_CS2")
      (value "5016")
      (footprint "TEST_PT_SMD")
      (description "test point, connector; connector type:test; mounting type:pc")
      (libsource (lib "FriedParts") (part "TEST_PT"))
    )
    (comp (ref "TP_CS3")
      (value "5016")
      (footprint "TEST_PT_SMD")
      (description "test point, connector; connector type:test; mounting type:pc")
      (libsource (lib "FriedParts") (part "TEST_PT"))
    )
    (comp (ref "TP_F0")
      (value "5016")
      (footprint "TEST_PT_SMD")
      (description "test point, connector; connector type:test; mounting type:pc")
      (libsource (lib "FriedParts") (part "TEST_PT"))
    )
    (comp (ref "TP_F1")
      (value "5016")
      (footprint "TEST_PT_SMD")
      (description "test point, connector; connector type:test; mounting type:pc")
      (libsource (lib "FriedParts") (part "TEST_PT"))
    )
    (comp (ref "TP_F2")
      (value "5016")
      (footprint "TEST_PT_SMD")
      (description "test point, connector; connector type:test; mounting type:pc")
      (libsource (lib "FriedParts") (part "TEST_PT"))
    )
    (comp (ref "TP_F3")
      (value "5016")
      (footprint "TEST_PT_SMD")
      (description "test point, connector; connector type:test; mounting type:pc")
      (libsource (lib "FriedParts") (part "TEST_PT"))
    )
    (comp (ref "TP_F4")
      (value "5016")
      (footprint "TEST_PT_SMD")
      (description "test point, connector; connector type:test; mounting type:pc")
      (libsource (lib "FriedParts") (part "TEST_PT"))
    )
    (comp (ref "TP_F5")
      (value "5016")
      (footprint "TEST_PT_SMD")
      (description "test point, connector; connector type:test; mounting type:pc")
      (libsource (lib "FriedParts") (part "TEST_PT"))
    )
    (comp (ref "TP_F6")
      (value "5016")
      (footprint "TEST_PT_SMD")
      (description "test point, connector; connector type:test; mounting type:pc")
      (libsource (lib "FriedParts") (part "TEST_PT"))
    )
    (comp (ref "TP_F7")
      (value "5016")
      (footprint "TEST_PT_SMD")
      (description "test point, connector; connector type:test; mounting type:pc")
      (libsource (lib "FriedParts") (part "TEST_PT"))
    )
    (comp (ref "TP_GND")
      (value "5016")
      (footprint "TEST_PT_SMD")
      (description "test point, connector; connector type:test; mounting type:pc")
      (libsource (lib "FriedParts") (part "TEST_PT"))
    )
    (comp (ref "TP_GND2")
      (value "5016")
      (footprint "TEST_PT_SMD")
      (description "test point, connector; connector type:test; mounting type:pc")
      (libsource (lib "FriedParts") (part "TEST_PT"))
    )
    (comp (ref "TP_MISO")
      (value "5016")
      (footprint "TEST_PT_SMD")
      (description "test point, connector; connector type:test; mounting type:pc")
      (libsource (lib "FriedParts") (part "TEST_PT"))
    )
    (comp (ref "TP_MOSI")
      (value "5016")
      (footprint "TEST_PT_SMD")
      (description "test point, connector; connector type:test; mounting type:pc")
      (libsource (lib "FriedParts") (part "TEST_PT"))
    )
    (comp (ref "TP_SCK")
      (value "5016")
      (footprint "TEST_PT_SMD")
      (description "test point, connector; connector type:test; mounting type:pc")
      (libsource (lib "FriedParts") (part "TEST_PT"))
    )
    (comp (ref "TVS1")
      (value "SMAJ12CA-TP")
      (footprint "D0-214AC")
      (description "TVS 400W 12V BIDIRECT SMA")
      (libsource (lib "FriedParts") (part "SMAJ12CA-TPMC"))
    )
    (comp (ref "TVS2")
      (value "SMAJ12CA-TP")
      (footprint "D0-214AC")
      (description "TVS 400W 12V BIDIRECT SMA")
      (libsource (lib "FriedParts") (part "SMAJ12CA-TPMC"))
    )
    (comp (ref "TVS3")
      (value "SMAJ12CA-TP")
      (footprint "D0-214AC")
      (description "TVS 400W 12V BIDIRECT SMA")
      (libsource (lib "FriedParts") (part "SMAJ12CA-TPMC"))
    )
    (comp (ref "TVS4")
      (value "SMAJ12CA-TP")
      (footprint "D0-214AC")
      (description "TVS 400W 12V BIDIRECT SMA")
      (libsource (lib "FriedParts") (part "SMAJ12CA-TPMC"))
    )
    (comp (ref "U1")
      (value "LTC6254CMS#PBF-ND")
      (footprint "MSOP-16Lead-LTC6254")
      (description "op amp, dual, r-r, 180mhz, 8msop; op amp type:unity gain")
      (libsource (lib "FriedParts") (part "LTC6254"))
    )
    (comp (ref "U2")
      (value "LTC6252")
      (footprint "TSOT-23-LTC6252-OpAmp")
      (description "op amp, r/r 200mhz single, soic8; no. of amplifiers:1; op amp")
      (libsource (lib "FriedParts") (part "LTC6252"))
    )
    (comp (ref "U3")
      (value "LTC6254CMS#PBF-ND")
      (footprint "MSOP-16Lead-LTC6254")
      (description "op amp, dual, r-r, 180mhz, 8msop; op amp type:unity gain")
      (libsource (lib "FriedParts") (part "LTC6254"))
    )
    (comp (ref "U4")
      (value "ADG636YRUZ")
      (footprint "TSSOP-14Lead-AnalogDevices-ADG636")
      (description "switch, spdt dual, tssop14, 636; switch type, analogue:spdt;")
      (libsource (lib "FriedParts") (part "ADG636"))
    )
    (comp (ref "U5")
      (value "LTC6252")
      (footprint "TSOT-23-LTC6252-OpAmp")
      (description "op amp, r/r 200mhz single, soic8; no. of amplifiers:1; op amp")
      (libsource (lib "FriedParts") (part "LTC6252"))
    )
    (comp (ref "U6")
      (value "ATMEGA32U4-AU")
      (footprint "TQFP80P1200X1200X120-44L")
      (description "mcu, 8bit, avr, 32k flash, usb, 44tqfp; eeprom memory")
      (libsource (lib "FriedParts") (part "ATMega32U4"))
    )
    (comp (ref "U7")
      (value "LTC6254CMS#PBF-ND")
      (footprint "MSOP-16Lead-LTC6254")
      (description "op amp, dual, r-r, 180mhz, 8msop; op amp type:unity gain")
      (libsource (lib "FriedParts") (part "LTC6254"))
    )
    (comp (ref "U10")
      (value "LTC6254CMS#PBF-ND")
      (footprint "MSOP-16Lead-LTC6254")
      (description "op amp, dual, r-r, 180mhz, 8msop; op amp type:unity gain")
      (libsource (lib "FriedParts") (part "LTC6254"))
    )
    (comp (ref "U11")
      (value "LTC6252")
      (footprint "TSOT-23-LTC6252-OpAmp")
      (description "op amp, r/r 200mhz single, soic8; no. of amplifiers:1; op amp")
      (libsource (lib "FriedParts") (part "LTC6252"))
    )
    (comp (ref "U12")
      (value "LMP8100-ProgrammableGainAmp")
      (footprint "SOIC-14pin-National-Semiconductor")
      (libsource (lib "FriedParts") (part "LMP8100-ProgrammableGainAmp"))
    )
    (comp (ref "U13")
      (value "LTC6254CMS#PBF-ND")
      (footprint "MSOP-16Lead-LTC6254")
      (description "op amp, dual, r-r, 180mhz, 8msop; op amp type:unity gain")
      (libsource (lib "FriedParts") (part "LTC6254"))
    )
    (comp (ref "U14")
      (value "ADG636YRUZ")
      (footprint "TSSOP-14Lead-AnalogDevices-ADG636")
      (description "switch, spdt dual, tssop14, 636; switch type, analogue:spdt;")
      (libsource (lib "FriedParts") (part "ADG636"))
    )
    (comp (ref "U15")
      (value "LMP8100-ProgrammableGainAmp")
      (footprint "SOIC-14pin-National-Semiconductor")
      (libsource (lib "FriedParts") (part "LMP8100-ProgrammableGainAmp"))
    )
    (comp (ref "U16")
      (value "LTC6252")
      (footprint "TSOT-23-LTC6252-OpAmp")
      (description "op amp, r/r 200mhz single, soic8; no. of amplifiers:1; op amp")
      (libsource (lib "FriedParts") (part "LTC6252"))
    )
    (comp (ref "U17")
      (value "LMP8100-ProgrammableGainAmp")
      (footprint "SOIC-14pin-National-Semiconductor")
      (libsource (lib "FriedParts") (part "LMP8100-ProgrammableGainAmp"))
    )
    (comp (ref "U18")
      (value "LMP8100-ProgrammableGainAmp")
      (footprint "SOIC-14pin-National-Semiconductor")
      (libsource (lib "FriedParts") (part "LMP8100-ProgrammableGainAmp"))
    )
    (comp (ref "U19")
      (value "ADG636YRUZ")
      (footprint "TSSOP-14Lead-AnalogDevices-ADG636")
      (description "switch, spdt dual, tssop14, 636; switch type, analogue:spdt;")
      (libsource (lib "FriedParts") (part "ADG636"))
    )
    (comp (ref "U20")
      (value "MAX3002EUP+")
      (footprint "TSSOP-20Lead-MAXIM")
      (description "translator, 8 ch, 15kv esd, 3002; no. of inputs:8; output")
      (libsource (lib "FriedParts") (part "MAX3002"))
    )
    (comp (ref "U21")
      (value "ADG636YRUZ")
      (footprint "TSSOP-14Lead-AnalogDevices-ADG636")
      (description "switch, spdt dual, tssop14, 636; switch type, analogue:spdt;")
      (libsource (lib "FriedParts") (part "ADG636"))
    )
    (comp (ref "U22")
      (value "DF206ST-G")
      (footprint "vikram:BridgeRectifier-DFS")
      (description "schottky diode; operating temperature range:0°c to +70°c;")
      (libsource (lib "FriedParts") (part "Bridge_Rectifier"))
    )
    (comp (ref "U23")
      (value "LTC6254CMS#PBF-ND")
      (footprint "MSOP-16Lead-LTC6254")
      (description "op amp, dual, r-r, 180mhz, 8msop; op amp type:unity gain")
      (libsource (lib "FriedParts") (part "LTC6254"))
    )
    (comp (ref "VR1")
      (value "LM317EMP/NOPB")
      (footprint "LM317-SOT233-POS-ADJ-VOLT_REG")
      (description "v reg, linear, 37v, smd; voltage regulator type:adjustable")
      (libsource (lib "") (part "ADJ_VOLT_REG_1"))
    )
    (comp (ref "VR2")
      (value "LM317EMP/NOPB")
      (footprint "LM317-SOT233-POS-ADJ-VOLT_REG")
      (description "v reg, linear, 37v, smd; voltage regulator type:adjustable")
      (libsource (lib "") (part "ADJ_VOLT_REG_1"))
    )
    (comp (ref "VR3")
      (value "LM337IMP/NOPB")
      (footprint "LM337-ADJ-NEG-VOLT-REG")
      (description "linear voltage regulator ic; output voltage adjustable")
      (libsource (lib "FriedParts") (part "ADJ_VOLT_REG"))
    )
    (comp (ref "VR4")
      (value "LM337IMP/NOPB")
      (footprint "LM337-ADJ-NEG-VOLT-REG")
      (description "linear voltage regulator ic; output voltage adjustable")
      (libsource (lib "FriedParts") (part "ADJ_VOLT_REG"))
    )
    (comp (ref "X1")
      (value "16M Hz ±30ppm")
      (footprint "XTAL 16MHz SMD")
      (description "crystal 16.0000 mhz 18.0pf smd")
      (fields (field (name "MFRPARTNUM") "FA-238 16.0000MB-C3"))
      (libsource (lib "FriedParts") (part "XTAL-FA238V"))
    )
    (comp (ref "XFR1")
      (value "PL30-12-130B")
      (footprint "TRANSFORMER-DUAL-PRIMARY")
      (description "transformers 12.6vct @ 2.40a 6.3v @ 4.80a")
      (libsource (lib "FriedParts") (part "PowerTransformer-DualIput-Tamura-PL30-12-130B"))
    )
  )
  (nets
    (net (code "12") (name "+2.5V") (class "Default")
      (node (ref "C121") (pin "1") (pinfunction "1_1") (pintype "passive"))
      (node (ref "C16") (pin "1") (pinfunction "1_1") (pintype "passive"))
      (node (ref "C29") (pin "1") (pinfunction "1_1") (pintype "passive"))
      (node (ref "C4") (pin "1") (pinfunction "1_1") (pintype "passive"))
      (node (ref "C44") (pin "1") (pinfunction "1_1") (pintype "passive"))
      (node (ref "C51") (pin "2") (pinfunction "2_2") (pintype "passive"))
      (node (ref "C58") (pin "1") (pinfunction "1_1") (pintype "passive"))
      (node (ref "C6") (pin "1") (pinfunction "1_1") (pintype "passive"))
      (node (ref "C62") (pin "1") (pinfunction "1_1") (pintype "passive"))
      (node (ref "C75") (pin "1") (pinfunction "1_1") (pintype "passive"))
      (node (ref "C77") (pin "1") (pinfunction "1_1") (pintype "passive"))
      (node (ref "C79") (pin "2") (pinfunction "2_2") (pintype "passive"))
      (node (ref "C81") (pin "2") (pinfunction "2_2") (pintype "passive"))
      (node (ref "C82") (pin "2") (pinfunction "2_2") (pintype "passive"))
      (node (ref "C88") (pin "2") (pinfunction "2_2") (pintype "passive"))
      (node (ref "C91") (pin "2") (pinfunction "2_2") (pintype "passive"))
      (node (ref "R110") (pin "2") (pinfunction "2_2") (pintype "passive"))
      (node (ref "R13") (pin "1") (pinfunction "1_1") (pintype "passive"))
      (node (ref "R44") (pin "2") (pinfunction "2_2") (pintype "passive"))
      (node (ref "R5") (pin "2") (pinfunction "2_2") (pintype "passive"))
      (node (ref "R7") (pin "2") (pinfunction "2_2") (pintype "passive"))
      (node (ref "R82") (pin "2") (pinfunction "2_2") (pintype "passive"))
      (node (ref "TP2V5") (pin "1") (pinfunction "TP?_1") (pintype "passive"))
      (node (ref "U1") (pin "4") (pinfunction "V+_4") (pintype "passive"))
      (node (ref "U10") (pin "4") (pinfunction "V+_4") (pintype "passive"))
      (node (ref "U11") (pin "6") (pinfunction "V+_6") (pintype "passive"))
      (node (ref "U12") (pin "8") (pinfunction "V+_8") (pintype "passive"))
      (node (ref "U13") (pin "4") (pinfunction "V+_4") (pintype "passive"))
      (node (ref "U15") (pin "8") (pinfunction "V+_8") (pintype "passive"))
      (node (ref "U16") (pin "6") (pinfunction "V+_6") (pintype "passive"))
      (node (ref "U17") (pin "8") (pinfunction "V+_8") (pintype "passive"))
      (node (ref "U18") (pin "8") (pinfunction "V+_8") (pintype "passive"))
      (node (ref "U2") (pin "6") (pinfunction "V+_6") (pintype "passive"))
      (node (ref "U20") (pin "10") (pinfunction "EN_10") (pintype "passive"))
      (node (ref "U20") (pin "2") (pinfunction "VL_2") (pintype "passive"))
      (node (ref "U23") (pin "4") (pinfunction "V+_4") (pintype "passive"))
      (node (ref "U3") (pin "4") (pinfunction "V+_4") (pintype "passive"))
      (node (ref "U5") (pin "6") (pinfunction "V+_6") (pintype "passive"))
      (node (ref "U7") (pin "4") (pinfunction "V+_4") (pintype "passive"))
      (node (ref "VR2") (pin "3") (pinfunction "VOUT_3") (pintype "passive"))
    )
    (net (code "13") (name "+5V") (class "Default")
      (node (ref "C103") (pin "1") (pinfunction "1_1") (pintype "passive"))
      (node (ref "C120") (pin "1") (pinfunction "1_1") (pintype "passive"))
      (node (ref "C28") (pin "1") (pinfunction "1_1") (pintype "passive"))
      (node (ref "C3") (pin "1") (pinfunction "1_1") (pintype "passive"))
      (node (ref "C33") (pin "1") (pinfunction "1_1") (pintype "passive"))
      (node (ref "C34") (pin "1") (pinfunction "1_1") (pintype "passive"))
      (node (ref "C35") (pin "1") (pinfunction "1_1") (pintype "passive"))
      (node (ref "C36") (pin "1") (pinfunction "1_1") (pintype "passive"))
      (node (ref "C65") (pin "1") (pinfunction "1_1") (pintype "passive"))
      (node (ref "C96") (pin "1") (pinfunction "1_1") (pintype "passive"))
      (node (ref "CON2") (pin "2") (pinfunction "2_2") (pintype "passive"))
      (node (ref "R131") (pin "1") (pinfunction "1_1") (pintype "passive"))
      (node (ref "R138") (pin "1") (pinfunction "1_1") (pintype "passive"))
      (node (ref "R3") (pin "2") (pinfunction "2_2") (pintype "passive"))
      (node (ref "R34") (pin "1") (pinfunction "1_1") (pintype "passive"))
      (node (ref "R4") (pin "1") (pinfunction "1_1") (pintype "passive"))
      (node (ref "R53") (pin "2") (pinfunction "2_2") (pintype "passive"))
      (node (ref "R57") (pin "1") (pinfunction "1_1") (pintype "passive"))
      (node (ref "R78") (pin "1") (pinfunction "1_1") (pintype "passive"))
      (node (ref "TP5V") (pin "1") (pinfunction "TP?_1") (pintype "passive"))
      (node (ref "U14") (pin "12") (pinfunction "VDD_12") (pintype "passive"))
      (node (ref "U19") (pin "12") (pinfunction "VDD_12") (pintype "passive"))
      (node (ref "U20") (pin "19") (pinfunction "VCC_19") (pintype "passive"))
      (node (ref "U21") (pin "12") (pinfunction "VDD_12") (pintype "passive"))
      (node (ref "U4") (pin "12") (pinfunction "VDD_12") (pintype "passive"))
      (node (ref "U6") (pin "14") (pinfunction "VCC_14") (pintype "passive"))
      (node (ref "U6") (pin "24") (pinfunction "AVCC_24") (pintype "passive"))
      (node (ref "U6") (pin "34") (pinfunction "VCC_34") (pintype "passive"))
      (node (ref "U6") (pin "42") (pinfunction "AREF_42") (pintype "passive"))
      (node (ref "U6") (pin "44") (pinfunction "AVCC_44") (pintype "passive"))
      (node (ref "VR1") (pin "3") (pinfunction "VOUT_3") (pintype "passive"))
    )
    (net (code "14") (name "-2.5V") (class "Default")
      (node (ref "C101") (pin "2") (pinfunction "2_2") (pintype "passive"))
      (node (ref "C106") (pin "2") (pinfunction "2_2") (pintype "passive"))
      (node (ref "C13") (pin "2") (pinfunction "2_2") (pintype "passive"))
      (node (ref "C17") (pin "1") (pinfunction "1_1") (pintype "passive"))
      (node (ref "C30") (pin "1") (pinfunction "1_1") (pintype "passive"))
      (node (ref "C45") (pin "1") (pinfunction "1_1") (pintype "passive"))
      (node (ref "C5") (pin "1") (pinfunction "1_1") (pintype "passive"))
      (node (ref "C59") (pin "1") (pinfunction "1_1") (pintype "passive"))
      (node (ref "C63") (pin "1") (pinfunction "1_1") (pintype "passive"))
      (node (ref "C72") (pin "2") (pinfunction "2_2") (pintype "passive"))
      (node (ref "C76") (pin "1") (pinfunction "1_1") (pintype "passive"))
      (node (ref "C78") (pin "1") (pinfunction "1_1") (pintype "passive"))
      (node (ref "C80") (pin "2") (pinfunction "2_2") (pintype "passive"))
      (node (ref "C83") (pin "2") (pinfunction "2_2") (pintype "passive"))
      (node (ref "C92") (pin "2") (pinfunction "2_2") (pintype "passive"))
      (node (ref "D3") (pin "2") (pinfunction "K_2") (pintype "passive"))
      (node (ref "R28") (pin "2") (pinfunction "2_2") (pintype "passive"))
      (node (ref "TP_-2V5") (pin "1") (pinfunction "TP?_1") (pintype "passive"))
      (node (ref "U1") (pin "13") (pinfunction "V-_13") (pintype "passive"))
      (node (ref "U10") (pin "13") (pinfunction "V-_13") (pintype "passive"))
      (node (ref "U11") (pin "2") (pinfunction "V-_2") (pintype "passive"))
      (node (ref "U12") (pin "7") (pinfunction "V-_7") (pintype "passive"))
      (node (ref "U13") (pin "13") (pinfunction "V-_13") (pintype "passive"))
      (node (ref "U15") (pin "7") (pinfunction "V-_7") (pintype "passive"))
      (node (ref "U16") (pin "2") (pinfunction "V-_2") (pintype "passive"))
      (node (ref "U17") (pin "7") (pinfunction "V-_7") (pintype "passive"))
      (node (ref "U18") (pin "7") (pinfunction "V-_7") (pintype "passive"))
      (node (ref "U2") (pin "2") (pinfunction "V-_2") (pintype "passive"))
      (node (ref "U23") (pin "13") (pinfunction "V-_13") (pintype "passive"))
      (node (ref "U3") (pin "13") (pinfunction "V-_13") (pintype "passive"))
      (node (ref "U5") (pin "2") (pinfunction "V-_2") (pintype "passive"))
      (node (ref "U7") (pin "13") (pinfunction "V-_13") (pintype "passive"))
      (node (ref "VR3") (pin "3") (pinfunction "VOUT_3") (pintype "passive"))
    )
    (net (code "15") (name "-5V") (class "Default")
      (node (ref "C102") (pin "1") (pinfunction "1_1") (pintype "passive"))
      (node (ref "C24") (pin "2") (pinfunction "2_2") (pintype "passive"))
      (node (ref "C27") (pin "1") (pinfunction "1_1") (pintype "passive"))
      (node (ref "C64") (pin "1") (pinfunction "1_1") (pintype "passive"))
      (node (ref "C95") (pin "1") (pinfunction "1_1") (pintype "passive"))
      (node (ref "D4") (pin "2") (pinfunction "K_2") (pintype "passive"))
      (node (ref "R36") (pin "2") (pinfunction "2_2") (pintype "passive"))
      (node (ref "TP-5V") (pin "1") (pinfunction "TP?_1") (pintype "passive"))
      (node (ref "U14") (pin "3") (pinfunction "VSS_3") (pintype "passive"))
      (node (ref "U19") (pin "3") (pinfunction "VSS_3") (pintype "passive"))
      (node (ref "U21") (pin "3") (pinfunction "VSS_3") (pintype "passive"))
      (node (ref "U4") (pin "3") (pinfunction "VSS_3") (pintype "passive"))
      (node (ref "VR4") (pin "3") (pinfunction "VOUT_3") (pintype "passive"))
    )
    (net (code "16") (name "/+6.3V") (class "Default")
      (node (ref "C1") (pin "1") (pinfunction "1_1") (pintype "passive"))
      (node (ref "C2") (pin "1") (pinfunction "1_1") (pintype "passive"))
      (node (ref "C7") (pin "1") (pinfunction "1_1") (pintype "passive"))
      (node (ref "U22") (pin "4") (pinfunction "+_4") (pintype "passive"))
      (node (ref "VR1") (pin "1") (pinfunction "VIN_1") (pintype "passive"))
      (node (ref "VR2") (pin "1") (pinfunction "VIN_1") (pintype "passive"))
    )
    (net (code "17") (name "/-6.3V") (class "Default")
      (node (ref "C18") (pin "2") (pinfunction "2_2") (pintype "passive"))
      (node (ref "C25") (pin "2") (pinfunction "2_2") (pintype "passive"))
      (node (ref "C26") (pin "2") (pinfunction "2_2") (pintype "passive"))
      (node (ref "U22") (pin "3") (pinfunction "-_3") (pintype "passive"))
      (node (ref "VR3") (pin "1") (pinfunction "VIN_1") (pintype "passive"))
      (node (ref "VR4") (pin "1") (pinfunction "VIN_1") (pintype "passive"))
    )
    (net (code "18") (name "/BOOT") (class "Default")
      (node (ref "BOOT") (pin "3") (pinfunction "3_3") (pintype "passive"))
      (node (ref "BOOT") (pin "4") (pinfunction "4_4") (pintype "passive"))
      (node (ref "R57") (pin "2") (pinfunction "2_2") (pintype "passive"))
      (node (ref "R60") (pin "1") (pinfunction "1_1") (pintype "passive"))
      (node (ref "U6") (pin "33") (pinfunction "PE2(~{HWB})_33") (pintype "passive"))
    )
    (net (code "19") (name "/BP_100k-250k_OUT_C1") (class "Default")
      (node (ref "C98") (pin "1") (pinfunction "1_1") (pintype "passive"))
      (node (ref "TP10") (pin "1") (pinfunction "TP?_1") (pintype "passive"))
      (node (ref "U10") (pin "10") (pinfunction "OUTC_10") (pintype "passive"))
      (node (ref "U10") (pin "11") (pinfunction "-INC_11") (pintype "passive"))
      (node (ref "U19") (pin "10") (pinfunction "S2B_10") (pintype "passive"))
    )
    (net (code "20") (name "/BP_100k-250k_OUT_C2") (class "Default")
      (node (ref "C105") (pin "1") (pinfunction "1_1") (pintype "passive"))
      (node (ref "TP14") (pin "1") (pinfunction "TP?_1") (pintype "passive"))
      (node (ref "U13") (pin "10") (pinfunction "OUTC_10") (pintype "passive"))
      (node (ref "U13") (pin "11") (pinfunction "-INC_11") (pintype "passive"))
      (node (ref "U21") (pin "10") (pinfunction "S2B_10") (pintype "passive"))
    )
    (net (code "21") (name "/BP_100k-250k_OUT_V1") (class "Default")
      (node (ref "C97") (pin "1") (pinfunction "1_1") (pintype "passive"))
      (node (ref "TP9") (pin "1") (pinfunction "TP?_1") (pintype "passive"))
      (node (ref "U10") (pin "6") (pinfunction "-INB_6") (pintype "passive"))
      (node (ref "U10") (pin "7") (pinfunction "OUTB_7") (pintype "passive"))
      (node (ref "U19") (pin "5") (pinfunction "S1B_5") (pintype "passive"))
    )
    (net (code "22") (name "/BP_100k-250k_OUT_V2") (class "Default")
      (node (ref "C89") (pin "1") (pinfunction "1_1") (pintype "passive"))
      (node (ref "TP13") (pin "1") (pinfunction "TP?_1") (pintype "passive"))
      (node (ref "U13") (pin "6") (pinfunction "-INB_6") (pintype "passive"))
      (node (ref "U13") (pin "7") (pinfunction "OUTB_7") (pintype "passive"))
      (node (ref "U21") (pin "5") (pinfunction "S1B_5") (pintype "passive"))
    )
    (net (code "23") (name "/CS0") (class "Default")
      (node (ref "TP_CS0") (pin "1") (pinfunction "TP?_1") (pintype "passive"))
      (node (ref "U20") (pin "12") (pinfunction "I/O_VCC8_12") (pintype "passive"))
      (node (ref "U6") (pin "8") (pinfunction "PB0(SS/PCINT0)_8") (pintype "passive"))
    )
    (net (code "24") (name "/CS0_SHFTD") (class "Default")
      (node (ref "U12") (pin "4") (pinfunction "~{CS}_4") (pintype "passive"))
      (node (ref "U20") (pin "9") (pinfunction "I/O_VL8_9") (pintype "passive"))
    )
    (net (code "25") (name "/CS1") (class "Default")
      (node (ref "TP_CS1") (pin "1") (pinfunction "TP?_1") (pintype "passive"))
      (node (ref "U20") (pin "13") (pinfunction "I/O_VCC7_13") (pintype "passive"))
      (node (ref "U6") (pin "28") (pinfunction "PB4(PCINT4/ADC11)_28") (pintype "passive"))
    )
    (net (code "26") (name "/CS1_SHFTD") (class "Default")
      (node (ref "U15") (pin "4") (pinfunction "~{CS}_4") (pintype "passive"))
      (node (ref "U20") (pin "8") (pinfunction "I/O_VL7_8") (pintype "passive"))
    )
    (net (code "27") (name "/CS2") (class "Default")
      (node (ref "TP_CS2") (pin "1") (pinfunction "TP?_1") (pintype "passive"))
      (node (ref "U20") (pin "16") (pinfunction "I/O_VCC4_16") (pintype "passive"))
      (node (ref "U6") (pin "29") (pinfunction "PB5(PCINT5/OC1A/~{OC4B}/ADC12)_29") (pintype "passive"))
    )
    (net (code "28") (name "/CS2_SHFTD") (class "Default")
      (node (ref "U18") (pin "4") (pinfunction "~{CS}_4") (pintype "passive"))
      (node (ref "U20") (pin "5") (pinfunction "I/O_VL4_5") (pintype "passive"))
    )
    (net (code "29") (name "/CS3") (class "Default")
      (node (ref "TP_CS3") (pin "1") (pinfunction "TP?_1") (pintype "passive"))
      (node (ref "U20") (pin "17") (pinfunction "I/O_VCC3_17") (pintype "passive"))
      (node (ref "U6") (pin "30") (pinfunction "PB6(PCINT6/OC1B/OC4B/ADC13)_30") (pintype "passive"))
    )
    (net (code "30") (name "/CS3_SHFTD") (class "Default")
      (node (ref "U17") (pin "4") (pinfunction "~{CS}_4") (pintype "passive"))
      (node (ref "U20") (pin "4") (pinfunction "I/O_VL3_4") (pintype "passive"))
    )
    (net (code "31") (name "/FILTER_IN1") (class "Default")
      (node (ref "C84") (pin "2") (pinfunction "2_2") (pintype "passive"))
      (node (ref "R122") (pin "2") (pinfunction "2_2") (pintype "passive"))
      (node (ref "U19") (pin "4") (pinfunction "S1A_4") (pintype "passive"))
    )
    (net (code "32") (name "/FILTER_IN2") (class "Default")
      (node (ref "C90") (pin "2") (pinfunction "2_2") (pintype "passive"))
      (node (ref "R123") (pin "2") (pinfunction "2_2") (pintype "passive"))
      (node (ref "U19") (pin "11") (pinfunction "S2A_11") (pintype "passive"))
    )
    (net (code "33") (name "/FILTER_IN_3") (class "Default")
      (node (ref "C73") (pin "2") (pinfunction "2_2") (pintype "passive"))
      (node (ref "R83") (pin "1") (pinfunction "1_1") (pintype "passive"))
      (node (ref "U21") (pin "4") (pinfunction "S1A_4") (pintype "passive"))
    )
    (net (code "34") (name "/FILTER_IN_4") (class "Default")
      (node (ref "C100") (pin "2") (pinfunction "2_2") (pintype "passive"))
      (node (ref "R97") (pin "2") (pinfunction "2_2") (pintype "passive"))
      (node (ref "U21") (pin "11") (pinfunction "S2A_11") (pintype "passive"))
    )
    (net (code "35") (name "/FILTER_OUT1") (class "Default")
      (node (ref "R128") (pin "2") (pinfunction "2_2") (pintype "passive"))
      (node (ref "TP17") (pin "1") (pinfunction "TP?_1") (pintype "passive"))
      (node (ref "U19") (pin "6") (pinfunction "D1_6") (pintype "passive"))
    )
    (net (code "36") (name "/FILTER_OUT2") (class "Default")
      (node (ref "R126") (pin "2") (pinfunction "2_2") (pintype "passive"))
      (node (ref "TP8") (pin "1") (pinfunction "TP?_1") (pintype "passive"))
      (node (ref "U19") (pin "9") (pinfunction "D2_9") (pintype "passive"))
    )
    (net (code "37") (name "/FILTER_OUT_3") (class "Default")
      (node (ref "R116") (pin "2") (pinfunction "2_2") (pintype "passive"))
      (node (ref "TP23") (pin "1") (pinfunction "TP?_1") (pintype "passive"))
      (node (ref "U21") (pin "6") (pinfunction "D1_6") (pintype "passive"))
    )
    (net (code "38") (name "/FILTER_OUT_4") (class "Default")
      (node (ref "R113") (pin "2") (pinfunction "2_2") (pintype "passive"))
      (node (ref "TP21") (pin "1") (pinfunction "TP?_1") (pintype "passive"))
      (node (ref "U21") (pin "9") (pinfunction "D2_9") (pintype "passive"))
    )
    (net (code "39") (name "/F_MCU_SEL0") (class "Default")
      (node (ref "TP_F0") (pin "1") (pinfunction "TP?_1") (pintype "passive"))
      (node (ref "U4") (pin "1") (pinfunction "A0_1") (pintype "passive"))
      (node (ref "U6") (pin "41") (pinfunction "PF0(ADC0)_41") (pintype "passive"))
    )
    (net (code "40") (name "/F_MCU_SEL1") (class "Default")
      (node (ref "TP_F1") (pin "1") (pinfunction "TP?_1") (pintype "passive"))
      (node (ref "U4") (pin "14") (pinfunction "A1_14") (pintype "passive"))
      (node (ref "U6") (pin "40") (pinfunction "PF1(ADC1)_40") (pintype "passive"))
    )
    (net (code "41") (name "/F_MCU_SEL2") (class "Default")
      (node (ref "TP_F2") (pin "1") (pinfunction "TP?_1") (pintype "passive"))
      (node (ref "U19") (pin "1") (pinfunction "A0_1") (pintype "passive"))
      (node (ref "U6") (pin "39") (pinfunction "PF4(ADC4/TCK)_39") (pintype "passive"))
    )
    (net (code "42") (name "/F_MCU_SEL3") (class "Default")
      (node (ref "TP_F3") (pin "1") (pinfunction "TP?_1") (pintype "passive"))
      (node (ref "U19") (pin "14") (pinfunction "A1_14") (pintype "passive"))
      (node (ref "U6") (pin "38") (pinfunction "PF5(ADC5/TMS)_38") (pintype "passive"))
    )
    (net (code "43") (name "/F_MCU_SEL4") (class "Default")
      (node (ref "TP_F4") (pin "1") (pinfunction "TP?_1") (pintype "passive"))
      (node (ref "U21") (pin "1") (pinfunction "A0_1") (pintype "passive"))
      (node (ref "U6") (pin "37") (pinfunction "PF6(ADC6/TDO)_37") (pintype "passive"))
    )
    (net (code "44") (name "/F_MCU_SEL5") (class "Default")
      (node (ref "TP_F5") (pin "1") (pinfunction "TP?_1") (pintype "passive"))
      (node (ref "U21") (pin "14") (pinfunction "A1_14") (pintype "passive"))
      (node (ref "U6") (pin "36") (pinfunction "PF7(ADC7/TDI)_36") (pintype "passive"))
    )
    (net (code "45") (name "/F_MCU_SEL6") (class "Default")
      (node (ref "TP_F6") (pin "1") (pinfunction "TP?_1") (pintype "passive"))
      (node (ref "U14") (pin "1") (pinfunction "A0_1") (pintype "passive"))
      (node (ref "U6") (pin "1") (pinfunction "PE6(INT.6/AIN0)_1") (pintype "passive"))
    )
    (net (code "46") (name "/F_MCU_SEL7") (class "Default")
      (node (ref "TP_F7") (pin "1") (pinfunction "TP?_1") (pintype "passive"))
      (node (ref "U14") (pin "14") (pinfunction "A1_14") (pintype "passive"))
      (node (ref "U6") (pin "27") (pinfunction "PD7(T0/OC4~{D}/ADC10)_27") (pintype "passive"))
    )
    (net (code "47") (name "/L") (class "Default")
      (node (ref "F1") (pin "2") (pinfunction "2_2") (pintype "passive"))
      (node (ref "F2") (pin "1") (pinfunction "1_1") (pintype "passive"))
      (node (ref "XFR1") (pin "1") (pinfunction "Pri+_1") (pintype "passive"))
    )
    (net (code "48") (name "/MISO") (class "Default")
      (node (ref "CON2") (pin "1") (pinfunction "1_1") (pintype "passive"))
      (node (ref "TP_MISO") (pin "1") (pinfunction "TP?_1") (pintype "passive"))
      (node (ref "U6") (pin "11") (pinfunction "PB3(PDO/PCINT3/MISO)_11") (pintype "passive"))
    )
    (net (code "49") (name "/MOSI") (class "Default")
      (node (ref "CON2") (pin "4") (pinfunction "4_4") (pintype "passive"))
      (node (ref "TP_MOSI") (pin "1") (pinfunction "TP?_1") (pintype "passive"))
      (node (ref "U20") (pin "14") (pinfunction "I/O_VCC6_14") (pintype "passive"))
      (node (ref "U6") (pin "10") (pinfunction "PB2(PDI/PCINT2/MOSI)_10") (pintype "passive"))
    )
    (net (code "52") (name "/MOSI_SHFTD") (class "Default")
      (node (ref "U12") (pin "5") (pinfunction "SDI_5") (pintype "passive"))
      (node (ref "U15") (pin "5") (pinfunction "SDI_5") (pintype "passive"))
      (node (ref "U17") (pin "5") (pinfunction "SDI_5") (pintype "passive"))
      (node (ref "U18") (pin "5") (pinfunction "SDI_5") (pintype "passive"))
      (node (ref "U20") (pin "7") (pinfunction "I/O_VL6_7") (pintype "passive"))
    )
    (net (code "53") (name "/N") (class "Default")
      (node (ref "C23") (pin "1") (pinfunction "1_1") (pintype "passive"))
      (node (ref "CON_N1") (pin "1") (pintype "passive"))
      (node (ref "XFR1") (pin "6") (pinfunction "Pri-_6") (pintype "passive"))
    )
    (net (code "54") (name "/N2") (class "Default")
      (node (ref "C67") (pin "1") (pinfunction "1_1") (pintype "passive"))
      (node (ref "CON_N2") (pin "1") (pintype "passive"))
    )
    (net (code "55") (name "/NOTCH_VOUT1") (class "Default")
      (node (ref "R12") (pin "2") (pinfunction "2_2") (pintype "passive"))
      (node (ref "R121") (pin "1") (pinfunction "1_1") (pintype "passive"))
      (node (ref "TP2") (pin "1") (pinfunction "TP?_1") (pintype "passive"))
      (node (ref "U3") (pin "15") (pinfunction "-IND_15") (pintype "passive"))
      (node (ref "U3") (pin "16") (pinfunction "OUTD_16") (pintype "passive"))
    )
    (net (code "56") (name "/NOTCH_VOUT2") (class "Default")
      (node (ref "R125") (pin "2") (pinfunction "2_2") (pintype "passive"))
      (node (ref "R46") (pin "2") (pinfunction "2_2") (pintype "passive"))
      (node (ref "TP6") (pin "1") (pinfunction "TP?_1") (pintype "passive"))
      (node (ref "U7") (pin "15") (pinfunction "-IND_15") (pintype "passive"))
      (node (ref "U7") (pin "16") (pinfunction "OUTD_16") (pintype "passive"))
    )
    (net (code "57") (name "/NOTCH_VOUT_4") (class "Default")
      (node (ref "R102") (pin "2") (pinfunction "2_2") (pintype "passive"))
      (node (ref "R104") (pin "2") (pinfunction "2_2") (pintype "passive"))
      (node (ref "TP20") (pin "1") (pinfunction "TP?_1") (pintype "passive"))
      (node (ref "U23") (pin "15") (pinfunction "-IND_15") (pintype "passive"))
      (node (ref "U23") (pin "16") (pinfunction "OUTD_16") (pintype "passive"))
    )
    (net (code "58") (name "/Notch_VOUT_3") (class "Default")
      (node (ref "R38") (pin "2") (pinfunction "2_2") (pintype "passive"))
      (node (ref "R76") (pin "1") (pinfunction "1_1") (pintype "passive"))
      (node (ref "TP7") (pin "1") (pinfunction "TP?_1") (pintype "passive"))
      (node (ref "U1") (pin "15") (pinfunction "-IND_15") (pintype "passive"))
      (node (ref "U1") (pin "16") (pinfunction "OUTD_16") (pintype "passive"))
    )
    (net (code "59") (name "/PB7") (class "Default")
      (node (ref "U6") (pin "12") (pinfunction "PB7(PCINT7/OC0A/OC1C/~{RTS})_12") (pintype "passive"))
    )
    (net (code "60") (name "/PC6") (class "Default")
      (node (ref "U6") (pin "31") (pinfunction "PC6(OC3A/~{OC4A})_31") (pintype "passive"))
    )
    (net (code "61") (name "/PC7") (class "Default")
      (node (ref "U6") (pin "32") (pinfunction "PC7(ICP3/CLK0/OC4A)_32") (pintype "passive"))
    )
    (net (code "62") (name "/PD2") (class "Default")
      (node (ref "U6") (pin "20") (pinfunction "PD2(RXD1/INT2)_20") (pintype "passive"))
    )
    (net (code "63") (name "/PD5") (class "Default")
      (node (ref "D_STAT3") (pin "1") (pinfunction "A_1") (pintype "passive"))
      (node (ref "U6") (pin "22") (pinfunction "PD5(XCK1/~{CTS})_22") (pintype "passive"))
    )
    (net (code "64") (name "/PD6") (class "Default")
      (node (ref "D_STAT4") (pin "1") (pinfunction "A_1") (pintype "passive"))
      (node (ref "U6") (pin "26") (pinfunction "PD6(T1/~{OC4D}/ADC9)_26") (pintype "passive"))
    )
    (net (code "65") (name "/PRE_AMP_OUT1") (class "Default")
      (node (ref "R120") (pin "2") (pinfunction "2_2") (pintype "passive"))
      (node (ref "R9") (pin "1") (pinfunction "1_1") (pintype "passive"))
      (node (ref "TP1") (pin "1") (pinfunction "TP?_1") (pintype "passive"))
      (node (ref "U2") (pin "1") (pinfunction "OUT_1") (pintype "passive"))
      (node (ref "U4") (pin "4") (pinfunction "S1A_4") (pintype "passive"))
    )
    (net (code "66") (name "/PRE_AMP_OUT2") (class "Default")
      (node (ref "R124") (pin "2") (pinfunction "2_2") (pintype "passive"))
      (node (ref "R51") (pin "1") (pinfunction "1_1") (pintype "passive"))
      (node (ref "TP4") (pin "1") (pinfunction "TP?_1") (pintype "passive"))
      (node (ref "U4") (pin "11") (pinfunction "S2A_11") (pintype "passive"))
      (node (ref "U5") (pin "1") (pinfunction "OUT_1") (pintype "passive"))
    )
    (net (code "67") (name "/PRE_AMP_OUT_3") (class "Default")
      (node (ref "R37") (pin "2") (pinfunction "2_2") (pintype "passive"))
      (node (ref "R85") (pin "1") (pinfunction "1_1") (pintype "passive"))
      (node (ref "TP11") (pin "1") (pinfunction "TP?_1") (pintype "passive"))
      (node (ref "U11") (pin "1") (pinfunction "OUT_1") (pintype "passive"))
      (node (ref "U14") (pin "4") (pinfunction "S1A_4") (pintype "passive"))
    )
    (net (code "68") (name "/PRE_AMP_OUT_4") (class "Default")
      (node (ref "R109") (pin "2") (pinfunction "2_2") (pintype "passive"))
      (node (ref "R111") (pin "1") (pinfunction "1_1") (pintype "passive"))
      (node (ref "TP18") (pin "1") (pinfunction "TP?_1") (pintype "passive"))
      (node (ref "U14") (pin "11") (pinfunction "S2A_11") (pintype "passive"))
      (node (ref "U16") (pin "1") (pinfunction "OUT_1") (pintype "passive"))
    )
    (net (code "69") (name "/Reset") (class "Default")
      (node (ref "C40") (pin "1") (pinfunction "1_1") (pintype "passive"))
      (node (ref "CON2") (pin "5") (pinfunction "5_5") (pintype "passive"))
      (node (ref "R53") (pin "1") (pinfunction "1_1") (pintype "passive"))
      (node (ref "RESET") (pin "1") (pinfunction "1_1") (pintype "passive"))
      (node (ref "RESET") (pin "2") (pinfunction "2_2") (pintype "passive"))
      (node (ref "U6") (pin "13") (pinfunction "~{RESET}_13") (pintype "passive"))
    )
    (net (code "70") (name "/SCK") (class "Default")
      (node (ref "CON2") (pin "3") (pinfunction "3_3") (pintype "passive"))
      (node (ref "TP_SCK") (pin "1") (pinfunction "TP?_1") (pintype "passive"))
      (node (ref "U20") (pin "15") (pinfunction "I/O_VCC5_15") (pintype "passive"))
      (node (ref "U6") (pin "9") (pinfunction "PB1(PCINT1/SCLK)_9") (pintype "passive"))
    )
    (net (code "71") (name "/SCK_SHFTD") (class "Default")
      (node (ref "U12") (pin "3") (pinfunction "SCK_3") (pintype "passive"))
      (node (ref "U15") (pin "3") (pinfunction "SCK_3") (pintype "passive"))
      (node (ref "U17") (pin "3") (pinfunction "SCK_3") (pintype "passive"))
      (node (ref "U18") (pin "3") (pinfunction "SCK_3") (pintype "passive"))
      (node (ref "U20") (pin "6") (pinfunction "I/O_VL5_6") (pintype "passive"))
    )
    (net (code "72") (name "/SCL") (class "Default")
      (node (ref "TPSCL") (pin "1") (pinfunction "TP?_1") (pintype "passive"))
      (node (ref "U6") (pin "18") (pinfunction "PD0(OC0B/SCL/INT0)_18") (pintype "passive"))
    )
    (net (code "73") (name "/SDA") (class "Default")
      (node (ref "TPSDA") (pin "1") (pinfunction "TP?_1") (pintype "passive"))
      (node (ref "U6") (pin "19") (pinfunction "PD1(SDA/INT1)_19") (pintype "passive"))
    )
    (net (code "74") (name "/STAT1_LED") (class "Default")
      (node (ref "D_STAT1") (pin "1") (pinfunction "A_1") (pintype "passive"))
      (node (ref "U6") (pin "21") (pinfunction "PD3(TXD1/INT3)_21") (pintype "passive"))
    )
    (net (code "75") (name "/STAT2_LED") (class "Default")
      (node (ref "D_STAT2") (pin "1") (pinfunction "A_1") (pintype "passive"))
      (node (ref "U6") (pin "25") (pinfunction "PD4(ICP1/ADC8)_25") (pintype "passive"))
    )
    (net (code "76") (name "/VOLT_SIG") (class "Default")
      (node (ref "R27") (pin "2") (pinfunction "2_2") (pintype "passive"))
      (node (ref "R32") (pin "2") (pinfunction "2_2") (pintype "passive"))
      (node (ref "TP3") (pin "1") (pinfunction "TP?_1") (pintype "passive"))
      (node (ref "TVS2") (pin "A") (pinfunction "2_A") (pintype "passive"))
      (node (ref "U2") (pin "3") (pinfunction "IN+_3") (pintype "passive"))
    )
    (net (code "77") (name "/VOLT_SIG_2") (class "Default")
      (node (ref "R84") (pin "2") (pinfunction "2_2") (pintype "passive"))
      (node (ref "R93") (pin "2") (pinfunction "2_2") (pintype "passive"))
      (node (ref "TP16") (pin "1") (pinfunction "TP?_1") (pintype "passive"))
      (node (ref "TVS1") (pin "A") (pinfunction "2_A") (pintype "passive"))
      (node (ref "U11") (pin "3") (pinfunction "IN+_3") (pintype "passive"))
    )
    (net (code "79") (name "GND") (class "Default")
      (node (ref "BOOT") (pin "1") (pinfunction "1_1") (pintype "passive"))
      (node (ref "BOOT") (pin "2") (pinfunction "2_2") (pintype "passive"))
      (node (ref "C1") (pin "2") (pinfunction "2_2") (pintype "passive"))
      (node (ref "C101") (pin "1") (pinfunction "1_1") (pintype "passive"))
      (node (ref "C102") (pin "2") (pinfunction "2_2") (pintype "passive"))
      (node (ref "C103") (pin "2") (pinfunction "2_2") (pintype "passive"))
      (node (ref "C104") (pin "1") (pinfunction "1_1") (pintype "passive"))
      (node (ref "C106") (pin "1") (pinfunction "1_1") (pintype "passive"))
      (node (ref "C120") (pin "2") (pinfunction "2_2") (pintype "passive"))
      (node (ref "C121") (pin "2") (pinfunction "2_2") (pintype "passive"))
      (node (ref "C13") (pin "1") (pinfunction "1_1") (pintype "passive"))
      (node (ref "C16") (pin "2") (pinfunction "2_2") (pintype "passive"))
      (node (ref "C17") (pin "2") (pinfunction "2_2") (pintype "passive"))
      (node (ref "C18") (pin "1") (pinfunction "1_1") (pintype "passive"))
      (node (ref "C2") (pin "2") (pinfunction "2_2") (pintype "passive"))
      (node (ref "C23") (pin "2") (pinfunction "2_2") (pintype "passive"))
      (node (ref "C24") (pin "1") (pinfunction "1_1") (pintype "passive"))
      (node (ref "C25") (pin "1") (pinfunction "1_1") (pintype "passive"))
      (node (ref "C26") (pin "1") (pinfunction "1_1") (pintype "passive"))
      (node (ref "C27") (pin "2") (pinfunction "2_2") (pintype "passive"))
      (node (ref "C28") (pin "2") (pinfunction "2_2") (pintype "passive"))
      (node (ref "C29") (pin "2") (pinfunction "2_2") (pintype "passive"))
      (node (ref "C3") (pin "2") (pinfunction "2_2") (pintype "passive"))
      (node (ref "C30") (pin "2") (pinfunction "2_2") (pintype "passive"))
      (node (ref "C33") (pin "2") (pinfunction "2_2") (pintype "passive"))
      (node (ref "C34") (pin "2") (pinfunction "2_2") (pintype "passive"))
      (node (ref "C35") (pin "2") (pinfunction "2_2") (pintype "passive"))
      (node (ref "C36") (pin "2") (pinfunction "2_2") (pintype "passive"))
      (node (ref "C39") (pin "2") (pinfunction "2_2") (pintype "passive"))
      (node (ref "C4") (pin "2") (pinfunction "2_2") (pintype "passive"))
      (node (ref "C40") (pin "2") (pinfunction "2_2") (pintype "passive"))
      (node (ref "C41") (pin "2") (pinfunction "2_2") (pintype "passive"))
      (node (ref "C44") (pin "2") (pinfunction "2_2") (pintype "passive"))
      (node (ref "C45") (pin "2") (pinfunction "2_2") (pintype "passive"))
      (node (ref "C48") (pin "2") (pinfunction "2_2") (pintype "passive"))
      (node (ref "C5") (pin "2") (pinfunction "2_2") (pintype "passive"))
      (node (ref "C51") (pin "1") (pinfunction "1_1") (pintype "passive"))
      (node (ref "C58") (pin "2") (pinfunction "2_2") (pintype "passive"))
      (node (ref "C59") (pin "2") (pinfunction "2_2") (pintype "passive"))
      (node (ref "C6") (pin "2") (pinfunction "2_2") (pintype "passive"))
      (node (ref "C62") (pin "2") (pinfunction "2_2") (pintype "passive"))
      (node (ref "C63") (pin "2") (pinfunction "2_2") (pintype "passive"))
      (node (ref "C64") (pin "2") (pinfunction "2_2") (pintype "passive"))
      (node (ref "C65") (pin "2") (pinfunction "2_2") (pintype "passive"))
      (node (ref "C67") (pin "2") (pinfunction "2_2") (pintype "passive"))
      (node (ref "C7") (pin "2") (pinfunction "2_2") (pintype "passive"))
      (node (ref "C72") (pin "1") (pinfunction "1_1") (pintype "passive"))
      (node (ref "C75") (pin "2") (pinfunction "2_2") (pintype "passive"))
      (node (ref "C76") (pin "2") (pinfunction "2_2") (pintype "passive"))
      (node (ref "C77") (pin "2") (pinfunction "2_2") (pintype "passive"))
      (node (ref "C78") (pin "2") (pinfunction "2_2") (pintype "passive"))
      (node (ref "C79") (pin "1") (pinfunction "1_1") (pintype "passive"))
      (node (ref "C80") (pin "1") (pinfunction "1_1") (pintype "passive"))
      (node (ref "C81") (pin "1") (pinfunction "1_1") (pintype "passive"))
      (node (ref "C82") (pin "1") (pinfunction "1_1") (pintype "passive"))
      (node (ref "C83") (pin "1") (pinfunction "1_1") (pintype "passive"))
      (node (ref "C85") (pin "1") (pinfunction "1_1") (pintype "passive"))
      (node (ref "C88") (pin "1") (pinfunction "1_1") (pintype "passive"))
      (node (ref "C91") (pin "1") (pinfunction "1_1") (pintype "passive"))
      (node (ref "C92") (pin "1") (pinfunction "1_1") (pintype "passive"))
      (node (ref "C93") (pin "1") (pinfunction "1_1") (pintype "passive"))
      (node (ref "C94") (pin "1") (pinfunction "1_1") (pintype "passive"))
      (node (ref "C95") (pin "2") (pinfunction "2_2") (pintype "passive"))
      (node (ref "C96") (pin "2") (pinfunction "2_2") (pintype "passive"))
      (node (ref "CN1") (pin "5") (pinfunction "5_5") (pintype "passive"))
      (node (ref "CON1") (pin "2") (pinfunction "2_2") (pintype "passive"))
      (node (ref "CON10") (pin "2") (pinfunction "2_2") (pintype "passive"))
      (node (ref "CON2") (pin "6") (pinfunction "6_6") (pintype "passive"))
      (node (ref "CON6") (pin "2") (pinfunction "2_2") (pintype "passive"))
      (node (ref "CON7") (pin "2") (pinfunction "2_2") (pintype "passive"))
      (node (ref "CON8") (pin "2") (pinfunction "2_2") (pintype "passive"))
      (node (ref "CON9") (pin "2") (pinfunction "2_2") (pintype "passive"))
      (node (ref "CON_FGND") (pin "1") (pintype "passive"))
      (node (ref "D1") (pin "2") (pinfunction "K_2") (pintype "passive"))
      (node (ref "D2") (pin "2") (pinfunction "K_2") (pintype "passive"))
      (node (ref "R1") (pin "1") (pinfunction "1_1") (pintype "passive"))
      (node (ref "R10") (pin "2") (pinfunction "2_2") (pintype "passive"))
      (node (ref "R101") (pin "1") (pinfunction "1_1") (pintype "passive"))
      (node (ref "R106") (pin "1") (pinfunction "1_1") (pintype "passive"))
      (node (ref "R11") (pin "1") (pinfunction "1_1") (pintype "passive"))
      (node (ref "R112") (pin "2") (pinfunction "2_2") (pintype "passive"))
      (node (ref "R115") (pin "2") (pinfunction "2_2") (pintype "passive"))
      (node (ref "R118") (pin "2") (pinfunction "2_2") (pintype "passive"))
      (node (ref "R127") (pin "2") (pinfunction "2_2") (pintype "passive"))
      (node (ref "R129") (pin "2") (pinfunction "2_2") (pintype "passive"))
      (node (ref "R132") (pin "1") (pinfunction "1_1") (pintype "passive"))
      (node (ref "R133") (pin "1") (pinfunction "1_1") (pintype "passive"))
      (node (ref "R140") (pin "1") (pinfunction "1_1") (pintype "passive"))
      (node (ref "R144") (pin "2") (pinfunction "2_2") (pintype "passive"))
      (node (ref "R145") (pin "2") (pinfunction "2_2") (pintype "passive"))
      (node (ref "R146") (pin "2") (pinfunction "2_2") (pintype "passive"))
      (node (ref "R15") (pin "2") (pinfunction "2_2") (pintype "passive"))
      (node (ref "R18") (pin "2") (pinfunction "2_2") (pintype "passive"))
      (node (ref "R2") (pin "1") (pinfunction "1_1") (pintype "passive"))
      (node (ref "R21") (pin "1") (pinfunction "1_1") (pintype "passive"))
      (node (ref "R24") (pin "2") (pinfunction "2_2") (pintype "passive"))
      (node (ref "R32") (pin "1") (pinfunction "1_1") (pintype "passive"))
      (node (ref "R33") (pin "1") (pinfunction "1_1") (pintype "passive"))
      (node (ref "R35") (pin "2") (pinfunction "2_2") (pintype "passive"))
      (node (ref "R39") (pin "1") (pinfunction "1_1") (pintype "passive"))
      (node (ref "R40") (pin "1") (pinfunction "1_1") (pintype "passive"))
      (node (ref "R45") (pin "1") (pinfunction "1_1") (pintype "passive"))
      (node (ref "R52") (pin "2") (pinfunction "2_2") (pintype "passive"))
      (node (ref "R56") (pin "2") (pinfunction "2_2") (pintype "passive"))
      (node (ref "R6") (pin "1") (pinfunction "1_1") (pintype "passive"))
      (node (ref "R60") (pin "2") (pinfunction "2_2") (pintype "passive"))
      (node (ref "R8") (pin "1") (pinfunction "1_1") (pintype "passive"))
      (node (ref "R86") (pin "2") (pinfunction "2_2") (pintype "passive"))
      (node (ref "R88") (pin "1") (pinfunction "1_1") (pintype "passive"))
      (node (ref "R91") (pin "1") (pinfunction "1_1") (pintype "passive"))
      (node (ref "R93") (pin "1") (pinfunction "1_1") (pintype "passive"))
      (node (ref "R94") (pin "1") (pinfunction "1_1") (pintype "passive"))
      (node (ref "RESET") (pin "3") (pinfunction "3_3") (pintype "passive"))
      (node (ref "RESET") (pin "4") (pinfunction "4_4") (pintype "passive"))
      (node (ref "TP_GND") (pin "1") (pinfunction "TP?_1") (pintype "passive"))
      (node (ref "TP_GND2") (pin "1") (pinfunction "TP?_1") (pintype "passive"))
      (node (ref "TVS1") (pin "C") (pinfunction "1_C") (pintype "passive"))
      (node (ref "TVS2") (pin "C") (pinfunction "1_C") (pintype "passive"))
      (node (ref "TVS3") (pin "C") (pinfunction "1_C") (pintype "passive"))
      (node (ref "TVS4") (pin "C") (pinfunction "1_C") (pintype "passive"))
      (node (ref "U12") (pin "10") (pinfunction "GRT_10") (pintype "passive"))
      (node (ref "U12") (pin "11") (pinfunction "GRT_11") (pintype "passive"))
      (node (ref "U12") (pin "2") (pinfunction "DGND_2") (pintype "passive"))
      (node (ref "U14") (pin "13") (pinfunction "GND_13") (pintype "passive"))
      (node (ref "U15") (pin "10") (pinfunction "GRT_10") (pintype "passive"))
      (node (ref "U15") (pin "11") (pinfunction "GRT_11") (pintype "passive"))
      (node (ref "U15") (pin "2") (pinfunction "DGND_2") (pintype "passive"))
      (node (ref "U17") (pin "10") (pinfunction "GRT_10") (pintype "passive"))
      (node (ref "U17") (pin "11") (pinfunction "GRT_11") (pintype "passive"))
      (node (ref "U17") (pin "2") (pinfunction "DGND_2") (pintype "passive"))
      (node (ref "U18") (pin "10") (pinfunction "GRT_10") (pintype "passive"))
      (node (ref "U18") (pin "11") (pinfunction "GRT_11") (pintype "passive"))
      (node (ref "U18") (pin "2") (pinfunction "DGND_2") (pintype "passive"))
      (node (ref "U19") (pin "13") (pinfunction "GND_13") (pintype "passive"))
      (node (ref "U20") (pin "11") (pinfunction "GND_11") (pintype "passive"))
      (node (ref "U21") (pin "13") (pinfunction "GND_13") (pintype "passive"))
      (node (ref "U4") (pin "13") (pinfunction "GND_13") (pintype "passive"))
      (node (ref "U6") (pin "15") (pinfunction "GND_15") (pintype "passive"))
      (node (ref "U6") (pin "23") (pinfunction "GND_23") (pintype "passive"))
      (node (ref "U6") (pin "35") (pinfunction "GND_35") (pintype "passive"))
      (node (ref "U6") (pin "43") (pinfunction "GND_43") (pintype "passive"))
      (node (ref "U6") (pin "5") (pinfunction "UGND_5") (pintype "passive"))
      (node (ref "X1") (pin "2") (pinfunction "2_2") (pintype "passive"))
      (node (ref "X1") (pin "4") (pinfunction "4_4") (pintype "passive"))
      (node (ref "XFR1") (pin "10") (pinfunction "Sec+_10") (pintype "passive"))
      (node (ref "XFR1") (pin "9") (pinfunction "Sec-_9") (pintype "passive"))
    )
    (net (code "80") (name "Net-(C10-Pad2)") (class "Default")
      (node (ref "C10") (pin "2") (pinfunction "2_2") (pintype "passive"))
      (node (ref "C9") (pin "2") (pinfunction "2_2") (pintype "passive"))
      (node (ref "R16") (pin "2") (pinfunction "2_2") (pintype "passive"))
      (node (ref "R17") (pin "1") (pinfunction "1_1") (pintype "passive"))
    )
    (net (code "81") (name "Net-(C11-Pad2)") (class "Default")
      (node (ref "C11") (pin "2") (pinfunction "2_2") (pintype "passive"))
      (node (ref "C12") (pin "2") (pinfunction "2_2") (pintype "passive"))
      (node (ref "R19") (pin "1") (pinfunction "1_1") (pintype "passive"))
      (node (ref "R20") (pin "2") (pinfunction "2_2") (pintype "passive"))
    )
    (net (code "82") (name "Net-(C14-Pad1)") (class "Default")
      (node (ref "C14") (pin "1") (pinfunction "1_1") (pintype "passive"))
      (node (ref "C15") (pin "2") (pinfunction "2_2") (pintype "passive"))
      (node (ref "R22") (pin "2") (pinfunction "2_2") (pintype "passive"))
      (node (ref "R23") (pin "2") (pinfunction "2_2") (pintype "passive"))
    )
    (net (code "83") (name "Net-(C14-Pad2)") (class "Default")
      (node (ref "C14") (pin "2") (pinfunction "2_2") (pintype "passive"))
      (node (ref "R120") (pin "1") (pinfunction "1_1") (pintype "passive"))
      (node (ref "R16") (pin "1") (pinfunction "1_1") (pintype "passive"))
    )
    (net (code "84") (name "Net-(C19-Pad2)") (class "Default")
      (node (ref "C19") (pin "2") (pinfunction "2_2") (pintype "passive"))
      (node (ref "C8") (pin "2") (pinfunction "2_2") (pintype "passive"))
      (node (ref "R29") (pin "1") (pinfunction "1_1") (pintype "passive"))
      (node (ref "R30") (pin "2") (pinfunction "2_2") (pintype "passive"))
    )
    (net (code "85") (name "Net-(C20-Pad2)") (class "Default")
      (node (ref "C20") (pin "2") (pinfunction "2_2") (pintype "passive"))
      (node (ref "C21") (pin "1") (pinfunction "1_1") (pintype "passive"))
      (node (ref "R25") (pin "2") (pinfunction "2_2") (pintype "passive"))
      (node (ref "R26") (pin "2") (pinfunction "2_2") (pintype "passive"))
    )
    (net (code "86") (name "Net-(C22-Pad1)") (class "Default")
      (node (ref "C22") (pin "1") (pinfunction "1_1") (pintype "passive"))
      (node (ref "F2") (pin "2") (pinfunction "2_2") (pintype "passive"))
    )
    (net (code "87") (name "Net-(C22-Pad2)") (class "Default")
      (node (ref "C22") (pin "2") (pinfunction "2_2") (pintype "passive"))
      (node (ref "R27") (pin "1") (pinfunction "1_1") (pintype "passive"))
      (node (ref "R33") (pin "2") (pinfunction "2_2") (pintype "passive"))
    )
    (net (code "88") (name "Net-(C31-Pad2)") (class "Default")
      (node (ref "C31") (pin "2") (pinfunction "2_2") (pintype "passive"))
      (node (ref "C32") (pin "2") (pinfunction "2_2") (pintype "passive"))
      (node (ref "R41") (pin "2") (pinfunction "2_2") (pintype "passive"))
      (node (ref "R42") (pin "1") (pinfunction "1_1") (pintype "passive"))
    )
    (net (code "89") (name "Net-(C37-Pad1)") (class "Default")
      (node (ref "C37") (pin "1") (pinfunction "1_1") (pintype "passive"))
      (node (ref "C38") (pin "2") (pinfunction "2_2") (pintype "passive"))
      (node (ref "R49") (pin "2") (pinfunction "2_2") (pintype "passive"))
      (node (ref "R50") (pin "2") (pinfunction "2_2") (pintype "passive"))
    )
    (net (code "90") (name "Net-(C37-Pad2)") (class "Default")
      (node (ref "C37") (pin "2") (pinfunction "2_2") (pintype "passive"))
      (node (ref "R124") (pin "1") (pinfunction "1_1") (pintype "passive"))
      (node (ref "R41") (pin "1") (pinfunction "1_1") (pintype "passive"))
    )
    (net (code "91") (name "Net-(C42-Pad2)") (class "Default")
      (node (ref "C42") (pin "2") (pinfunction "2_2") (pintype "passive"))
      (node (ref "C43") (pin "2") (pinfunction "2_2") (pintype "passive"))
      (node (ref "R54") (pin "1") (pinfunction "1_1") (pintype "passive"))
      (node (ref "R55") (pin "2") (pinfunction "2_2") (pintype "passive"))
    )
    (net (code "92") (name "Net-(C46-Pad2)") (class "Default")
      (node (ref "C46") (pin "2") (pinfunction "2_2") (pintype "passive"))
      (node (ref "C47") (pin "1") (pinfunction "1_1") (pintype "passive"))
      (node (ref "R58") (pin "2") (pinfunction "2_2") (pintype "passive"))
      (node (ref "R59") (pin "2") (pinfunction "2_2") (pintype "passive"))
    )
    (net (code "93") (name "Net-(C52-Pad2)") (class "Default")
      (node (ref "C52") (pin "2") (pinfunction "2_2") (pintype "passive"))
      (node (ref "C53") (pin "2") (pinfunction "2_2") (pintype "passive"))
      (node (ref "R71") (pin "2") (pinfunction "2_2") (pintype "passive"))
      (node (ref "R72") (pin "1") (pinfunction "1_1") (pintype "passive"))
    )
    (net (code "94") (name "Net-(C54-Pad2)") (class "Default")
      (node (ref "C54") (pin "2") (pinfunction "2_2") (pintype "passive"))
      (node (ref "C55") (pin "2") (pinfunction "2_2") (pintype "passive"))
      (node (ref "R73") (pin "1") (pinfunction "1_1") (pintype "passive"))
      (node (ref "R74") (pin "2") (pinfunction "2_2") (pintype "passive"))
    )
    (net (code "95") (name "Net-(C56-Pad1)") (class "Default")
      (node (ref "C56") (pin "1") (pinfunction "1_1") (pintype "passive"))
      (node (ref "C57") (pin "2") (pinfunction "2_2") (pintype "passive"))
      (node (ref "R75") (pin "2") (pinfunction "2_2") (pintype "passive"))
      (node (ref "R77") (pin "2") (pinfunction "2_2") (pintype "passive"))
    )
    (net (code "96") (name "Net-(C56-Pad2)") (class "Default")
      (node (ref "C56") (pin "2") (pinfunction "2_2") (pintype "passive"))
      (node (ref "R37") (pin "1") (pinfunction "1_1") (pintype "passive"))
      (node (ref "R71") (pin "1") (pinfunction "1_1") (pintype "passive"))
    )
    (net (code "97") (name "Net-(C60-Pad2)") (class "Default")
      (node (ref "C60") (pin "2") (pinfunction "2_2") (pintype "passive"))
      (node (ref "C61") (pin "1") (pinfunction "1_1") (pintype "passive"))
      (node (ref "R79") (pin "2") (pinfunction "2_2") (pintype "passive"))
      (node (ref "R81") (pin "2") (pinfunction "2_2") (pintype "passive"))
    )
    (net (code "98") (name "Net-(C66-Pad1)") (class "Default")
      (node (ref "C66") (pin "1") (pinfunction "1_1") (pintype "passive"))
      (node (ref "F3") (pin "2") (pinfunction "2_2") (pintype "passive"))
    )
    (net (code "99") (name "Net-(C66-Pad2)") (class "Default")
      (node (ref "C66") (pin "2") (pinfunction "2_2") (pintype "passive"))
      (node (ref "R84") (pin "1") (pinfunction "1_1") (pintype "passive"))
      (node (ref "R94") (pin "2") (pinfunction "2_2") (pintype "passive"))
    )
    (net (code "100") (name "Net-(C68-Pad2)") (class "Default")
      (node (ref "C68") (pin "2") (pinfunction "2_2") (pintype "passive"))
      (node (ref "C69") (pin "2") (pinfunction "2_2") (pintype "passive"))
      (node (ref "R100") (pin "1") (pinfunction "1_1") (pintype "passive"))
      (node (ref "R99") (pin "2") (pinfunction "2_2") (pintype "passive"))
    )
    (net (code "101") (name "Net-(C70-Pad1)") (class "Default")
      (node (ref "C70") (pin "1") (pinfunction "1_1") (pintype "passive"))
      (node (ref "C71") (pin "2") (pinfunction "2_2") (pintype "passive"))
      (node (ref "R107") (pin "2") (pinfunction "2_2") (pintype "passive"))
      (node (ref "R108") (pin "2") (pinfunction "2_2") (pintype "passive"))
    )
    (net (code "102") (name "Net-(C70-Pad2)") (class "Default")
      (node (ref "C70") (pin "2") (pinfunction "2_2") (pintype "passive"))
      (node (ref "R98") (pin "1") (pinfunction "1_1") (pintype "passive"))
      (node (ref "R99") (pin "1") (pinfunction "1_1") (pintype "passive"))
    )
    (net (code "103") (name "Net-(C73-Pad1)") (class "Default")
      (node (ref "C73") (pin "1") (pinfunction "1_1") (pintype "passive"))
      (node (ref "C74") (pin "2") (pinfunction "2_2") (pintype "passive"))
      (node (ref "R89") (pin "1") (pinfunction "1_1") (pintype "passive"))
    )
    (net (code "104") (name "Net-(C84-Pad1)") (class "Default")
      (node (ref "C84") (pin "1") (pinfunction "1_1") (pintype "passive"))
      (node (ref "C86") (pin "2") (pinfunction "2_2") (pintype "passive"))
      (node (ref "R119") (pin "1") (pinfunction "1_1") (pintype "passive"))
    )
    (net (code "105") (name "Net-(C87-Pad2)") (class "Default")
      (node (ref "C87") (pin "2") (pinfunction "2_2") (pintype "passive"))
      (node (ref "C90") (pin "1") (pinfunction "1_1") (pintype "passive"))
      (node (ref "R130") (pin "1") (pinfunction "1_1") (pintype "passive"))
    )
    (net (code "106") (name "Net-(C89-Pad2)") (class "Default")
      (node (ref "C89") (pin "2") (pinfunction "2_2") (pintype "passive"))
      (node (ref "R95") (pin "2") (pinfunction "2_2") (pintype "passive"))
      (node (ref "R96") (pin "1") (pinfunction "1_1") (pintype "passive"))
    )
    (net (code "107") (name "Net-(C97-Pad2)") (class "Default")
      (node (ref "C97") (pin "2") (pinfunction "2_2") (pintype "passive"))
      (node (ref "R134") (pin "2") (pinfunction "2_2") (pintype "passive"))
      (node (ref "R135") (pin "1") (pinfunction "1_1") (pintype "passive"))
    )
    (net (code "108") (name "Net-(C98-Pad2)") (class "Default")
      (node (ref "C98") (pin "2") (pinfunction "2_2") (pintype "passive"))
      (node (ref "R136") (pin "1") (pinfunction "1_1") (pintype "passive"))
      (node (ref "R137") (pin "2") (pinfunction "2_2") (pintype "passive"))
    )
    (net (code "109") (name "Net-(C100-Pad1)") (class "Default")
      (node (ref "C100") (pin "1") (pinfunction "1_1") (pintype "passive"))
      (node (ref "C99") (pin "2") (pinfunction "2_2") (pintype "passive"))
      (node (ref "R139") (pin "1") (pinfunction "1_1") (pintype "passive"))
    )
    (net (code "110") (name "Net-(C105-Pad2)") (class "Default")
      (node (ref "C105") (pin "2") (pinfunction "2_2") (pintype "passive"))
      (node (ref "R141") (pin "1") (pinfunction "1_1") (pintype "passive"))
      (node (ref "R142") (pin "2") (pinfunction "2_2") (pintype "passive"))
    )
    (net (code "111") (name "Net-(C107-Pad2)") (class "Default")
      (node (ref "C107") (pin "2") (pinfunction "2_2") (pintype "passive"))
      (node (ref "C108") (pin "1") (pinfunction "1_1") (pintype "passive"))
      (node (ref "R31") (pin "2") (pinfunction "2_2") (pintype "passive"))
      (node (ref "R87") (pin "2") (pinfunction "2_2") (pintype "passive"))
    )
    (net (code "112") (name "Net-(CN1-Pad2)") (class "Default")
      (node (ref "CN1") (pin "2") (pinfunction "2_2") (pintype "passive"))
      (node (ref "R43") (pin "1") (pinfunction "1_1") (pintype "passive"))
    )
    (net (code "113") (name "Net-(CN1-Pad3)") (class "Default")
      (node (ref "CN1") (pin "3") (pinfunction "3_3") (pintype "passive"))
      (node (ref "R47") (pin "1") (pinfunction "1_1") (pintype "passive"))
    )
    (net (code "114") (name "Net-(CON_L1-Pad1)") (class "Default")
      (node (ref "CON_L1") (pin "1") (pintype "passive"))
      (node (ref "F1") (pin "1") (pinfunction "1_1") (pintype "passive"))
    )
    (net (code "115") (name "Net-(CON_L2-Pad1)") (class "Default")
      (node (ref "CON_L2") (pin "1") (pintype "passive"))
      (node (ref "F3") (pin "1") (pinfunction "1_1") (pintype "passive"))
    )
    (net (code "116") (name "Net-(D1-A)") (class "Default")
      (node (ref "D1") (pin "1") (pinfunction "A_1") (pintype "passive"))
      (node (ref "R3") (pin "1") (pinfunction "1_1") (pintype "passive"))
    )
    (net (code "117") (name "Net-(D2-A)") (class "Default")
      (node (ref "D2") (pin "1") (pinfunction "A_1") (pintype "passive"))
      (node (ref "R7") (pin "1") (pinfunction "1_1") (pintype "passive"))
    )
    (net (code "118") (name "Net-(D3-A)") (class "Default")
      (node (ref "D3") (pin "1") (pinfunction "A_1") (pintype "passive"))
      (node (ref "R15") (pin "1") (pinfunction "1_1") (pintype "passive"))
    )
    (net (code "119") (name "Net-(D4-A)") (class "Default")
      (node (ref "D4") (pin "1") (pinfunction "A_1") (pintype "passive"))
      (node (ref "R24") (pin "1") (pinfunction "1_1") (pintype "passive"))
    )
    (net (code "120") (name "Net-(D_STAT1-K)") (class "Default")
      (node (ref "D_STAT1") (pin "2") (pinfunction "K_2") (pintype "passive"))
      (node (ref "R56") (pin "1") (pinfunction "1_1") (pintype "passive"))
    )
    (net (code "121") (name "Net-(D_STAT2-K)") (class "Default")
      (node (ref "D_STAT2") (pin "2") (pinfunction "K_2") (pintype "passive"))
      (node (ref "R144") (pin "1") (pinfunction "1_1") (pintype "passive"))
    )
    (net (code "122") (name "Net-(D_STAT3-K)") (class "Default")
      (node (ref "D_STAT3") (pin "2") (pinfunction "K_2") (pintype "passive"))
      (node (ref "R145") (pin "1") (pinfunction "1_1") (pintype "passive"))
    )
    (net (code "123") (name "Net-(D_STAT4-K)") (class "Default")
      (node (ref "D_STAT4") (pin "2") (pinfunction "K_2") (pintype "passive"))
      (node (ref "R146") (pin "1") (pinfunction "1_1") (pintype "passive"))
    )
    (net (code "124") (name "Net-(R109-Pad1)") (class "Default")
      (node (ref "R109") (pin "1") (pinfunction "1_1") (pintype "passive"))
      (node (ref "R98") (pin "2") (pinfunction "2_2") (pintype "passive"))
    )
    (net (code "125") (name "Net-(TP5-TP?)") (class "Default")
      (node (ref "CON7") (pin "1") (pinfunction "1_1") (pintype "passive"))
      (node (ref "R39") (pin "2") (pinfunction "2_2") (pintype "passive"))
      (node (ref "TP5") (pin "1") (pinfunction "TP?_1") (pintype "passive"))
      (node (ref "TVS4") (pin "A") (pinfunction "2_A") (pintype "passive"))
      (node (ref "U5") (pin "3") (pinfunction "IN+_3") (pintype "passive"))
    )
    (net (code "126") (name "Net-(TP12-TP?)") (class "Default")
      (node (ref "R83") (pin "2") (pinfunction "2_2") (pintype "passive"))
      (node (ref "TP12") (pin "1") (pinfunction "TP?_1") (pintype "passive"))
      (node (ref "U14") (pin "6") (pinfunction "D1_6") (pintype "passive"))
    )
    (net (code "127") (name "Net-(TP15-TP?)") (class "Default")
      (node (ref "R97") (pin "1") (pinfunction "1_1") (pintype "passive"))
      (node (ref "TP15") (pin "1") (pinfunction "TP?_1") (pintype "passive"))
      (node (ref "U14") (pin "9") (pinfunction "D2_9") (pintype "passive"))
    )
    (net (code "128") (name "Net-(TP19-TP?)") (class "Default")
      (node (ref "CON1") (pin "1") (pinfunction "1_1") (pintype "passive"))
      (node (ref "R106") (pin "2") (pinfunction "2_2") (pintype "passive"))
      (node (ref "TP19") (pin "1") (pinfunction "TP?_1") (pintype "passive"))
      (node (ref "TVS3") (pin "A") (pinfunction "2_A") (pintype "passive"))
      (node (ref "U16") (pin "3") (pinfunction "IN+_3") (pintype "passive"))
    )
    (net (code "129") (name "Net-(TP22-TP?)") (class "Default")
      (node (ref "CON6") (pin "1") (pinfunction "1_1") (pintype "passive"))
      (node (ref "R114") (pin "1") (pinfunction "1_1") (pintype "passive"))
      (node (ref "TP22") (pin "1") (pinfunction "TP?_1") (pintype "passive"))
    )
    (net (code "130") (name "Net-(TP24-TP?)") (class "Default")
      (node (ref "R122") (pin "1") (pinfunction "1_1") (pintype "passive"))
      (node (ref "TP24") (pin "1") (pinfunction "TP?_1") (pintype "passive"))
      (node (ref "U4") (pin "6") (pinfunction "D1_6") (pintype "passive"))
    )
    (net (code "131") (name "Net-(TP25-TP?)") (class "Default")
      (node (ref "R123") (pin "1") (pinfunction "1_1") (pintype "passive"))
      (node (ref "TP25") (pin "1") (pinfunction "TP?_1") (pintype "passive"))
      (node (ref "U4") (pin "9") (pinfunction "D2_9") (pintype "passive"))
    )
    (net (code "132") (name "Net-(TP26-TP?)") (class "Default")
      (node (ref "CON8") (pin "1") (pinfunction "1_1") (pintype "passive"))
      (node (ref "R80") (pin "1") (pinfunction "1_1") (pintype "passive"))
      (node (ref "TP26") (pin "1") (pinfunction "TP?_1") (pintype "passive"))
    )
    (net (code "133") (name "Net-(TP27-TP?)") (class "Default")
      (node (ref "CON9") (pin "1") (pinfunction "1_1") (pintype "passive"))
      (node (ref "R103") (pin "1") (pinfunction "1_1") (pintype "passive"))
      (node (ref "TP27") (pin "1") (pinfunction "TP?_1") (pintype "passive"))
    )
    (net (code "134") (name "Net-(TP34-TP?)") (class "Default")
      (node (ref "CON10") (pin "1") (pinfunction "1_1") (pintype "passive"))
      (node (ref "R117") (pin "1") (pinfunction "1_1") (pintype "passive"))
      (node (ref "TP34") (pin "1") (pinfunction "TP?_1") (pintype "passive"))
    )
    (net (code "135") (name "Net-(U1-+INA)") (class "Default")
      (node (ref "C57") (pin "1") (pinfunction "1_1") (pintype "passive"))
      (node (ref "R72") (pin "2") (pinfunction "2_2") (pintype "passive"))
      (node (ref "U1") (pin "3") (pinfunction "+INA_3") (pintype "passive"))
    )
    (net (code "136") (name "Net-(U1-+INB)") (class "Default")
      (node (ref "R2") (pin "2") (pinfunction "2_2") (pintype "passive"))
      (node (ref "R70") (pin "1") (pinfunction "1_1") (pintype "passive"))
      (node (ref "U1") (pin "5") (pinfunction "+INB_5") (pintype "passive"))
    )
    (net (code "137") (name "Net-(U1-+INC)") (class "Default")
      (node (ref "R1") (pin "2") (pinfunction "2_2") (pintype "passive"))
      (node (ref "R38") (pin "1") (pinfunction "1_1") (pintype "passive"))
      (node (ref "U1") (pin "12") (pinfunction "+INC_12") (pintype "passive"))
    )
    (net (code "138") (name "Net-(U1-+IND)") (class "Default")
      (node (ref "C60") (pin "1") (pinfunction "1_1") (pintype "passive"))
      (node (ref "R73") (pin "2") (pinfunction "2_2") (pintype "passive"))
      (node (ref "U1") (pin "14") (pinfunction "+IND_14") (pintype "passive"))
    )
    (net (code "139") (name "Net-(U1--INA)") (class "Default")
      (node (ref "C61") (pin "2") (pinfunction "2_2") (pintype "passive"))
      (node (ref "R70") (pin "2") (pinfunction "2_2") (pintype "passive"))
      (node (ref "R74") (pin "1") (pinfunction "1_1") (pintype "passive"))
      (node (ref "U1") (pin "1") (pinfunction "OUTA_1") (pintype "passive"))
      (node (ref "U1") (pin "2") (pinfunction "-INA_2") (pintype "passive"))
    )
    (net (code "140") (name "Net-(U1--INB)") (class "Default")
      (node (ref "C52") (pin "1") (pinfunction "1_1") (pintype "passive"))
      (node (ref "C53") (pin "1") (pinfunction "1_1") (pintype "passive"))
      (node (ref "R75") (pin "1") (pinfunction "1_1") (pintype "passive"))
      (node (ref "R77") (pin "1") (pinfunction "1_1") (pintype "passive"))
      (node (ref "U1") (pin "6") (pinfunction "-INB_6") (pintype "passive"))
      (node (ref "U1") (pin "7") (pinfunction "OUTB_7") (pintype "passive"))
    )
    (net (code "141") (name "Net-(U1--INC)") (class "Default")
      (node (ref "C54") (pin "1") (pinfunction "1_1") (pintype "passive"))
      (node (ref "C55") (pin "1") (pinfunction "1_1") (pintype "passive"))
      (node (ref "R79") (pin "1") (pinfunction "1_1") (pintype "passive"))
      (node (ref "R81") (pin "1") (pinfunction "1_1") (pintype "passive"))
      (node (ref "U1") (pin "10") (pinfunction "OUTC_10") (pintype "passive"))
      (node (ref "U1") (pin "11") (pinfunction "-INC_11") (pintype "passive"))
    )
    (net (code "142") (name "Net-(U2-IN-)") (class "Default")
      (node (ref "R10") (pin "1") (pinfunction "1_1") (pintype "passive"))
      (node (ref "R9") (pin "2") (pinfunction "2_2") (pintype "passive"))
      (node (ref "U2") (pin "4") (pinfunction "IN-_4") (pintype "passive"))
    )
    (net (code "143") (name "Net-(U2-~{SHDN})") (class "Default")
      (node (ref "R5") (pin "1") (pinfunction "1_1") (pintype "passive"))
      (node (ref "U2") (pin "5") (pinfunction "~{SHDN}_5") (pintype "passive"))
    )
    (net (code "144") (name "Net-(U3-+INA)") (class "Default")
      (node (ref "C15") (pin "1") (pinfunction "1_1") (pintype "passive"))
      (node (ref "R17") (pin "2") (pinfunction "2_2") (pintype "passive"))
      (node (ref "U3") (pin "3") (pinfunction "+INA_3") (pintype "passive"))
    )
    (net (code "145") (name "Net-(U3-+INB)") (class "Default")
      (node (ref "R11") (pin "2") (pinfunction "2_2") (pintype "passive"))
      (node (ref "R14") (pin "1") (pinfunction "1_1") (pintype "passive"))
      (node (ref "U3") (pin "5") (pinfunction "+INB_5") (pintype "passive"))
    )
    (net (code "146") (name "Net-(U3-+INC)") (class "Default")
      (node (ref "R12") (pin "1") (pinfunction "1_1") (pintype "passive"))
      (node (ref "R8") (pin "2") (pinfunction "2_2") (pintype "passive"))
      (node (ref "U3") (pin "12") (pinfunction "+INC_12") (pintype "passive"))
    )
    (net (code "147") (name "Net-(U3-+IND)") (class "Default")
      (node (ref "C20") (pin "1") (pinfunction "1_1") (pintype "passive"))
      (node (ref "R19") (pin "2") (pinfunction "2_2") (pintype "passive"))
      (node (ref "U3") (pin "14") (pinfunction "+IND_14") (pintype "passive"))
    )
    (net (code "148") (name "Net-(U3--INA)") (class "Default")
      (node (ref "C21") (pin "2") (pinfunction "2_2") (pintype "passive"))
      (node (ref "R14") (pin "2") (pinfunction "2_2") (pintype "passive"))
      (node (ref "R20") (pin "1") (pinfunction "1_1") (pintype "passive"))
      (node (ref "U3") (pin "1") (pinfunction "OUTA_1") (pintype "passive"))
      (node (ref "U3") (pin "2") (pinfunction "-INA_2") (pintype "passive"))
    )
    (net (code "149") (name "Net-(U3--INB)") (class "Default")
      (node (ref "C10") (pin "1") (pinfunction "1_1") (pintype "passive"))
      (node (ref "C9") (pin "1") (pinfunction "1_1") (pintype "passive"))
      (node (ref "R22") (pin "1") (pinfunction "1_1") (pintype "passive"))
      (node (ref "R23") (pin "1") (pinfunction "1_1") (pintype "passive"))
      (node (ref "U3") (pin "6") (pinfunction "-INB_6") (pintype "passive"))
      (node (ref "U3") (pin "7") (pinfunction "OUTB_7") (pintype "passive"))
    )
    (net (code "150") (name "Net-(U3--INC)") (class "Default")
      (node (ref "C11") (pin "1") (pinfunction "1_1") (pintype "passive"))
      (node (ref "C12") (pin "1") (pinfunction "1_1") (pintype "passive"))
      (node (ref "R25") (pin "1") (pinfunction "1_1") (pintype "passive"))
      (node (ref "R26") (pin "1") (pinfunction "1_1") (pintype "passive"))
      (node (ref "U3") (pin "10") (pinfunction "OUTC_10") (pintype "passive"))
      (node (ref "U3") (pin "11") (pinfunction "-INC_11") (pintype "passive"))
    )
    (net (code "151") (name "Net-(U4-EN)") (class "Default")
      (node (ref "R34") (pin "2") (pinfunction "2_2") (pintype "passive"))
      (node (ref "U4") (pin "2") (pinfunction "EN_2") (pintype "passive"))
    )
    (net (code "152") (name "Net-(U4-S1B)") (class "Default")
      (node (ref "R121") (pin "2") (pinfunction "2_2") (pintype "passive"))
      (node (ref "U4") (pin "5") (pinfunction "S1B_5") (pintype "passive"))
    )
    (net (code "153") (name "Net-(U4-S2B)") (class "Default")
      (node (ref "R125") (pin "1") (pinfunction "1_1") (pintype "passive"))
      (node (ref "U4") (pin "10") (pinfunction "S2B_10") (pintype "passive"))
    )
    (net (code "154") (name "Net-(U5-IN-)") (class "Default")
      (node (ref "R51") (pin "2") (pinfunction "2_2") (pintype "passive"))
      (node (ref "R52") (pin "1") (pinfunction "1_1") (pintype "passive"))
      (node (ref "U5") (pin "4") (pinfunction "IN-_4") (pintype "passive"))
    )
    (net (code "155") (name "Net-(U5-~{SHDN})") (class "Default")
      (node (ref "R44") (pin "1") (pinfunction "1_1") (pintype "passive"))
      (node (ref "U5") (pin "5") (pinfunction "~{SHDN}_5") (pintype "passive"))
    )
    (net (code "156") (name "Net-(U6-D+)") (class "Default")
      (node (ref "R47") (pin "2") (pinfunction "2_2") (pintype "passive"))
      (node (ref "U6") (pin "4") (pinfunction "D+_4") (pintype "passive"))
    )
    (net (code "157") (name "Net-(U6-D-)") (class "Default")
      (node (ref "R43") (pin "2") (pinfunction "2_2") (pintype "passive"))
      (node (ref "U6") (pin "3") (pinfunction "D-_3") (pintype "passive"))
    )
    (net (code "158") (name "Net-(U6-UCAP)") (class "Default")
      (node (ref "C48") (pin "1") (pinfunction "1_1") (pintype "passive"))
      (node (ref "U6") (pin "6") (pinfunction "UCAP_6") (pintype "passive"))
    )
    (net (code "159") (name "Net-(U6-XTAL1)") (class "Default")
      (node (ref "C41") (pin "1") (pinfunction "1_1") (pintype "passive"))
      (node (ref "U6") (pin "17") (pinfunction "XTAL1_17") (pintype "passive"))
      (node (ref "X1") (pin "1") (pinfunction "1_1") (pintype "passive"))
    )
    (net (code "160") (name "Net-(U6-XTAL2)") (class "Default")
      (node (ref "C39") (pin "1") (pinfunction "1_1") (pintype "passive"))
      (node (ref "U6") (pin "16") (pinfunction "XTAL2_16") (pintype "passive"))
      (node (ref "X1") (pin "3") (pinfunction "3_3") (pintype "passive"))
    )
    (net (code "161") (name "Net-(U7-+INA)") (class "Default")
      (node (ref "C38") (pin "1") (pinfunction "1_1") (pintype "passive"))
      (node (ref "R42") (pin "2") (pinfunction "2_2") (pintype "passive"))
      (node (ref "U7") (pin "3") (pinfunction "+INA_3") (pintype "passive"))
    )
    (net (code "162") (name "Net-(U7-+INB)") (class "Default")
      (node (ref "R45") (pin "2") (pinfunction "2_2") (pintype "passive"))
      (node (ref "R48") (pin "1") (pinfunction "1_1") (pintype "passive"))
      (node (ref "U7") (pin "5") (pinfunction "+INB_5") (pintype "passive"))
    )
    (net (code "163") (name "Net-(U7-+INC)") (class "Default")
      (node (ref "R40") (pin "2") (pinfunction "2_2") (pintype "passive"))
      (node (ref "R46") (pin "1") (pinfunction "1_1") (pintype "passive"))
      (node (ref "U7") (pin "12") (pinfunction "+INC_12") (pintype "passive"))
    )
    (net (code "164") (name "Net-(U7-+IND)") (class "Default")
      (node (ref "C46") (pin "1") (pinfunction "1_1") (pintype "passive"))
      (node (ref "R54") (pin "2") (pinfunction "2_2") (pintype "passive"))
      (node (ref "U7") (pin "14") (pinfunction "+IND_14") (pintype "passive"))
    )
    (net (code "165") (name "Net-(U7--INA)") (class "Default")
      (node (ref "C47") (pin "2") (pinfunction "2_2") (pintype "passive"))
      (node (ref "R48") (pin "2") (pinfunction "2_2") (pintype "passive"))
      (node (ref "R55") (pin "1") (pinfunction "1_1") (pintype "passive"))
      (node (ref "U7") (pin "1") (pinfunction "OUTA_1") (pintype "passive"))
      (node (ref "U7") (pin "2") (pinfunction "-INA_2") (pintype "passive"))
    )
    (net (code "166") (name "Net-(U7--INB)") (class "Default")
      (node (ref "C31") (pin "1") (pinfunction "1_1") (pintype "passive"))
      (node (ref "C32") (pin "1") (pinfunction "1_1") (pintype "passive"))
      (node (ref "R49") (pin "1") (pinfunction "1_1") (pintype "passive"))
      (node (ref "R50") (pin "1") (pinfunction "1_1") (pintype "passive"))
      (node (ref "U7") (pin "6") (pinfunction "-INB_6") (pintype "passive"))
      (node (ref "U7") (pin "7") (pinfunction "OUTB_7") (pintype "passive"))
    )
    (net (code "167") (name "Net-(U7--INC)") (class "Default")
      (node (ref "C42") (pin "1") (pinfunction "1_1") (pintype "passive"))
      (node (ref "C43") (pin "1") (pinfunction "1_1") (pintype "passive"))
      (node (ref "R58") (pin "1") (pinfunction "1_1") (pintype "passive"))
      (node (ref "R59") (pin "1") (pinfunction "1_1") (pintype "passive"))
      (node (ref "U7") (pin "10") (pinfunction "OUTC_10") (pintype "passive"))
      (node (ref "U7") (pin "11") (pinfunction "-INC_11") (pintype "passive"))
    )
    (net (code "168") (name "Net-(U10-+INA)") (class "Default")
      (node (ref "C86") (pin "1") (pinfunction "1_1") (pintype "passive"))
      (node (ref "R132") (pin "2") (pinfunction "2_2") (pintype "passive"))
      (node (ref "U10") (pin "3") (pinfunction "+INA_3") (pintype "passive"))
    )
    (net (code "169") (name "Net-(U10-+INB)") (class "Default")
      (node (ref "C93") (pin "2") (pinfunction "2_2") (pintype "passive"))
      (node (ref "R135") (pin "2") (pinfunction "2_2") (pintype "passive"))
      (node (ref "U10") (pin "5") (pinfunction "+INB_5") (pintype "passive"))
    )
    (net (code "170") (name "Net-(U10-+INC)") (class "Default")
      (node (ref "C94") (pin "2") (pinfunction "2_2") (pintype "passive"))
      (node (ref "R136") (pin "2") (pinfunction "2_2") (pintype "passive"))
      (node (ref "U10") (pin "12") (pinfunction "+INC_12") (pintype "passive"))
    )
    (net (code "171") (name "Net-(U10-+IND)") (class "Default")
      (node (ref "C87") (pin "1") (pinfunction "1_1") (pintype "passive"))
      (node (ref "R133") (pin "2") (pinfunction "2_2") (pintype "passive"))
      (node (ref "U10") (pin "14") (pinfunction "+IND_14") (pintype "passive"))
    )
    (net (code "172") (name "Net-(U10--INA)") (class "Default")
      (node (ref "R119") (pin "2") (pinfunction "2_2") (pintype "passive"))
      (node (ref "R134") (pin "1") (pinfunction "1_1") (pintype "passive"))
      (node (ref "U10") (pin "1") (pinfunction "OUTA_1") (pintype "passive"))
      (node (ref "U10") (pin "2") (pinfunction "-INA_2") (pintype "passive"))
    )
    (net (code "173") (name "Net-(U10--IND)") (class "Default")
      (node (ref "R130") (pin "2") (pinfunction "2_2") (pintype "passive"))
      (node (ref "R137") (pin "1") (pinfunction "1_1") (pintype "passive"))
      (node (ref "U10") (pin "15") (pinfunction "-IND_15") (pintype "passive"))
      (node (ref "U10") (pin "16") (pinfunction "OUTD_16") (pintype "passive"))
    )
    (net (code "174") (name "Net-(U11-IN-)") (class "Default")
      (node (ref "R85") (pin "2") (pinfunction "2_2") (pintype "passive"))
      (node (ref "R86") (pin "1") (pinfunction "1_1") (pintype "passive"))
      (node (ref "U11") (pin "4") (pinfunction "IN-_4") (pintype "passive"))
    )
    (net (code "175") (name "Net-(U11-~{SHDN})") (class "Default")
      (node (ref "R82") (pin "1") (pinfunction "1_1") (pintype "passive"))
      (node (ref "U11") (pin "5") (pinfunction "~{SHDN}_5") (pintype "passive"))
    )
    (net (code "176") (name "Net-(U12-IN+)") (class "Default")
      (node (ref "R126") (pin "1") (pinfunction "1_1") (pintype "passive"))
      (node (ref "R127") (pin "1") (pinfunction "1_1") (pintype "passive"))
      (node (ref "U12") (pin "12") (pinfunction "IN+_12") (pintype "passive"))
    )
    (net (code "177") (name "Net-(U12-VOUT)") (class "Default")
      (node (ref "R80") (pin "2") (pinfunction "2_2") (pintype "passive"))
      (node (ref "U12") (pin "13") (pinfunction "VOUT_13") (pintype "passive"))
    )
    (net (code "178") (name "Net-(U13-+INA)") (class "Default")
      (node (ref "C74") (pin "1") (pinfunction "1_1") (pintype "passive"))
      (node (ref "R91") (pin "2") (pinfunction "2_2") (pintype "passive"))
      (node (ref "U13") (pin "3") (pinfunction "+INA_3") (pintype "passive"))
    )
    (net (code "179") (name "Net-(U13-+INB)") (class "Default")
      (node (ref "C85") (pin "2") (pinfunction "2_2") (pintype "passive"))
      (node (ref "R96") (pin "2") (pinfunction "2_2") (pintype "passive"))
      (node (ref "U13") (pin "5") (pinfunction "+INB_5") (pintype "passive"))
    )
    (net (code "180") (name "Net-(U13-+INC)") (class "Default")
      (node (ref "C104") (pin "2") (pinfunction "2_2") (pintype "passive"))
      (node (ref "R141") (pin "2") (pinfunction "2_2") (pintype "passive"))
      (node (ref "U13") (pin "12") (pinfunction "+INC_12") (pintype "passive"))
    )
    (net (code "181") (name "Net-(U13-+IND)") (class "Default")
      (node (ref "C99") (pin "1") (pinfunction "1_1") (pintype "passive"))
      (node (ref "R140") (pin "2") (pinfunction "2_2") (pintype "passive"))
      (node (ref "U13") (pin "14") (pinfunction "+IND_14") (pintype "passive"))
    )
    (net (code "182") (name "Net-(U13--INA)") (class "Default")
      (node (ref "R89") (pin "2") (pinfunction "2_2") (pintype "passive"))
      (node (ref "R95") (pin "1") (pinfunction "1_1") (pintype "passive"))
      (node (ref "U13") (pin "1") (pinfunction "OUTA_1") (pintype "passive"))
      (node (ref "U13") (pin "2") (pinfunction "-INA_2") (pintype "passive"))
    )
    (net (code "183") (name "Net-(U13--IND)") (class "Default")
      (node (ref "R139") (pin "2") (pinfunction "2_2") (pintype "passive"))
      (node (ref "R142") (pin "1") (pinfunction "1_1") (pintype "passive"))
      (node (ref "U13") (pin "15") (pinfunction "-IND_15") (pintype "passive"))
      (node (ref "U13") (pin "16") (pinfunction "OUTD_16") (pintype "passive"))
    )
    (net (code "184") (name "Net-(U14-EN)") (class "Default")
      (node (ref "R78") (pin "2") (pinfunction "2_2") (pintype "passive"))
      (node (ref "U14") (pin "2") (pinfunction "EN_2") (pintype "passive"))
    )
    (net (code "185") (name "Net-(U14-S1B)") (class "Default")
      (node (ref "R76") (pin "2") (pinfunction "2_2") (pintype "passive"))
      (node (ref "U14") (pin "5") (pinfunction "S1B_5") (pintype "passive"))
    )
    (net (code "186") (name "Net-(U14-S2B)") (class "Default")
      (node (ref "R102") (pin "1") (pinfunction "1_1") (pintype "passive"))
      (node (ref "U14") (pin "10") (pinfunction "S2B_10") (pintype "passive"))
    )
    (net (code "187") (name "Net-(U15-IN+)") (class "Default")
      (node (ref "R128") (pin "1") (pinfunction "1_1") (pintype "passive"))
      (node (ref "R129") (pin "1") (pinfunction "1_1") (pintype "passive"))
      (node (ref "U15") (pin "12") (pinfunction "IN+_12") (pintype "passive"))
    )
    (net (code "188") (name "Net-(U15-VOUT)") (class "Default")
      (node (ref "R103") (pin "2") (pinfunction "2_2") (pintype "passive"))
      (node (ref "U15") (pin "13") (pinfunction "VOUT_13") (pintype "passive"))
    )
    (net (code "189") (name "Net-(U16-IN-)") (class "Default")
      (node (ref "R111") (pin "2") (pinfunction "2_2") (pintype "passive"))
      (node (ref "R112") (pin "1") (pinfunction "1_1") (pintype "passive"))
      (node (ref "U16") (pin "4") (pinfunction "IN-_4") (pintype "passive"))
    )
    (net (code "190") (name "Net-(U16-~{SHDN})") (class "Default")
      (node (ref "R110") (pin "1") (pinfunction "1_1") (pintype "passive"))
      (node (ref "U16") (pin "5") (pinfunction "~{SHDN}_5") (pintype "passive"))
    )
    (net (code "191") (name "Net-(U17-IN+)") (class "Default")
      (node (ref "R113") (pin "1") (pinfunction "1_1") (pintype "passive"))
      (node (ref "R115") (pin "1") (pinfunction "1_1") (pintype "passive"))
      (node (ref "U17") (pin "12") (pinfunction "IN+_12") (pintype "passive"))
    )
    (net (code "192") (name "Net-(U17-VOUT)") (class "Default")
      (node (ref "R114") (pin "2") (pinfunction "2_2") (pintype "passive"))
      (node (ref "U17") (pin "13") (pinfunction "VOUT_13") (pintype "passive"))
    )
    (net (code "193") (name "Net-(U18-IN+)") (class "Default")
      (node (ref "R116") (pin "1") (pinfunction "1_1") (pintype "passive"))
      (node (ref "R118") (pin "1") (pinfunction "1_1") (pintype "passive"))
      (node (ref "U18") (pin "12") (pinfunction "IN+_12") (pintype "passive"))
    )
    (net (code "194") (name "Net-(U18-VOUT)") (class "Default")
      (node (ref "R117") (pin "2") (pinfunction "2_2") (pintype "passive"))
      (node (ref "U18") (pin "13") (pinfunction "VOUT_13") (pintype "passive"))
    )
    (net (code "195") (name "Net-(U19-EN)") (class "Default")
      (node (ref "R131") (pin "2") (pinfunction "2_2") (pintype "passive"))
      (node (ref "U19") (pin "2") (pinfunction "EN_2") (pintype "passive"))
    )
    (net (code "196") (name "Net-(U21-EN)") (class "Default")
      (node (ref "R138") (pin "2") (pinfunction "2_2") (pintype "passive"))
      (node (ref "U21") (pin "2") (pinfunction "EN_2") (pintype "passive"))
    )
    (net (code "197") (name "Net-(U22-~-Pad1)") (class "Default")
      (node (ref "U22") (pin "1") (pinfunction "~_1") (pintype "passive"))
      (node (ref "XFR1") (pin "7") (pinfunction "Sec+_7") (pintype "passive"))
    )
    (net (code "198") (name "Net-(U22-~-Pad2)") (class "Default")
      (node (ref "U22") (pin "2") (pinfunction "~_2") (pintype "passive"))
      (node (ref "XFR1") (pin "12") (pinfunction "Sec-_12") (pintype "passive"))
    )
    (net (code "199") (name "Net-(U23-+INA)") (class "Default")
      (node (ref "C71") (pin "1") (pinfunction "1_1") (pintype "passive"))
      (node (ref "R100") (pin "2") (pinfunction "2_2") (pintype "passive"))
      (node (ref "U23") (pin "3") (pinfunction "+INA_3") (pintype "passive"))
    )
    (net (code "200") (name "Net-(U23-+INB)") (class "Default")
      (node (ref "R101") (pin "2") (pinfunction "2_2") (pintype "passive"))
      (node (ref "R105") (pin "1") (pinfunction "1_1") (pintype "passive"))
      (node (ref "U23") (pin "5") (pinfunction "+INB_5") (pintype "passive"))
    )
    (net (code "201") (name "Net-(U23-+INC)") (class "Default")
      (node (ref "R104") (pin "1") (pinfunction "1_1") (pintype "passive"))
      (node (ref "R88") (pin "2") (pinfunction "2_2") (pintype "passive"))
      (node (ref "U23") (pin "12") (pinfunction "+INC_12") (pintype "passive"))
    )
    (net (code "202") (name "Net-(U23-+IND)") (class "Default")
      (node (ref "C107") (pin "1") (pinfunction "1_1") (pintype "passive"))
      (node (ref "R29") (pin "2") (pinfunction "2_2") (pintype "passive"))
      (node (ref "U23") (pin "14") (pinfunction "+IND_14") (pintype "passive"))
    )
    (net (code "203") (name "Net-(U23--INA)") (class "Default")
      (node (ref "C108") (pin "2") (pinfunction "2_2") (pintype "passive"))
      (node (ref "R105") (pin "2") (pinfunction "2_2") (pintype "passive"))
      (node (ref "R30") (pin "1") (pinfunction "1_1") (pintype "passive"))
      (node (ref "U23") (pin "1") (pinfunction "OUTA_1") (pintype "passive"))
      (node (ref "U23") (pin "2") (pinfunction "-INA_2") (pintype "passive"))
    )
    (net (code "204") (name "Net-(U23--INB)") (class "Default")
      (node (ref "C68") (pin "1") (pinfunction "1_1") (pintype "passive"))
      (node (ref "C69") (pin "1") (pinfunction "1_1") (pintype "passive"))
      (node (ref "R107") (pin "1") (pinfunction "1_1") (pintype "passive"))
      (node (ref "R108") (pin "1") (pinfunction "1_1") (pintype "passive"))
      (node (ref "U23") (pin "6") (pinfunction "-INB_6") (pintype "passive"))
      (node (ref "U23") (pin "7") (pinfunction "OUTB_7") (pintype "passive"))
    )
    (net (code "205") (name "Net-(U23--INC)") (class "Default")
      (node (ref "C19") (pin "1") (pinfunction "1_1") (pintype "passive"))
      (node (ref "C8") (pin "1") (pinfunction "1_1") (pintype "passive"))
      (node (ref "R31") (pin "1") (pinfunction "1_1") (pintype "passive"))
      (node (ref "R87") (pin "1") (pinfunction "1_1") (pintype "passive"))
      (node (ref "U23") (pin "10") (pinfunction "OUTC_10") (pintype "passive"))
      (node (ref "U23") (pin "11") (pinfunction "-INC_11") (pintype "passive"))
    )
    (net (code "206") (name "Net-(VR1-ADJ)") (class "Default")
      (node (ref "R4") (pin "2") (pinfunction "2_2") (pintype "passive"))
      (node (ref "R6") (pin "2") (pinfunction "2_2") (pintype "passive"))
      (node (ref "VR1") (pin "2") (pinfunction "ADJ_2") (pintype "passive"))
    )
    (net (code "207") (name "Net-(VR2-ADJ)") (class "Default")
      (node (ref "R13") (pin "2") (pinfunction "2_2") (pintype "passive"))
      (node (ref "R18") (pin "1") (pinfunction "1_1") (pintype "passive"))
      (node (ref "VR2") (pin "2") (pinfunction "ADJ_2") (pintype "passive"))
    )
    (net (code "208") (name "Net-(VR3-ADJ)") (class "Default")
      (node (ref "R21") (pin "2") (pinfunction "2_2") (pintype "passive"))
      (node (ref "R28") (pin "1") (pinfunction "1_1") (pintype "passive"))
      (node (ref "VR3") (pin "2") (pinfunction "ADJ_2") (pintype "passive"))
    )
    (net (code "209") (name "Net-(VR4-ADJ)") (class "Default")
      (node (ref "R35") (pin "1") (pinfunction "1_1") (pintype "passive"))
      (node (ref "R36") (pin "1") (pinfunction "1_1") (pintype "passive"))
      (node (ref "VR4") (pin "2") (pinfunction "ADJ_2") (pintype "passive"))
    )
    (net (code "210") (name "Net-(XFR1-Pri+-Pad4)") (class "Default")
      (node (ref "XFR1") (pin "3") (pinfunction "Pri-_3") (pintype "passive"))
      (node (ref "XFR1") (pin "4") (pinfunction "Pri+_4") (pintype "passive"))
    )
    (net (code "211") (name "VUSB") (class "Default")
      (node (ref "CN1") (pin "1") (pinfunction "1_1") (pintype "passive"))
      (node (ref "U6") (pin "2") (pinfunction "UVCC_2") (pintype "passive"))
      (node (ref "U6") (pin "7") (pinfunction "VBUS_7") (pintype "passive"))
    )
    (net (code "212") (name "unconnected-(CN1-Pad4)") (class "Default")
      (node (ref "CN1") (pin "4") (pinfunction "4_4") (pintype "passive"))
    )
    (net (code "213") (name "unconnected-(U1-NC-Pad8)") (class "Default")
      (node (ref "U1") (pin "8") (pinfunction "NC_8") (pintype "passive"))
    )
    (net (code "214") (name "unconnected-(U1-NC-Pad9)") (class "Default")
      (node (ref "U1") (pin "9") (pinfunction "NC_9") (pintype "passive"))
    )
    (net (code "215") (name "unconnected-(U3-NC-Pad8)") (class "Default")
      (node (ref "U3") (pin "8") (pinfunction "NC_8") (pintype "passive"))
    )
    (net (code "216") (name "unconnected-(U3-NC-Pad9)") (class "Default")
      (node (ref "U3") (pin "9") (pinfunction "NC_9") (pintype "passive"))
    )
    (net (code "217") (name "unconnected-(U4-NC-Pad7)") (class "Default")
      (node (ref "U4") (pin "7") (pinfunction "NC_7") (pintype "passive"))
    )
    (net (code "218") (name "unconnected-(U4-NC-Pad8)") (class "Default")
      (node (ref "U4") (pin "8") (pinfunction "NC_8") (pintype "passive"))
    )
    (net (code "219") (name "unconnected-(U7-NC-Pad8)") (class "Default")
      (node (ref "U7") (pin "8") (pinfunction "NC_8") (pintype "passive"))
    )
    (net (code "220") (name "unconnected-(U7-NC-Pad9)") (class "Default")
      (node (ref "U7") (pin "9") (pinfunction "NC_9") (pintype "passive"))
    )
    (net (code "221") (name "unconnected-(U10-NC-Pad8)") (class "Default")
      (node (ref "U10") (pin "8") (pinfunction "NC_8") (pintype "passive"))
    )
    (net (code "222") (name "unconnected-(U10-NC-Pad9)") (class "Default")
      (node (ref "U10") (pin "9") (pinfunction "NC_9") (pintype "passive"))
    )
    (net (code "223") (name "unconnected-(U12-NC-Pad1)") (class "Default")
      (node (ref "U12") (pin "1") (pinfunction "NC_1") (pintype "passive"))
    )
    (net (code "224") (name "unconnected-(U12-NC-Pad9)") (class "Default")
      (node (ref "U12") (pin "9") (pinfunction "NC_9") (pintype "passive"))
    )
    (net (code "225") (name "unconnected-(U12-NC-Pad14)") (class "Default")
      (node (ref "U12") (pin "14") (pinfunction "NC_14") (pintype "passive"))
    )
    (net (code "226") (name "unconnected-(U12-SDO-Pad6)") (class "Default")
      (node (ref "U12") (pin "6") (pinfunction "SDO_6") (pintype "passive"))
    )
    (net (code "227") (name "unconnected-(U13-NC-Pad8)") (class "Default")
      (node (ref "U13") (pin "8") (pinfunction "NC_8") (pintype "passive"))
    )
    (net (code "228") (name "unconnected-(U13-NC-Pad9)") (class "Default")
      (node (ref "U13") (pin "9") (pinfunction "NC_9") (pintype "passive"))
    )
    (net (code "229") (name "unconnected-(U14-NC-Pad7)") (class "Default")
      (node (ref "U14") (pin "7") (pinfunction "NC_7") (pintype "passive"))
    )
    (net (code "230") (name "unconnected-(U14-NC-Pad8)") (class "Default")
      (node (ref "U14") (pin "8") (pinfunction "NC_8") (pintype "passive"))
    )
    (net (code "231") (name "unconnected-(U15-NC-Pad1)") (class "Default")
      (node (ref "U15") (pin "1") (pinfunction "NC_1") (pintype "passive"))
    )
    (net (code "232") (name "unconnected-(U15-NC-Pad9)") (class "Default")
      (node (ref "U15") (pin "9") (pinfunction "NC_9") (pintype "passive"))
    )
    (net (code "233") (name "unconnected-(U15-NC-Pad14)") (class "Default")
      (node (ref "U15") (pin "14") (pinfunction "NC_14") (pintype "passive"))
    )
    (net (code "234") (name "unconnected-(U15-SDO-Pad6)") (class "Default")
      (node (ref "U15") (pin "6") (pinfunction "SDO_6") (pintype "passive"))
    )
    (net (code "235") (name "unconnected-(U17-NC-Pad1)") (class "Default")
      (node (ref "U17") (pin "1") (pinfunction "NC_1") (pintype "passive"))
    )
    (net (code "236") (name "unconnected-(U17-NC-Pad9)") (class "Default")
      (node (ref "U17") (pin "9") (pinfunction "NC_9") (pintype "passive"))
    )
    (net (code "237") (name "unconnected-(U17-NC-Pad14)") (class "Default")
      (node (ref "U17") (pin "14") (pinfunction "NC_14") (pintype "passive"))
    )
    (net (code "238") (name "unconnected-(U17-SDO-Pad6)") (class "Default")
      (node (ref "U17") (pin "6") (pinfunction "SDO_6") (pintype "passive"))
    )
    (net (code "239") (name "unconnected-(U18-NC-Pad1)") (class "Default")
      (node (ref "U18") (pin "1") (pinfunction "NC_1") (pintype "passive"))
    )
    (net (code "240") (name "unconnected-(U18-NC-Pad9)") (class "Default")
      (node (ref "U18") (pin "9") (pinfunction "NC_9") (pintype "passive"))
    )
    (net (code "241") (name "unconnected-(U18-NC-Pad14)") (class "Default")
      (node (ref "U18") (pin "14") (pinfunction "NC_14") (pintype "passive"))
    )
    (net (code "242") (name "unconnected-(U18-SDO-Pad6)") (class "Default")
      (node (ref "U18") (pin "6") (pinfunction "SDO_6") (pintype "passive"))
    )
    (net (code "243") (name "unconnected-(U19-NC-Pad7)") (class "Default")
      (node (ref "U19") (pin "7") (pinfunction "NC_7") (pintype "passive"))
    )
    (net (code "244") (name "unconnected-(U19-NC-Pad8)") (class "Default")
      (node (ref "U19") (pin "8") (pinfunction "NC_8") (pintype "passive"))
    )
    (net (code "245") (name "unconnected-(U20-I{slash}O_VCC1-Pad20)") (class "Default")
      (node (ref "U20") (pin "20") (pinfunction "I/O_VCC1_20") (pintype "passive"))
    )
    (net (code "246") (name "unconnected-(U20-I{slash}O_VCC2-Pad18)") (class "Default")
      (node (ref "U20") (pin "18") (pinfunction "I/O_VCC2_18") (pintype "passive"))
    )
    (net (code "247") (name "unconnected-(U20-I{slash}O_VL1-Pad1)") (class "Default")
      (node (ref "U20") (pin "1") (pinfunction "I/O_VL1_1") (pintype "passive"))
    )
    (net (code "248") (name "unconnected-(U20-I{slash}O_VL2-Pad3)") (class "Default")
      (node (ref "U20") (pin "3") (pinfunction "I/O_VL2_3") (pintype "passive"))
    )
    (net (code "249") (name "unconnected-(U21-NC-Pad7)") (class "Default")
      (node (ref "U21") (pin "7") (pinfunction "NC_7") (pintype "passive"))
    )
    (net (code "250") (name "unconnected-(U21-NC-Pad8)") (class "Default")
      (node (ref "U21") (pin "8") (pinfunction "NC_8") (pintype "passive"))
    )
    (net (code "251") (name "unconnected-(U23-NC-Pad8)") (class "Default")
      (node (ref "U23") (pin "8") (pinfunction "NC_8") (pintype "passive"))
    )
    (net (code "252") (name "unconnected-(U23-NC-Pad9)") (class "Default")
      (node (ref "U23") (pin "9") (pinfunction "NC_9") (pintype "passive"))
    )
  )
)
